# all.net
KiCad netlist of a schematic drawn in EAGLE
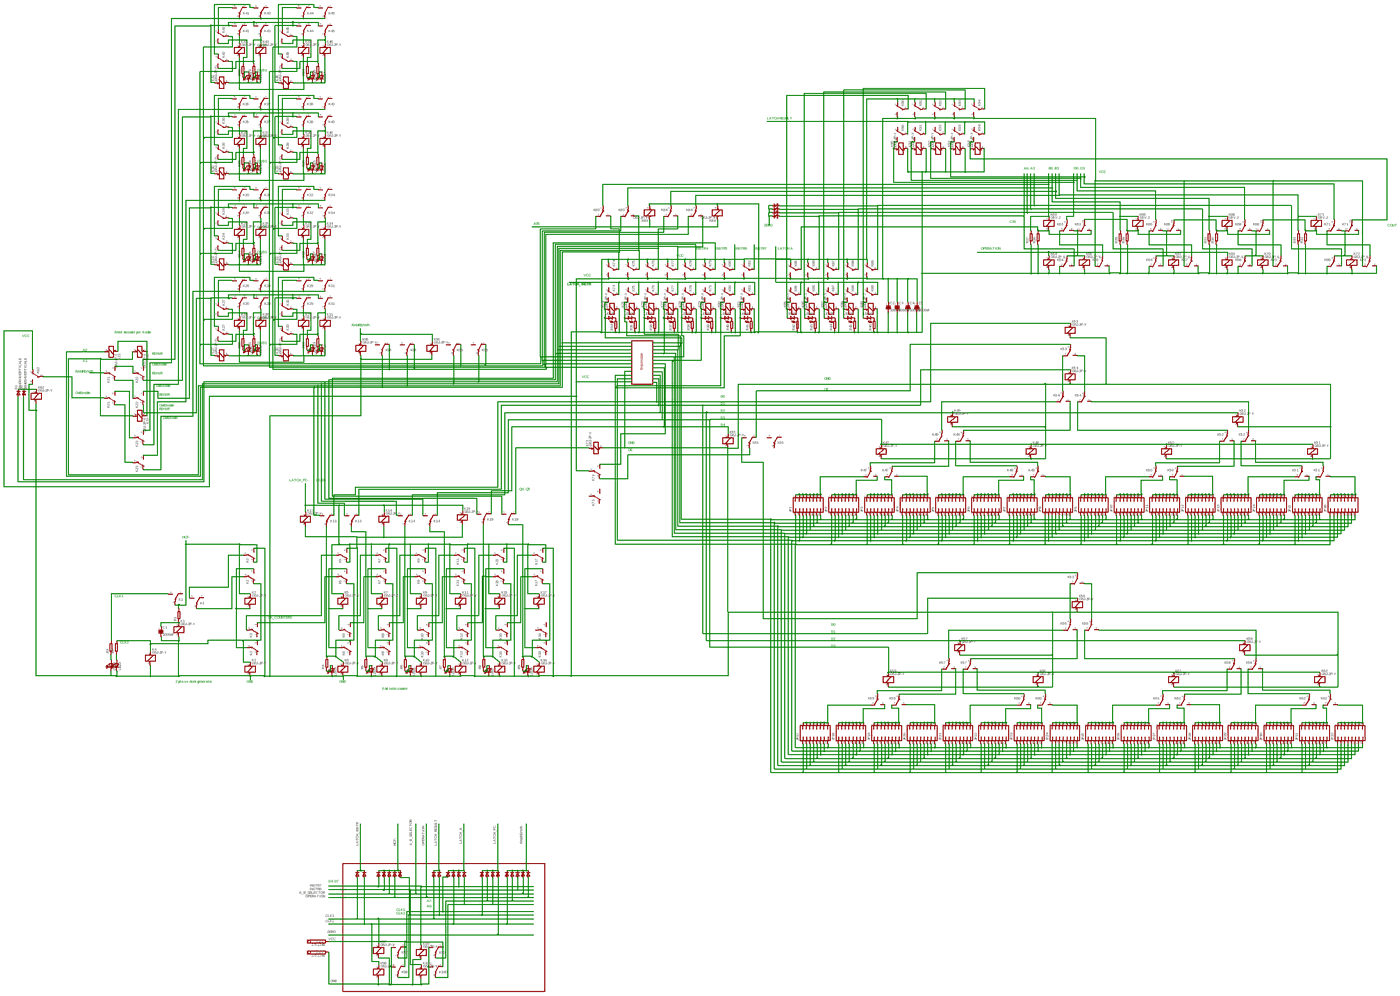
[diagram p0: schematic, sheet 1, overview]
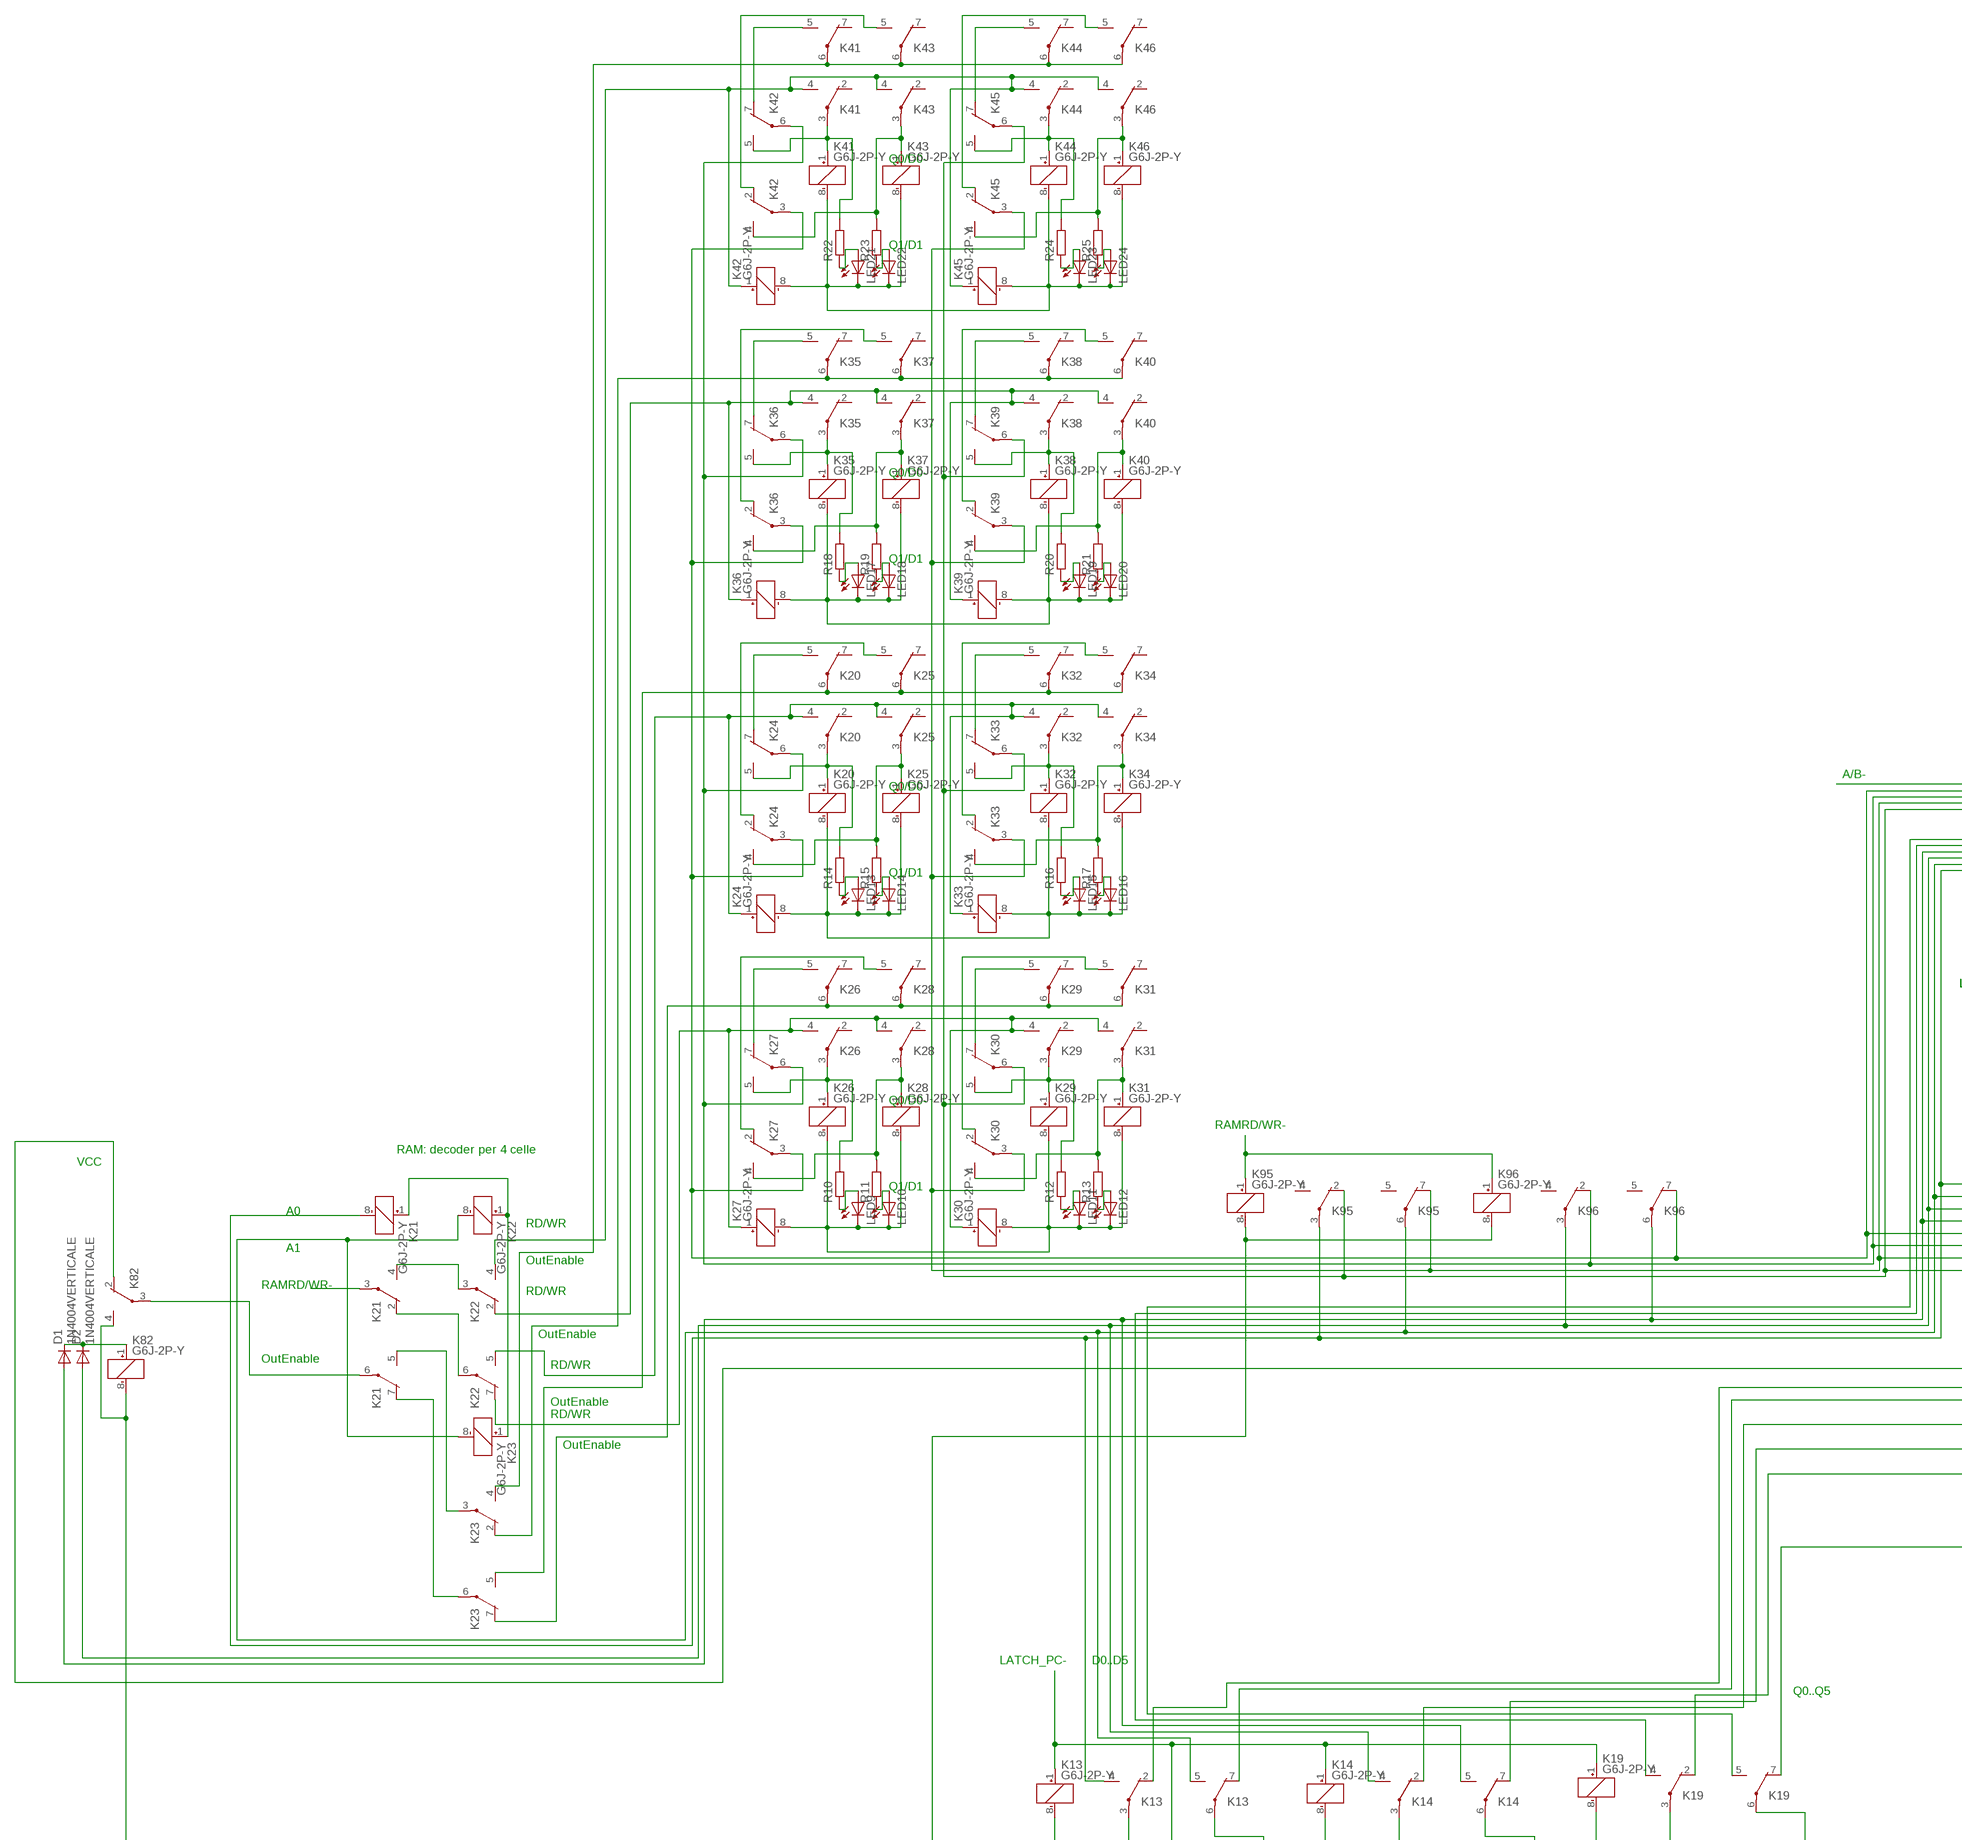
[diagram p1: schematic, sheet 1, part 1 of 5]
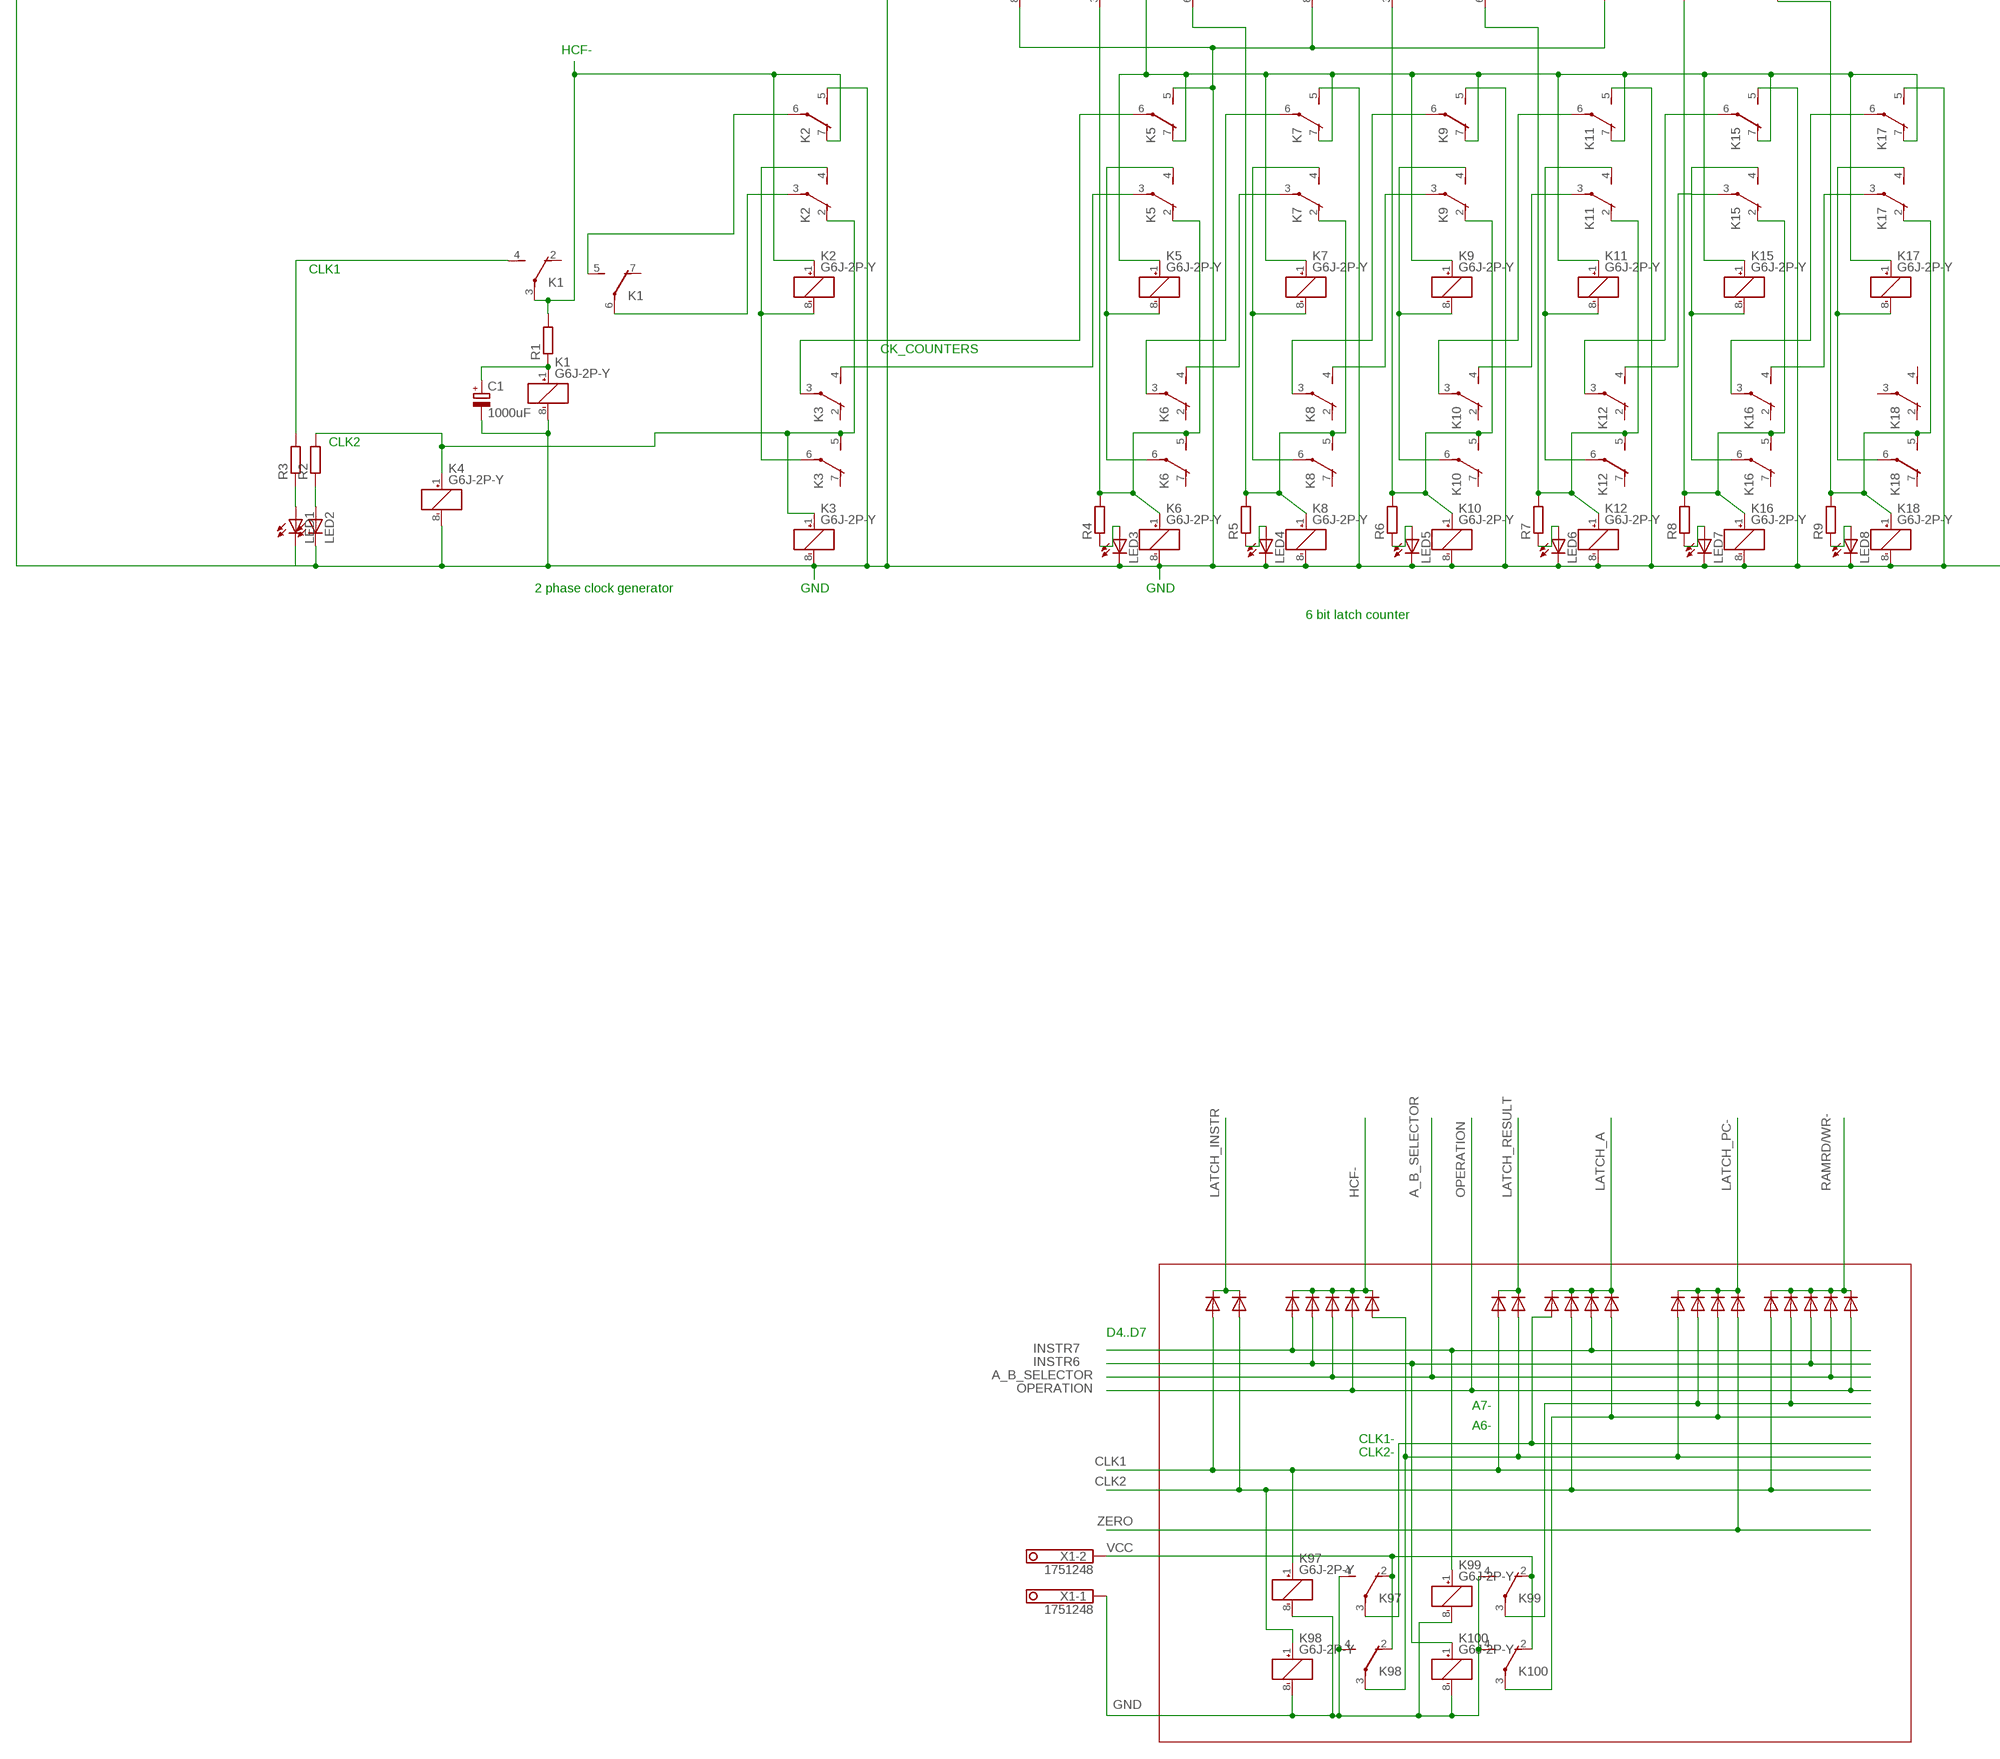
[diagram p2: schematic, sheet 1, part 2 of 5]
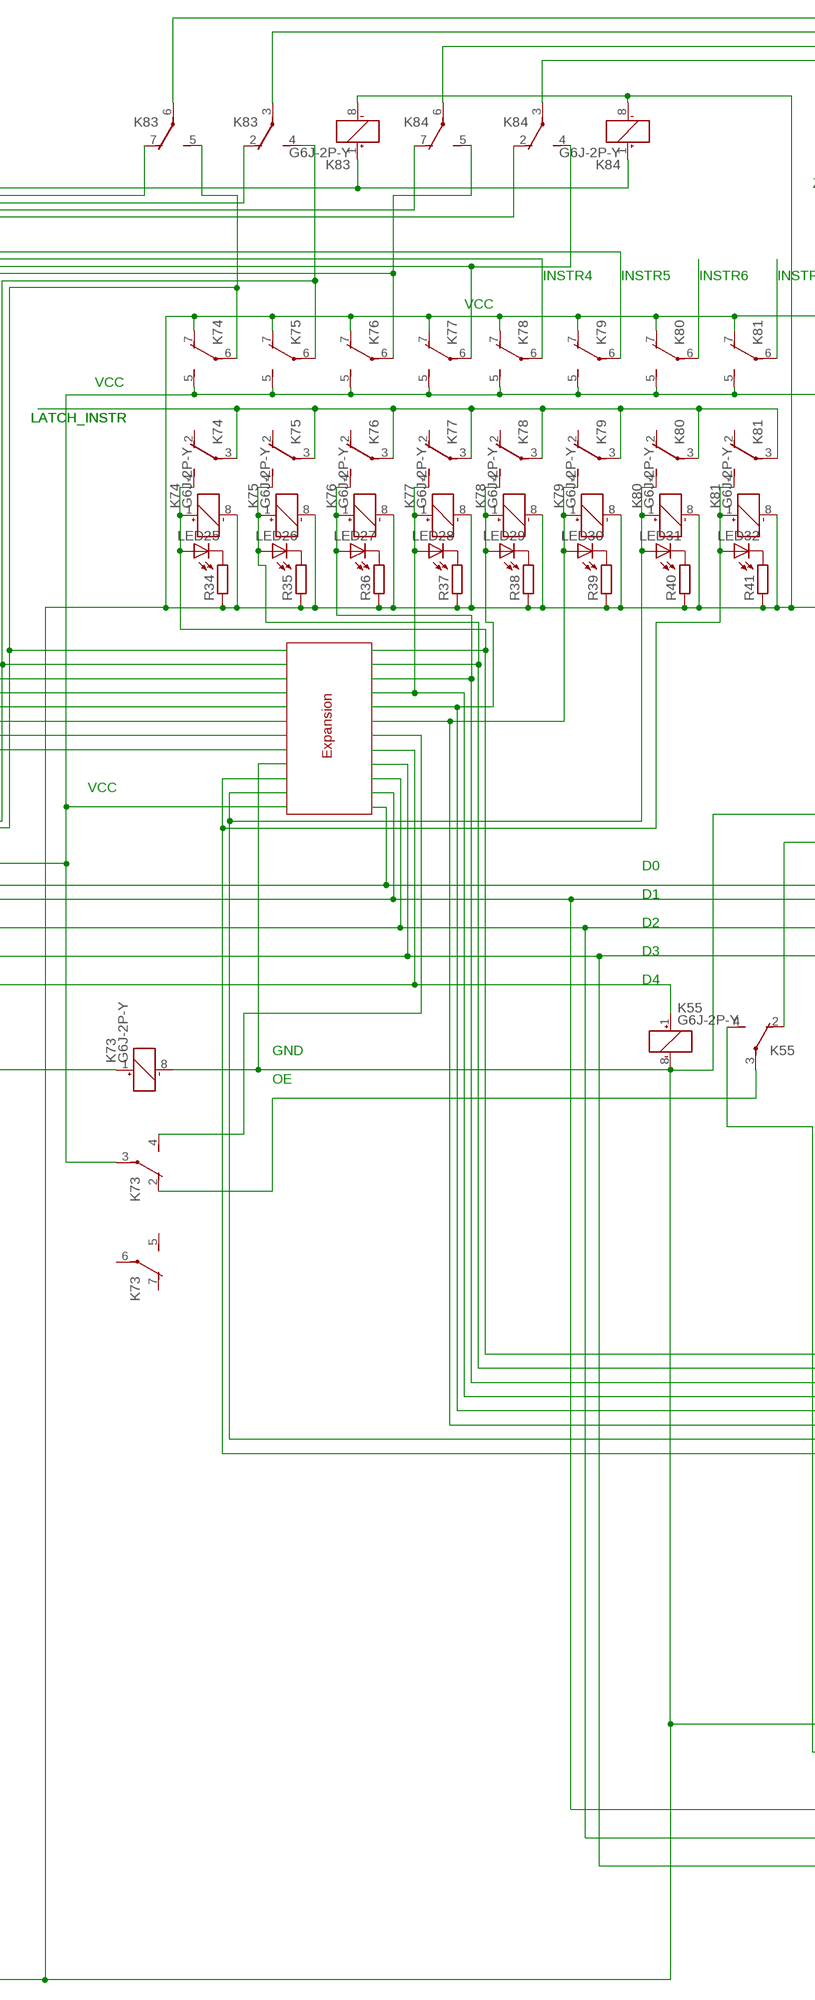
[diagram p3: schematic, sheet 1, part 3 of 5]
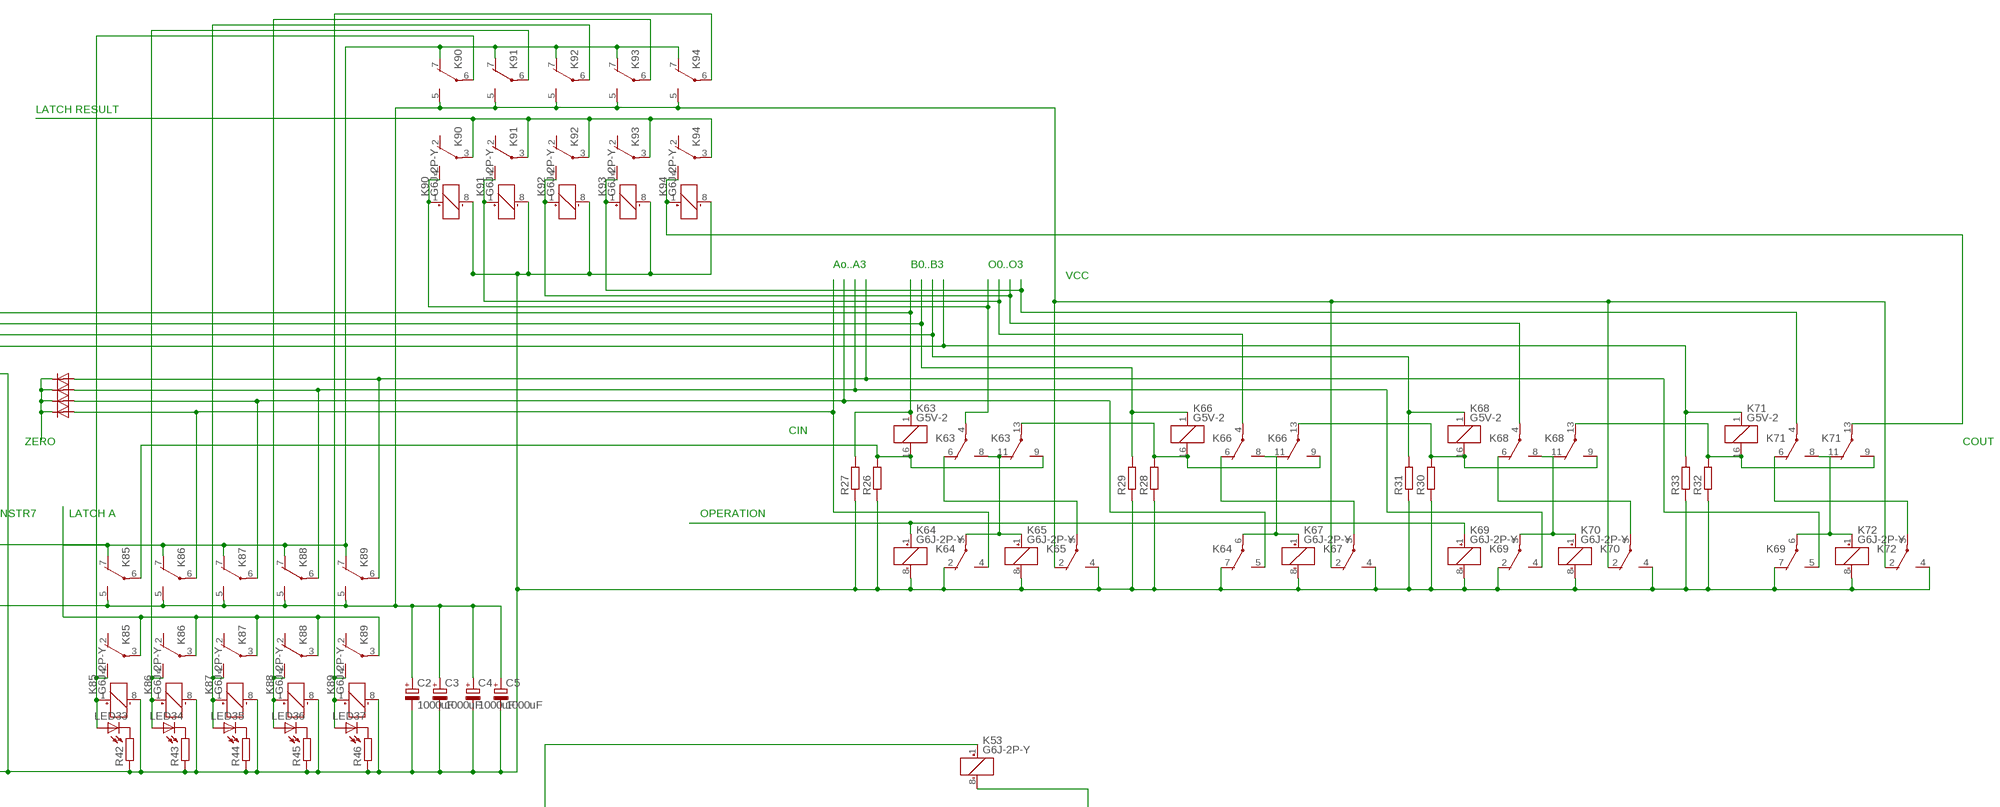
[diagram p4: schematic, sheet 1, part 4 of 5]
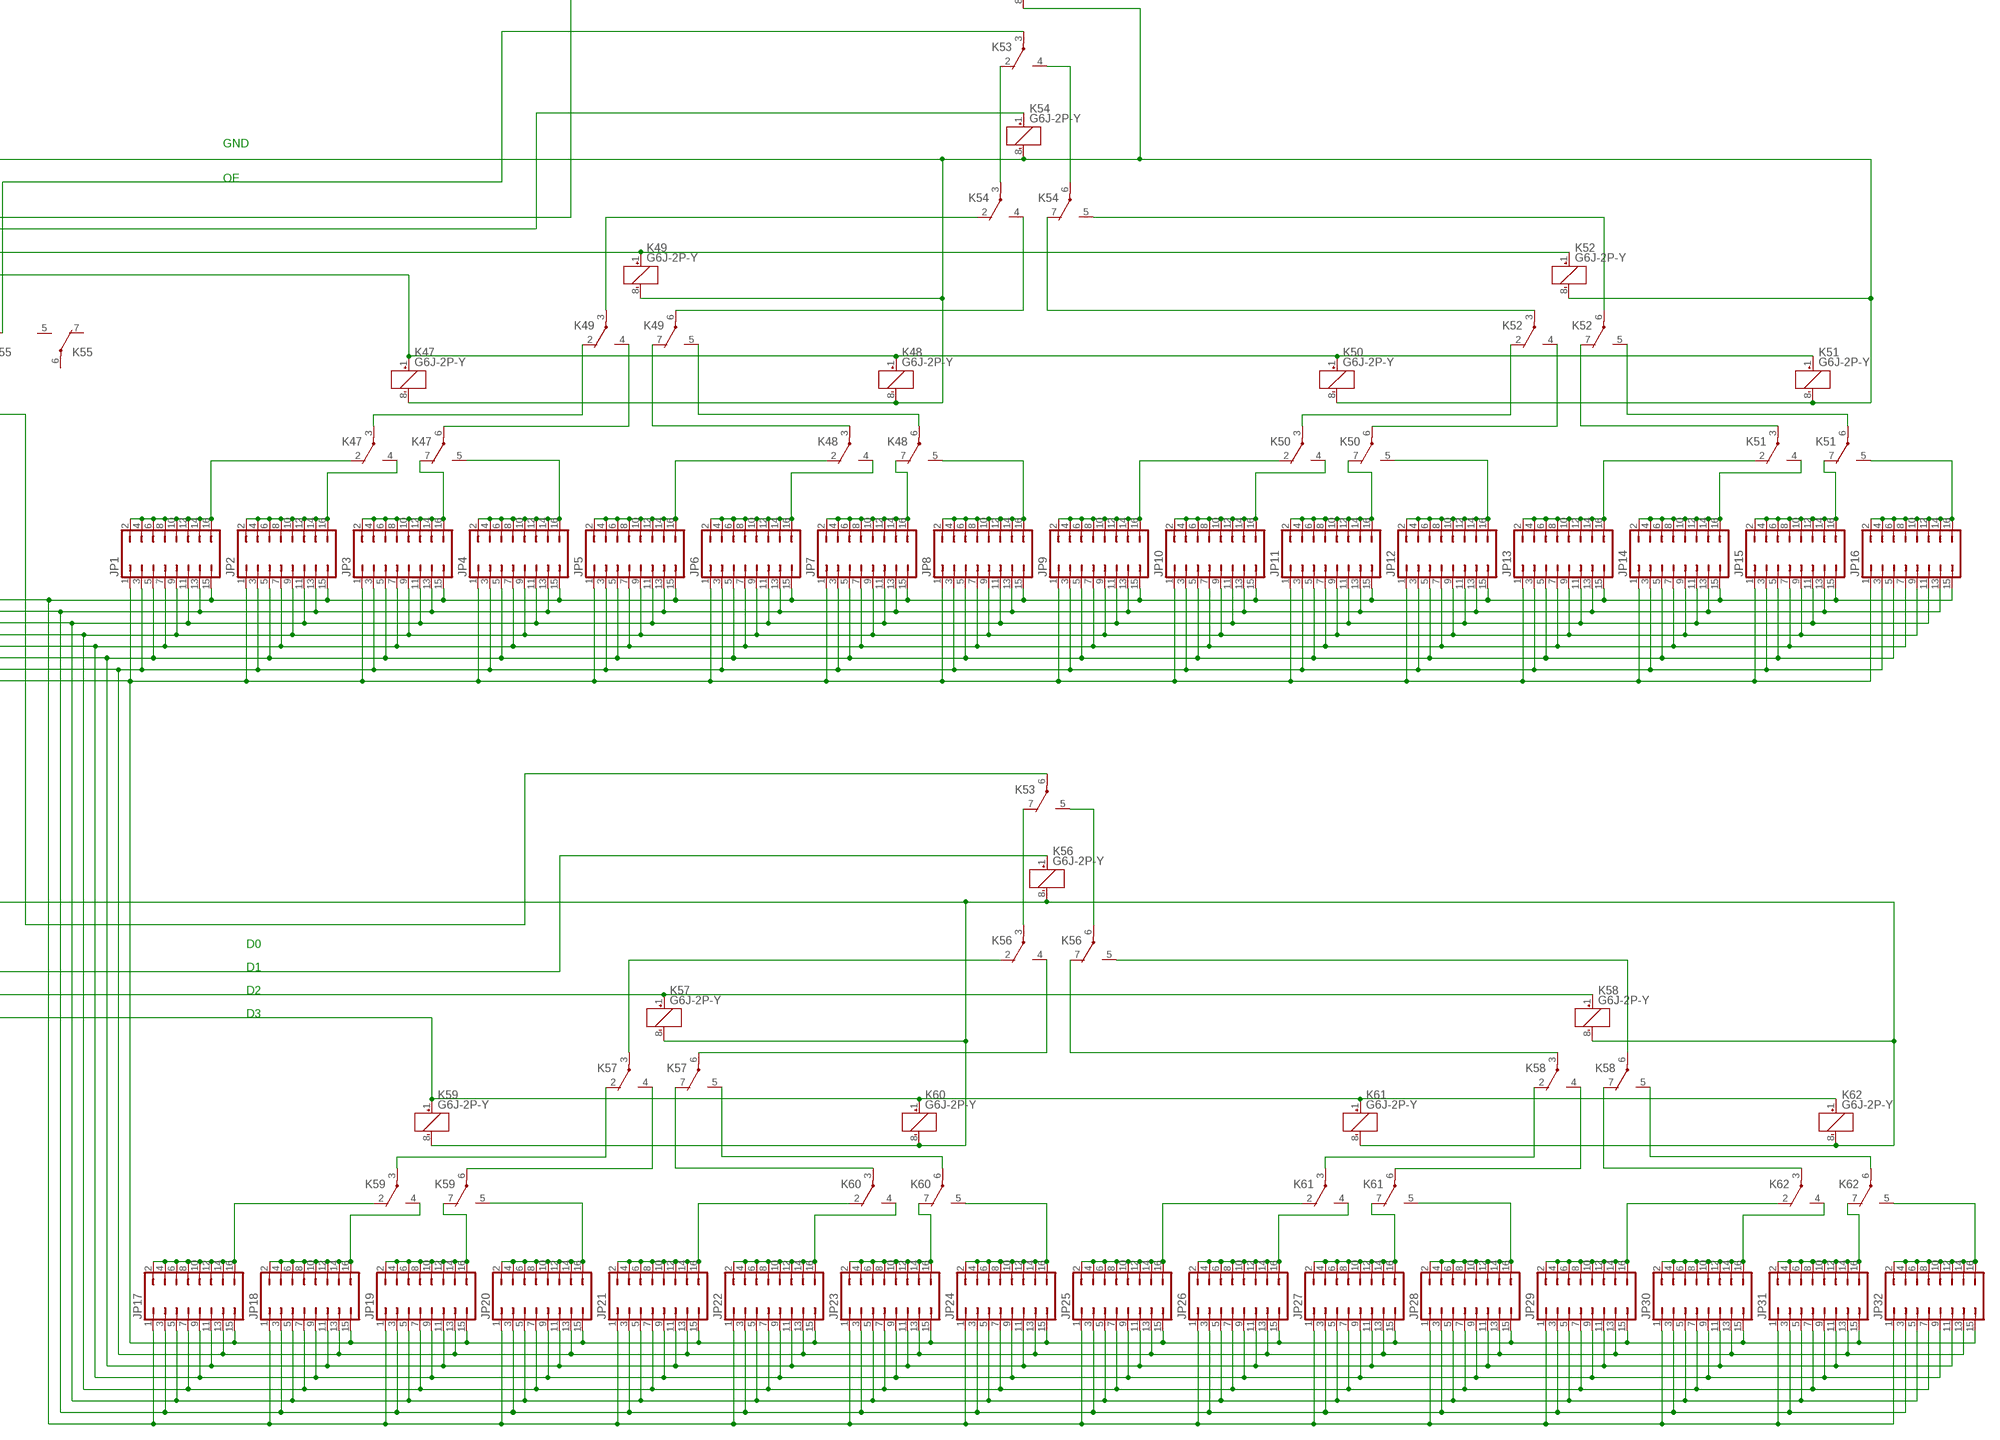
[diagram p5: schematic, sheet 1, part 5 of 5]

(export (version "E")
  (design (tool "Eeschema 10.0.6"))
  (components
    (comp (ref "C1")
      (value "1000uF")
      (footprint "eagle-import:E5-10,5")
      (libsource (lib "eagle-import") (part "CPOL-EUE5-10.5"))
    )
    (comp (ref "C2")
      (value "1000uF")
      (footprint "eagle-import:E3,5-10")
      (libsource (lib "eagle-import") (part "CPOL-EUE3.5-10"))
    )
    (comp (ref "C3")
      (value "1000uF")
      (footprint "eagle-import:E3,5-10")
      (libsource (lib "eagle-import") (part "CPOL-EUE3.5-10"))
    )
    (comp (ref "C4")
      (value "1000uF")
      (footprint "eagle-import:E3,5-10")
      (libsource (lib "eagle-import") (part "CPOL-EUE3.5-10"))
    )
    (comp (ref "C5")
      (value "1000uF")
      (footprint "eagle-import:E3,5-10")
      (libsource (lib "eagle-import") (part "CPOL-EUE3.5-10"))
    )
    (comp (ref "D1")
      (value "1N4004VERTICALE")
      (footprint "eagle-import:ZDIO-2.5")
      (libsource (lib "eagle-import") (part "1N4004VERTICALE"))
    )
    (comp (ref "D2")
      (value "1N4004VERTICALE")
      (footprint "eagle-import:ZDIO-2.5")
      (libsource (lib "eagle-import") (part "1N4004VERTICALE"))
    )
    (comp (ref "D3")
      (value "1N4004VERTICALE")
      (footprint "eagle-import:ZDIO-2.5")
      (libsource (lib "eagle-import") (part "1N4004VERTICALE"))
    )
    (comp (ref "D4")
      (value "1N4004VERTICALE")
      (footprint "eagle-import:ZDIO-2.5")
      (libsource (lib "eagle-import") (part "1N4004VERTICALE"))
    )
    (comp (ref "D5")
      (value "1N4004VERTICALE")
      (footprint "eagle-import:ZDIO-2.5")
      (libsource (lib "eagle-import") (part "1N4004VERTICALE"))
    )
    (comp (ref "D6")
      (value "1N4004VERTICALE")
      (footprint "eagle-import:ZDIO-2.5")
      (libsource (lib "eagle-import") (part "1N4004VERTICALE"))
    )
    (comp (ref "D29")
      (value "1N4004VERTICALE")
      (footprint "eagle-import:ZDIO-2.5")
      (libsource (lib "eagle-import") (part "1N4004VERTICALE"))
    )
    (comp (ref "D30")
      (value "1N4004VERTICALE")
      (footprint "eagle-import:ZDIO-2.5")
      (libsource (lib "eagle-import") (part "1N4004VERTICALE"))
    )
    (comp (ref "D31")
      (value "1N4004VERTICALE")
      (footprint "eagle-import:ZDIO-2.5")
      (libsource (lib "eagle-import") (part "1N4004VERTICALE"))
    )
    (comp (ref "D32")
      (value "1N4004VERTICALE")
      (footprint "eagle-import:ZDIO-2.5")
      (libsource (lib "eagle-import") (part "1N4004VERTICALE"))
    )
    (comp (ref "D33")
      (value "1N4004VERTICALE")
      (footprint "eagle-import:ZDIO-2.5")
      (libsource (lib "eagle-import") (part "1N4004VERTICALE"))
    )
    (comp (ref "D34")
      (value "1N4004VERTICALE")
      (footprint "eagle-import:ZDIO-2.5")
      (libsource (lib "eagle-import") (part "1N4004VERTICALE"))
    )
    (comp (ref "D35")
      (value "1N4004VERTICALE")
      (footprint "eagle-import:ZDIO-2.5")
      (libsource (lib "eagle-import") (part "1N4004VERTICALE"))
    )
    (comp (ref "D36")
      (value "1N4004VERTICALE")
      (footprint "eagle-import:ZDIO-2.5")
      (libsource (lib "eagle-import") (part "1N4004VERTICALE"))
    )
    (comp (ref "D37")
      (value "1N4004VERTICALE")
      (footprint "eagle-import:ZDIO-2.5")
      (libsource (lib "eagle-import") (part "1N4004VERTICALE"))
    )
    (comp (ref "D38")
      (value "1N4004VERTICALE")
      (footprint "eagle-import:ZDIO-2.5")
      (libsource (lib "eagle-import") (part "1N4004VERTICALE"))
    )
    (comp (ref "D39")
      (value "1N4004VERTICALE")
      (footprint "eagle-import:ZDIO-2.5")
      (libsource (lib "eagle-import") (part "1N4004VERTICALE"))
    )
    (comp (ref "D40")
      (value "1N4004VERTICALE")
      (footprint "eagle-import:ZDIO-2.5")
      (libsource (lib "eagle-import") (part "1N4004VERTICALE"))
    )
    (comp (ref "D41")
      (value "1N4004VERTICALE")
      (footprint "eagle-import:ZDIO-2.5")
      (libsource (lib "eagle-import") (part "1N4004VERTICALE"))
    )
    (comp (ref "D42")
      (value "1N4004VERTICALE")
      (footprint "eagle-import:ZDIO-2.5")
      (libsource (lib "eagle-import") (part "1N4004VERTICALE"))
    )
    (comp (ref "D43")
      (value "1N4004VERTICALE")
      (footprint "eagle-import:ZDIO-2.5")
      (libsource (lib "eagle-import") (part "1N4004VERTICALE"))
    )
    (comp (ref "D44")
      (value "1N4004VERTICALE")
      (footprint "eagle-import:ZDIO-2.5")
      (libsource (lib "eagle-import") (part "1N4004VERTICALE"))
    )
    (comp (ref "D45")
      (value "1N4004VERTICALE")
      (footprint "eagle-import:ZDIO-2.5")
      (libsource (lib "eagle-import") (part "1N4004VERTICALE"))
    )
    (comp (ref "D46")
      (value "1N4004VERTICALE")
      (footprint "eagle-import:ZDIO-2.5")
      (libsource (lib "eagle-import") (part "1N4004VERTICALE"))
    )
    (comp (ref "D47")
      (value "1N4004VERTICALE")
      (footprint "eagle-import:ZDIO-2.5")
      (libsource (lib "eagle-import") (part "1N4004VERTICALE"))
    )
    (comp (ref "D48")
      (value "1N4004VERTICALE")
      (footprint "eagle-import:ZDIO-2.5")
      (libsource (lib "eagle-import") (part "1N4004VERTICALE"))
    )
    (comp (ref "D49")
      (value "1N4004VERTICALE")
      (footprint "eagle-import:ZDIO-2.5")
      (libsource (lib "eagle-import") (part "1N4004VERTICALE"))
    )
    (comp (ref "D50")
      (value "1N4004VERTICALE")
      (footprint "eagle-import:ZDIO-2.5")
      (libsource (lib "eagle-import") (part "1N4004VERTICALE"))
    )
    (comp (ref "JP1")
      (value "JP8Q")
      (footprint "eagle-import:JP8Q")
      (libsource (lib "eagle-import") (part "JP8Q"))
    )
    (comp (ref "JP2")
      (value "JP8Q")
      (footprint "eagle-import:JP8Q")
      (libsource (lib "eagle-import") (part "JP8Q"))
    )
    (comp (ref "JP3")
      (value "JP8Q")
      (footprint "eagle-import:JP8Q")
      (libsource (lib "eagle-import") (part "JP8Q"))
    )
    (comp (ref "JP4")
      (value "JP8Q")
      (footprint "eagle-import:JP8Q")
      (libsource (lib "eagle-import") (part "JP8Q"))
    )
    (comp (ref "JP5")
      (value "JP8Q")
      (footprint "eagle-import:JP8Q")
      (libsource (lib "eagle-import") (part "JP8Q"))
    )
    (comp (ref "JP6")
      (value "JP8Q")
      (footprint "eagle-import:JP8Q")
      (libsource (lib "eagle-import") (part "JP8Q"))
    )
    (comp (ref "JP7")
      (value "JP8Q")
      (footprint "eagle-import:JP8Q")
      (libsource (lib "eagle-import") (part "JP8Q"))
    )
    (comp (ref "JP8")
      (value "JP8Q")
      (footprint "eagle-import:JP8Q")
      (libsource (lib "eagle-import") (part "JP8Q"))
    )
    (comp (ref "JP9")
      (value "JP8Q")
      (footprint "eagle-import:JP8Q")
      (libsource (lib "eagle-import") (part "JP8Q"))
    )
    (comp (ref "JP10")
      (value "JP8Q")
      (footprint "eagle-import:JP8Q")
      (libsource (lib "eagle-import") (part "JP8Q"))
    )
    (comp (ref "JP11")
      (value "JP8Q")
      (footprint "eagle-import:JP8Q")
      (libsource (lib "eagle-import") (part "JP8Q"))
    )
    (comp (ref "JP12")
      (value "JP8Q")
      (footprint "eagle-import:JP8Q")
      (libsource (lib "eagle-import") (part "JP8Q"))
    )
    (comp (ref "JP13")
      (value "JP8Q")
      (footprint "eagle-import:JP8Q")
      (libsource (lib "eagle-import") (part "JP8Q"))
    )
    (comp (ref "JP14")
      (value "JP8Q")
      (footprint "eagle-import:JP8Q")
      (libsource (lib "eagle-import") (part "JP8Q"))
    )
    (comp (ref "JP15")
      (value "JP8Q")
      (footprint "eagle-import:JP8Q")
      (libsource (lib "eagle-import") (part "JP8Q"))
    )
    (comp (ref "JP16")
      (value "JP8Q")
      (footprint "eagle-import:JP8Q")
      (libsource (lib "eagle-import") (part "JP8Q"))
    )
    (comp (ref "JP17")
      (value "JP8Q")
      (footprint "eagle-import:JP8Q")
      (libsource (lib "eagle-import") (part "JP8Q"))
    )
    (comp (ref "JP18")
      (value "JP8Q")
      (footprint "eagle-import:JP8Q")
      (libsource (lib "eagle-import") (part "JP8Q"))
    )
    (comp (ref "JP19")
      (value "JP8Q")
      (footprint "eagle-import:JP8Q")
      (libsource (lib "eagle-import") (part "JP8Q"))
    )
    (comp (ref "JP20")
      (value "JP8Q")
      (footprint "eagle-import:JP8Q")
      (libsource (lib "eagle-import") (part "JP8Q"))
    )
    (comp (ref "JP21")
      (value "JP8Q")
      (footprint "eagle-import:JP8Q")
      (libsource (lib "eagle-import") (part "JP8Q"))
    )
    (comp (ref "JP22")
      (value "JP8Q")
      (footprint "eagle-import:JP8Q")
      (libsource (lib "eagle-import") (part "JP8Q"))
    )
    (comp (ref "JP23")
      (value "JP8Q")
      (footprint "eagle-import:JP8Q")
      (libsource (lib "eagle-import") (part "JP8Q"))
    )
    (comp (ref "JP24")
      (value "JP8Q")
      (footprint "eagle-import:JP8Q")
      (libsource (lib "eagle-import") (part "JP8Q"))
    )
    (comp (ref "JP25")
      (value "JP8Q")
      (footprint "eagle-import:JP8Q")
      (libsource (lib "eagle-import") (part "JP8Q"))
    )
    (comp (ref "JP26")
      (value "JP8Q")
      (footprint "eagle-import:JP8Q")
      (libsource (lib "eagle-import") (part "JP8Q"))
    )
    (comp (ref "JP27")
      (value "JP8Q")
      (footprint "eagle-import:JP8Q")
      (libsource (lib "eagle-import") (part "JP8Q"))
    )
    (comp (ref "JP28")
      (value "JP8Q")
      (footprint "eagle-import:JP8Q")
      (libsource (lib "eagle-import") (part "JP8Q"))
    )
    (comp (ref "JP29")
      (value "JP8Q")
      (footprint "eagle-import:JP8Q")
      (libsource (lib "eagle-import") (part "JP8Q"))
    )
    (comp (ref "JP30")
      (value "JP8Q")
      (footprint "eagle-import:JP8Q")
      (libsource (lib "eagle-import") (part "JP8Q"))
    )
    (comp (ref "JP31")
      (value "JP8Q")
      (footprint "eagle-import:JP8Q")
      (libsource (lib "eagle-import") (part "JP8Q"))
    )
    (comp (ref "JP32")
      (value "JP8Q")
      (footprint "eagle-import:JP8Q")
      (libsource (lib "eagle-import") (part "JP8Q"))
    )
    (comp (ref "K1")
      (value "G6J-2P-Y")
      (footprint "eagle-import:G6J-2P-Y")
      (fields (field (name "MF") "OMRON COMPONENTS USA") (field (name "MPN") "G6J-2P-Y-DC12"))
      (libsource (lib "eagle-import") (part "G6J-2?-YP"))
    )
    (comp (ref "K2")
      (value "G6J-2P-Y")
      (footprint "eagle-import:G6J-2P-Y")
      (fields (field (name "MF") "OMRON COMPONENTS USA") (field (name "MPN") "G6J-2P-Y-DC12"))
      (libsource (lib "eagle-import") (part "G6J-2?-YP"))
    )
    (comp (ref "K3")
      (value "G6J-2P-Y")
      (footprint "eagle-import:G6J-2P-Y")
      (fields (field (name "MF") "OMRON COMPONENTS USA") (field (name "MPN") "G6J-2P-Y-DC12"))
      (libsource (lib "eagle-import") (part "G6J-2?-YP"))
    )
    (comp (ref "K4")
      (value "G6J-2P-Y")
      (footprint "eagle-import:G6J-2P-Y")
      (fields (field (name "MF") "OMRON COMPONENTS USA") (field (name "MPN") "G6J-2P-Y-DC12"))
      (libsource (lib "eagle-import") (part "G6J-2?-YP"))
    )
    (comp (ref "K5")
      (value "G6J-2P-Y")
      (footprint "eagle-import:G6J-2P-Y")
      (fields (field (name "MF") "OMRON COMPONENTS USA") (field (name "MPN") "G6J-2P-Y-DC12"))
      (libsource (lib "eagle-import") (part "G6J-2?-YP"))
    )
    (comp (ref "K6")
      (value "G6J-2P-Y")
      (footprint "eagle-import:G6J-2P-Y")
      (fields (field (name "MF") "OMRON COMPONENTS USA") (field (name "MPN") "G6J-2P-Y-DC12"))
      (libsource (lib "eagle-import") (part "G6J-2?-YP"))
    )
    (comp (ref "K7")
      (value "G6J-2P-Y")
      (footprint "eagle-import:G6J-2P-Y")
      (fields (field (name "MF") "OMRON COMPONENTS USA") (field (name "MPN") "G6J-2P-Y-DC12"))
      (libsource (lib "eagle-import") (part "G6J-2?-YP"))
    )
    (comp (ref "K8")
      (value "G6J-2P-Y")
      (footprint "eagle-import:G6J-2P-Y")
      (fields (field (name "MF") "OMRON COMPONENTS USA") (field (name "MPN") "G6J-2P-Y-DC12"))
      (libsource (lib "eagle-import") (part "G6J-2?-YP"))
    )
    (comp (ref "K9")
      (value "G6J-2P-Y")
      (footprint "eagle-import:G6J-2P-Y")
      (fields (field (name "MF") "OMRON COMPONENTS USA") (field (name "MPN") "G6J-2P-Y-DC12"))
      (libsource (lib "eagle-import") (part "G6J-2?-YP"))
    )
    (comp (ref "K10")
      (value "G6J-2P-Y")
      (footprint "eagle-import:G6J-2P-Y")
      (fields (field (name "MF") "OMRON COMPONENTS USA") (field (name "MPN") "G6J-2P-Y-DC12"))
      (libsource (lib "eagle-import") (part "G6J-2?-YP"))
    )
    (comp (ref "K11")
      (value "G6J-2P-Y")
      (footprint "eagle-import:G6J-2P-Y")
      (fields (field (name "MF") "OMRON COMPONENTS USA") (field (name "MPN") "G6J-2P-Y-DC12"))
      (libsource (lib "eagle-import") (part "G6J-2?-YP"))
    )
    (comp (ref "K12")
      (value "G6J-2P-Y")
      (footprint "eagle-import:G6J-2P-Y")
      (fields (field (name "MF") "OMRON COMPONENTS USA") (field (name "MPN") "G6J-2P-Y-DC12"))
      (libsource (lib "eagle-import") (part "G6J-2?-YP"))
    )
    (comp (ref "K13")
      (value "G6J-2P-Y")
      (footprint "eagle-import:G6J-2P-Y")
      (fields (field (name "MF") "OMRON COMPONENTS USA") (field (name "MPN") "G6J-2P-Y-DC12"))
      (libsource (lib "eagle-import") (part "G6J-2?-YP"))
    )
    (comp (ref "K14")
      (value "G6J-2P-Y")
      (footprint "eagle-import:G6J-2P-Y")
      (fields (field (name "MF") "OMRON COMPONENTS USA") (field (name "MPN") "G6J-2P-Y-DC12"))
      (libsource (lib "eagle-import") (part "G6J-2?-YP"))
    )
    (comp (ref "K15")
      (value "G6J-2P-Y")
      (footprint "eagle-import:G6J-2P-Y")
      (fields (field (name "MF") "OMRON COMPONENTS USA") (field (name "MPN") "G6J-2P-Y-DC12"))
      (libsource (lib "eagle-import") (part "G6J-2?-YP"))
    )
    (comp (ref "K16")
      (value "G6J-2P-Y")
      (footprint "eagle-import:G6J-2P-Y")
      (fields (field (name "MF") "OMRON COMPONENTS USA") (field (name "MPN") "G6J-2P-Y-DC12"))
      (libsource (lib "eagle-import") (part "G6J-2?-YP"))
    )
    (comp (ref "K17")
      (value "G6J-2P-Y")
      (footprint "eagle-import:G6J-2P-Y")
      (fields (field (name "MF") "OMRON COMPONENTS USA") (field (name "MPN") "G6J-2P-Y-DC12"))
      (libsource (lib "eagle-import") (part "G6J-2?-YP"))
    )
    (comp (ref "K18")
      (value "G6J-2P-Y")
      (footprint "eagle-import:G6J-2P-Y")
      (fields (field (name "MF") "OMRON COMPONENTS USA") (field (name "MPN") "G6J-2P-Y-DC12"))
      (libsource (lib "eagle-import") (part "G6J-2?-YP"))
    )
    (comp (ref "K19")
      (value "G6J-2P-Y")
      (footprint "eagle-import:G6J-2P-Y")
      (fields (field (name "MF") "OMRON COMPONENTS USA") (field (name "MPN") "G6J-2P-Y-DC12"))
      (libsource (lib "eagle-import") (part "G6J-2?-YP"))
    )
    (comp (ref "K20")
      (value "G6J-2P-Y")
      (footprint "eagle-import:G6J-2P-Y")
      (fields (field (name "MF") "OMRON COMPONENTS USA") (field (name "MPN") "G6J-2P-Y-DC12"))
      (libsource (lib "eagle-import") (part "G6J-2?-YP"))
    )
    (comp (ref "K21")
      (value "G6J-2P-Y")
      (footprint "eagle-import:G6J-2P-Y")
      (fields (field (name "MF") "OMRON COMPONENTS USA") (field (name "MPN") "G6J-2P-Y-DC12"))
      (libsource (lib "eagle-import") (part "G6J-2?-YP"))
    )
    (comp (ref "K22")
      (value "G6J-2P-Y")
      (footprint "eagle-import:G6J-2P-Y")
      (fields (field (name "MF") "OMRON COMPONENTS USA") (field (name "MPN") "G6J-2P-Y-DC12"))
      (libsource (lib "eagle-import") (part "G6J-2?-YP"))
    )
    (comp (ref "K23")
      (value "G6J-2P-Y")
      (footprint "eagle-import:G6J-2P-Y")
      (fields (field (name "MF") "OMRON COMPONENTS USA") (field (name "MPN") "G6J-2P-Y-DC12"))
      (libsource (lib "eagle-import") (part "G6J-2?-YP"))
    )
    (comp (ref "K24")
      (value "G6J-2P-Y")
      (footprint "eagle-import:G6J-2P-Y")
      (fields (field (name "MF") "OMRON COMPONENTS USA") (field (name "MPN") "G6J-2P-Y-DC12"))
      (libsource (lib "eagle-import") (part "G6J-2?-YP"))
    )
    (comp (ref "K25")
      (value "G6J-2P-Y")
      (footprint "eagle-import:G6J-2P-Y")
      (fields (field (name "MF") "OMRON COMPONENTS USA") (field (name "MPN") "G6J-2P-Y-DC12"))
      (libsource (lib "eagle-import") (part "G6J-2?-YP"))
    )
    (comp (ref "K26")
      (value "G6J-2P-Y")
      (footprint "eagle-import:G6J-2P-Y")
      (fields (field (name "MF") "OMRON COMPONENTS USA") (field (name "MPN") "G6J-2P-Y-DC12"))
      (libsource (lib "eagle-import") (part "G6J-2?-YP"))
    )
    (comp (ref "K27")
      (value "G6J-2P-Y")
      (footprint "eagle-import:G6J-2P-Y")
      (fields (field (name "MF") "OMRON COMPONENTS USA") (field (name "MPN") "G6J-2P-Y-DC12"))
      (libsource (lib "eagle-import") (part "G6J-2?-YP"))
    )
    (comp (ref "K28")
      (value "G6J-2P-Y")
      (footprint "eagle-import:G6J-2P-Y")
      (fields (field (name "MF") "OMRON COMPONENTS USA") (field (name "MPN") "G6J-2P-Y-DC12"))
      (libsource (lib "eagle-import") (part "G6J-2?-YP"))
    )
    (comp (ref "K29")
      (value "G6J-2P-Y")
      (footprint "eagle-import:G6J-2P-Y")
      (fields (field (name "MF") "OMRON COMPONENTS USA") (field (name "MPN") "G6J-2P-Y-DC12"))
      (libsource (lib "eagle-import") (part "G6J-2?-YP"))
    )
    (comp (ref "K30")
      (value "G6J-2P-Y")
      (footprint "eagle-import:G6J-2P-Y")
      (fields (field (name "MF") "OMRON COMPONENTS USA") (field (name "MPN") "G6J-2P-Y-DC12"))
      (libsource (lib "eagle-import") (part "G6J-2?-YP"))
    )
    (comp (ref "K31")
      (value "G6J-2P-Y")
      (footprint "eagle-import:G6J-2P-Y")
      (fields (field (name "MF") "OMRON COMPONENTS USA") (field (name "MPN") "G6J-2P-Y-DC12"))
      (libsource (lib "eagle-import") (part "G6J-2?-YP"))
    )
    (comp (ref "K32")
      (value "G6J-2P-Y")
      (footprint "eagle-import:G6J-2P-Y")
      (fields (field (name "MF") "OMRON COMPONENTS USA") (field (name "MPN") "G6J-2P-Y-DC12"))
      (libsource (lib "eagle-import") (part "G6J-2?-YP"))
    )
    (comp (ref "K33")
      (value "G6J-2P-Y")
      (footprint "eagle-import:G6J-2P-Y")
      (fields (field (name "MF") "OMRON COMPONENTS USA") (field (name "MPN") "G6J-2P-Y-DC12"))
      (libsource (lib "eagle-import") (part "G6J-2?-YP"))
    )
    (comp (ref "K34")
      (value "G6J-2P-Y")
      (footprint "eagle-import:G6J-2P-Y")
      (fields (field (name "MF") "OMRON COMPONENTS USA") (field (name "MPN") "G6J-2P-Y-DC12"))
      (libsource (lib "eagle-import") (part "G6J-2?-YP"))
    )
    (comp (ref "K35")
      (value "G6J-2P-Y")
      (footprint "eagle-import:G6J-2P-Y")
      (fields (field (name "MF") "OMRON COMPONENTS USA") (field (name "MPN") "G6J-2P-Y-DC12"))
      (libsource (lib "eagle-import") (part "G6J-2?-YP"))
    )
    (comp (ref "K36")
      (value "G6J-2P-Y")
      (footprint "eagle-import:G6J-2P-Y")
      (fields (field (name "MF") "OMRON COMPONENTS USA") (field (name "MPN") "G6J-2P-Y-DC12"))
      (libsource (lib "eagle-import") (part "G6J-2?-YP"))
    )
    (comp (ref "K37")
      (value "G6J-2P-Y")
      (footprint "eagle-import:G6J-2P-Y")
      (fields (field (name "MF") "OMRON COMPONENTS USA") (field (name "MPN") "G6J-2P-Y-DC12"))
      (libsource (lib "eagle-import") (part "G6J-2?-YP"))
    )
    (comp (ref "K38")
      (value "G6J-2P-Y")
      (footprint "eagle-import:G6J-2P-Y")
      (fields (field (name "MF") "OMRON COMPONENTS USA") (field (name "MPN") "G6J-2P-Y-DC12"))
      (libsource (lib "eagle-import") (part "G6J-2?-YP"))
    )
    (comp (ref "K39")
      (value "G6J-2P-Y")
      (footprint "eagle-import:G6J-2P-Y")
      (fields (field (name "MF") "OMRON COMPONENTS USA") (field (name "MPN") "G6J-2P-Y-DC12"))
      (libsource (lib "eagle-import") (part "G6J-2?-YP"))
    )
    (comp (ref "K40")
      (value "G6J-2P-Y")
      (footprint "eagle-import:G6J-2P-Y")
      (fields (field (name "MF") "OMRON COMPONENTS USA") (field (name "MPN") "G6J-2P-Y-DC12"))
      (libsource (lib "eagle-import") (part "G6J-2?-YP"))
    )
    (comp (ref "K41")
      (value "G6J-2P-Y")
      (footprint "eagle-import:G6J-2P-Y")
      (fields (field (name "MF") "OMRON COMPONENTS USA") (field (name "MPN") "G6J-2P-Y-DC12"))
      (libsource (lib "eagle-import") (part "G6J-2?-YP"))
    )
    (comp (ref "K42")
      (value "G6J-2P-Y")
      (footprint "eagle-import:G6J-2P-Y")
      (fields (field (name "MF") "OMRON COMPONENTS USA") (field (name "MPN") "G6J-2P-Y-DC12"))
      (libsource (lib "eagle-import") (part "G6J-2?-YP"))
    )
    (comp (ref "K43")
      (value "G6J-2P-Y")
      (footprint "eagle-import:G6J-2P-Y")
      (fields (field (name "MF") "OMRON COMPONENTS USA") (field (name "MPN") "G6J-2P-Y-DC12"))
      (libsource (lib "eagle-import") (part "G6J-2?-YP"))
    )
    (comp (ref "K44")
      (value "G6J-2P-Y")
      (footprint "eagle-import:G6J-2P-Y")
      (fields (field (name "MF") "OMRON COMPONENTS USA") (field (name "MPN") "G6J-2P-Y-DC12"))
      (libsource (lib "eagle-import") (part "G6J-2?-YP"))
    )
    (comp (ref "K45")
      (value "G6J-2P-Y")
      (footprint "eagle-import:G6J-2P-Y")
      (fields (field (name "MF") "OMRON COMPONENTS USA") (field (name "MPN") "G6J-2P-Y-DC12"))
      (libsource (lib "eagle-import") (part "G6J-2?-YP"))
    )
    (comp (ref "K46")
      (value "G6J-2P-Y")
      (footprint "eagle-import:G6J-2P-Y")
      (fields (field (name "MF") "OMRON COMPONENTS USA") (field (name "MPN") "G6J-2P-Y-DC12"))
      (libsource (lib "eagle-import") (part "G6J-2?-YP"))
    )
    (comp (ref "K47")
      (value "G6J-2P-Y")
      (footprint "eagle-import:G6J-2P-Y")
      (fields (field (name "MF") "OMRON COMPONENTS USA") (field (name "MPN") "G6J-2P-Y-DC12"))
      (libsource (lib "eagle-import") (part "G6J-2?-YP"))
    )
    (comp (ref "K48")
      (value "G6J-2P-Y")
      (footprint "eagle-import:G6J-2P-Y")
      (fields (field (name "MF") "OMRON COMPONENTS USA") (field (name "MPN") "G6J-2P-Y-DC12"))
      (libsource (lib "eagle-import") (part "G6J-2?-YP"))
    )
    (comp (ref "K49")
      (value "G6J-2P-Y")
      (footprint "eagle-import:G6J-2P-Y")
      (fields (field (name "MF") "OMRON COMPONENTS USA") (field (name "MPN") "G6J-2P-Y-DC12"))
      (libsource (lib "eagle-import") (part "G6J-2?-YP"))
    )
    (comp (ref "K50")
      (value "G6J-2P-Y")
      (footprint "eagle-import:G6J-2P-Y")
      (fields (field (name "MF") "OMRON COMPONENTS USA") (field (name "MPN") "G6J-2P-Y-DC12"))
      (libsource (lib "eagle-import") (part "G6J-2?-YP"))
    )
    (comp (ref "K51")
      (value "G6J-2P-Y")
      (footprint "eagle-import:G6J-2P-Y")
      (fields (field (name "MF") "OMRON COMPONENTS USA") (field (name "MPN") "G6J-2P-Y-DC12"))
      (libsource (lib "eagle-import") (part "G6J-2?-YP"))
    )
    (comp (ref "K52")
      (value "G6J-2P-Y")
      (footprint "eagle-import:G6J-2P-Y")
      (fields (field (name "MF") "OMRON COMPONENTS USA") (field (name "MPN") "G6J-2P-Y-DC12"))
      (libsource (lib "eagle-import") (part "G6J-2?-YP"))
    )
    (comp (ref "K53")
      (value "G6J-2P-Y")
      (footprint "eagle-import:G6J-2P-Y")
      (fields (field (name "MF") "OMRON COMPONENTS USA") (field (name "MPN") "G6J-2P-Y-DC12"))
      (libsource (lib "eagle-import") (part "G6J-2?-YP"))
    )
    (comp (ref "K54")
      (value "G6J-2P-Y")
      (footprint "eagle-import:G6J-2P-Y")
      (fields (field (name "MF") "OMRON COMPONENTS USA") (field (name "MPN") "G6J-2P-Y-DC12"))
      (libsource (lib "eagle-import") (part "G6J-2?-YP"))
    )
    (comp (ref "K55")
      (value "G6J-2P-Y")
      (footprint "eagle-import:G6J-2P-Y")
      (fields (field (name "MF") "OMRON COMPONENTS USA") (field (name "MPN") "G6J-2P-Y-DC12"))
      (libsource (lib "eagle-import") (part "G6J-2?-YP"))
    )
    (comp (ref "K56")
      (value "G6J-2P-Y")
      (footprint "eagle-import:G6J-2P-Y")
      (fields (field (name "MF") "OMRON COMPONENTS USA") (field (name "MPN") "G6J-2P-Y-DC12"))
      (libsource (lib "eagle-import") (part "G6J-2?-YP"))
    )
    (comp (ref "K57")
      (value "G6J-2P-Y")
      (footprint "eagle-import:G6J-2P-Y")
      (fields (field (name "MF") "OMRON COMPONENTS USA") (field (name "MPN") "G6J-2P-Y-DC12"))
      (libsource (lib "eagle-import") (part "G6J-2?-YP"))
    )
    (comp (ref "K58")
      (value "G6J-2P-Y")
      (footprint "eagle-import:G6J-2P-Y")
      (fields (field (name "MF") "OMRON COMPONENTS USA") (field (name "MPN") "G6J-2P-Y-DC12"))
      (libsource (lib "eagle-import") (part "G6J-2?-YP"))
    )
    (comp (ref "K59")
      (value "G6J-2P-Y")
      (footprint "eagle-import:G6J-2P-Y")
      (fields (field (name "MF") "OMRON COMPONENTS USA") (field (name "MPN") "G6J-2P-Y-DC12"))
      (libsource (lib "eagle-import") (part "G6J-2?-YP"))
    )
    (comp (ref "K60")
      (value "G6J-2P-Y")
      (footprint "eagle-import:G6J-2P-Y")
      (fields (field (name "MF") "OMRON COMPONENTS USA") (field (name "MPN") "G6J-2P-Y-DC12"))
      (libsource (lib "eagle-import") (part "G6J-2?-YP"))
    )
    (comp (ref "K61")
      (value "G6J-2P-Y")
      (footprint "eagle-import:G6J-2P-Y")
      (fields (field (name "MF") "OMRON COMPONENTS USA") (field (name "MPN") "G6J-2P-Y-DC12"))
      (libsource (lib "eagle-import") (part "G6J-2?-YP"))
    )
    (comp (ref "K62")
      (value "G6J-2P-Y")
      (footprint "eagle-import:G6J-2P-Y")
      (fields (field (name "MF") "OMRON COMPONENTS USA") (field (name "MPN") "G6J-2P-Y-DC12"))
      (libsource (lib "eagle-import") (part "G6J-2?-YP"))
    )
    (comp (ref "K63")
      (value "G5V-2")
      (footprint "eagle-import:G5V-2")
      (fields (field (name "MPN") "G5V-2 5DC"))
      (libsource (lib "eagle-import") (part "G5V-2"))
    )
    (comp (ref "K64")
      (value "G6J-2P-Y")
      (footprint "eagle-import:G6J-2P-Y")
      (fields (field (name "MF") "OMRON COMPONENTS USA") (field (name "MPN") "G6J-2P-Y-DC12"))
      (libsource (lib "eagle-import") (part "G6J-2?-YP"))
    )
    (comp (ref "K65")
      (value "G6J-2P-Y")
      (footprint "eagle-import:G6J-2P-Y")
      (fields (field (name "MF") "OMRON COMPONENTS USA") (field (name "MPN") "G6J-2P-Y-DC12"))
      (libsource (lib "eagle-import") (part "G6J-2?-YP"))
    )
    (comp (ref "K66")
      (value "G5V-2")
      (footprint "eagle-import:G5V-2")
      (fields (field (name "MPN") "G5V-2 5DC"))
      (libsource (lib "eagle-import") (part "G5V-2"))
    )
    (comp (ref "K67")
      (value "G6J-2P-Y")
      (footprint "eagle-import:G6J-2P-Y")
      (fields (field (name "MF") "OMRON COMPONENTS USA") (field (name "MPN") "G6J-2P-Y-DC12"))
      (libsource (lib "eagle-import") (part "G6J-2?-YP"))
    )
    (comp (ref "K68")
      (value "G5V-2")
      (footprint "eagle-import:G5V-2")
      (fields (field (name "MPN") "G5V-2 5DC"))
      (libsource (lib "eagle-import") (part "G5V-2"))
    )
    (comp (ref "K69")
      (value "G6J-2P-Y")
      (footprint "eagle-import:G6J-2P-Y")
      (fields (field (name "MF") "OMRON COMPONENTS USA") (field (name "MPN") "G6J-2P-Y-DC12"))
      (libsource (lib "eagle-import") (part "G6J-2?-YP"))
    )
    (comp (ref "K70")
      (value "G6J-2P-Y")
      (footprint "eagle-import:G6J-2P-Y")
      (fields (field (name "MF") "OMRON COMPONENTS USA") (field (name "MPN") "G6J-2P-Y-DC12"))
      (libsource (lib "eagle-import") (part "G6J-2?-YP"))
    )
    (comp (ref "K71")
      (value "G5V-2")
      (footprint "eagle-import:G5V-2")
      (fields (field (name "MPN") "G5V-2 5DC"))
      (libsource (lib "eagle-import") (part "G5V-2"))
    )
    (comp (ref "K72")
      (value "G6J-2P-Y")
      (footprint "eagle-import:G6J-2P-Y")
      (fields (field (name "MF") "OMRON COMPONENTS USA") (field (name "MPN") "G6J-2P-Y-DC12"))
      (libsource (lib "eagle-import") (part "G6J-2?-YP"))
    )
    (comp (ref "K73")
      (value "G6J-2P-Y")
      (footprint "eagle-import:G6J-2P-Y")
      (fields (field (name "MF") "OMRON COMPONENTS USA") (field (name "MPN") "G6J-2P-Y-DC12"))
      (libsource (lib "eagle-import") (part "G6J-2?-YP"))
    )
    (comp (ref "K74")
      (value "G6J-2P-Y")
      (footprint "eagle-import:G6J-2P-Y")
      (fields (field (name "MF") "OMRON COMPONENTS USA") (field (name "MPN") "G6J-2P-Y-DC12"))
      (libsource (lib "eagle-import") (part "G6J-2?-YP"))
    )
    (comp (ref "K75")
      (value "G6J-2P-Y")
      (footprint "eagle-import:G6J-2P-Y")
      (fields (field (name "MF") "OMRON COMPONENTS USA") (field (name "MPN") "G6J-2P-Y-DC12"))
      (libsource (lib "eagle-import") (part "G6J-2?-YP"))
    )
    (comp (ref "K76")
      (value "G6J-2P-Y")
      (footprint "eagle-import:G6J-2P-Y")
      (fields (field (name "MF") "OMRON COMPONENTS USA") (field (name "MPN") "G6J-2P-Y-DC12"))
      (libsource (lib "eagle-import") (part "G6J-2?-YP"))
    )
    (comp (ref "K77")
      (value "G6J-2P-Y")
      (footprint "eagle-import:G6J-2P-Y")
      (fields (field (name "MF") "OMRON COMPONENTS USA") (field (name "MPN") "G6J-2P-Y-DC12"))
      (libsource (lib "eagle-import") (part "G6J-2?-YP"))
    )
    (comp (ref "K78")
      (value "G6J-2P-Y")
      (footprint "eagle-import:G6J-2P-Y")
      (fields (field (name "MF") "OMRON COMPONENTS USA") (field (name "MPN") "G6J-2P-Y-DC12"))
      (libsource (lib "eagle-import") (part "G6J-2?-YP"))
    )
    (comp (ref "K79")
      (value "G6J-2P-Y")
      (footprint "eagle-import:G6J-2P-Y")
      (fields (field (name "MF") "OMRON COMPONENTS USA") (field (name "MPN") "G6J-2P-Y-DC12"))
      (libsource (lib "eagle-import") (part "G6J-2?-YP"))
    )
    (comp (ref "K80")
      (value "G6J-2P-Y")
      (footprint "eagle-import:G6J-2P-Y")
      (fields (field (name "MF") "OMRON COMPONENTS USA") (field (name "MPN") "G6J-2P-Y-DC12"))
      (libsource (lib "eagle-import") (part "G6J-2?-YP"))
    )
    (comp (ref "K81")
      (value "G6J-2P-Y")
      (footprint "eagle-import:G6J-2P-Y")
      (fields (field (name "MF") "OMRON COMPONENTS USA") (field (name "MPN") "G6J-2P-Y-DC12"))
      (libsource (lib "eagle-import") (part "G6J-2?-YP"))
    )
    (comp (ref "K82")
      (value "G6J-2P-Y")
      (footprint "eagle-import:G6J-2P-Y")
      (fields (field (name "MF") "OMRON COMPONENTS USA") (field (name "MPN") "G6J-2P-Y-DC12"))
      (libsource (lib "eagle-import") (part "G6J-2?-YP"))
    )
    (comp (ref "K83")
      (value "G6J-2P-Y")
      (footprint "eagle-import:G6J-2P-Y")
      (fields (field (name "MF") "OMRON COMPONENTS USA") (field (name "MPN") "G6J-2P-Y-DC12"))
      (libsource (lib "eagle-import") (part "G6J-2?-YP"))
    )
    (comp (ref "K84")
      (value "G6J-2P-Y")
      (footprint "eagle-import:G6J-2P-Y")
      (fields (field (name "MF") "OMRON COMPONENTS USA") (field (name "MPN") "G6J-2P-Y-DC12"))
      (libsource (lib "eagle-import") (part "G6J-2?-YP"))
    )
    (comp (ref "K85")
      (value "G6J-2P-Y")
      (footprint "eagle-import:G6J-2P-Y")
      (fields (field (name "MF") "OMRON COMPONENTS USA") (field (name "MPN") "G6J-2P-Y-DC12"))
      (libsource (lib "eagle-import") (part "G6J-2?-YP"))
    )
    (comp (ref "K86")
      (value "G6J-2P-Y")
      (footprint "eagle-import:G6J-2P-Y")
      (fields (field (name "MF") "OMRON COMPONENTS USA") (field (name "MPN") "G6J-2P-Y-DC12"))
      (libsource (lib "eagle-import") (part "G6J-2?-YP"))
    )
    (comp (ref "K87")
      (value "G6J-2P-Y")
      (footprint "eagle-import:G6J-2P-Y")
      (fields (field (name "MF") "OMRON COMPONENTS USA") (field (name "MPN") "G6J-2P-Y-DC12"))
      (libsource (lib "eagle-import") (part "G6J-2?-YP"))
    )
    (comp (ref "K88")
      (value "G6J-2P-Y")
      (footprint "eagle-import:G6J-2P-Y")
      (fields (field (name "MF") "OMRON COMPONENTS USA") (field (name "MPN") "G6J-2P-Y-DC12"))
      (libsource (lib "eagle-import") (part "G6J-2?-YP"))
    )
    (comp (ref "K89")
      (value "G6J-2P-Y")
      (footprint "eagle-import:G6J-2P-Y")
      (fields (field (name "MF") "OMRON COMPONENTS USA") (field (name "MPN") "G6J-2P-Y-DC12"))
      (libsource (lib "eagle-import") (part "G6J-2?-YP"))
    )
    (comp (ref "K90")
      (value "G6J-2P-Y")
      (footprint "eagle-import:G6J-2P-Y")
      (fields (field (name "MF") "OMRON COMPONENTS USA") (field (name "MPN") "G6J-2P-Y-DC12"))
      (libsource (lib "eagle-import") (part "G6J-2?-YP"))
    )
    (comp (ref "K91")
      (value "G6J-2P-Y")
      (footprint "eagle-import:G6J-2P-Y")
      (fields (field (name "MF") "OMRON COMPONENTS USA") (field (name "MPN") "G6J-2P-Y-DC12"))
      (libsource (lib "eagle-import") (part "G6J-2?-YP"))
    )
    (comp (ref "K92")
      (value "G6J-2P-Y")
      (footprint "eagle-import:G6J-2P-Y")
      (fields (field (name "MF") "OMRON COMPONENTS USA") (field (name "MPN") "G6J-2P-Y-DC12"))
      (libsource (lib "eagle-import") (part "G6J-2?-YP"))
    )
    (comp (ref "K93")
      (value "G6J-2P-Y")
      (footprint "eagle-import:G6J-2P-Y")
      (fields (field (name "MF") "OMRON COMPONENTS USA") (field (name "MPN") "G6J-2P-Y-DC12"))
      (libsource (lib "eagle-import") (part "G6J-2?-YP"))
    )
    (comp (ref "K94")
      (value "G6J-2P-Y")
      (footprint "eagle-import:G6J-2P-Y")
      (fields (field (name "MF") "OMRON COMPONENTS USA") (field (name "MPN") "G6J-2P-Y-DC12"))
      (libsource (lib "eagle-import") (part "G6J-2?-YP"))
    )
    (comp (ref "K95")
      (value "G6J-2P-Y")
      (footprint "eagle-import:G6J-2P-Y")
      (fields (field (name "MF") "OMRON COMPONENTS USA") (field (name "MPN") "G6J-2P-Y-DC12"))
      (libsource (lib "eagle-import") (part "G6J-2?-YP"))
    )
    (comp (ref "K96")
      (value "G6J-2P-Y")
      (footprint "eagle-import:G6J-2P-Y")
      (fields (field (name "MF") "OMRON COMPONENTS USA") (field (name "MPN") "G6J-2P-Y-DC12"))
      (libsource (lib "eagle-import") (part "G6J-2?-YP"))
    )
    (comp (ref "K97")
      (value "G6J-2P-Y")
      (footprint "eagle-import:G6J-2P-Y")
      (fields (field (name "MF") "OMRON COMPONENTS USA") (field (name "MPN") "G6J-2P-Y-DC12"))
      (libsource (lib "eagle-import") (part "G6J-2?-YP"))
    )
    (comp (ref "K98")
      (value "G6J-2P-Y")
      (footprint "eagle-import:G6J-2P-Y")
      (fields (field (name "MF") "OMRON COMPONENTS USA") (field (name "MPN") "G6J-2P-Y-DC12"))
      (libsource (lib "eagle-import") (part "G6J-2?-YP"))
    )
    (comp (ref "K99")
      (value "G6J-2P-Y")
      (footprint "eagle-import:G6J-2P-Y")
      (fields (field (name "MF") "OMRON COMPONENTS USA") (field (name "MPN") "G6J-2P-Y-DC12"))
      (libsource (lib "eagle-import") (part "G6J-2?-YP"))
    )
    (comp (ref "K100")
      (value "G6J-2P-Y")
      (footprint "eagle-import:G6J-2P-Y")
      (fields (field (name "MF") "OMRON COMPONENTS USA") (field (name "MPN") "G6J-2P-Y-DC12"))
      (libsource (lib "eagle-import") (part "G6J-2?-YP"))
    )
    (comp (ref "LED1")
      (value "LED5MM")
      (footprint "eagle-import:LED5MM")
      (libsource (lib "eagle-import") (part "LED5MM"))
    )
    (comp (ref "LED2")
      (value "LED5MM")
      (footprint "eagle-import:LED5MM")
      (libsource (lib "eagle-import") (part "LED5MM"))
    )
    (comp (ref "LED3")
      (value "LED5MM")
      (footprint "eagle-import:LED5MM")
      (libsource (lib "eagle-import") (part "LED5MM"))
    )
    (comp (ref "LED4")
      (value "LED5MM")
      (footprint "eagle-import:LED5MM")
      (libsource (lib "eagle-import") (part "LED5MM"))
    )
    (comp (ref "LED5")
      (value "LED5MM")
      (footprint "eagle-import:LED5MM")
      (libsource (lib "eagle-import") (part "LED5MM"))
    )
    (comp (ref "LED6")
      (value "LED5MM")
      (footprint "eagle-import:LED5MM")
      (libsource (lib "eagle-import") (part "LED5MM"))
    )
    (comp (ref "LED7")
      (value "LED5MM")
      (footprint "eagle-import:LED5MM")
      (libsource (lib "eagle-import") (part "LED5MM"))
    )
    (comp (ref "LED8")
      (value "LED5MM")
      (footprint "eagle-import:LED5MM")
      (libsource (lib "eagle-import") (part "LED5MM"))
    )
    (comp (ref "LED9")
      (value "LED5MM")
      (footprint "eagle-import:LED5MM")
      (libsource (lib "eagle-import") (part "LED5MM"))
    )
    (comp (ref "LED10")
      (value "LED5MM")
      (footprint "eagle-import:LED5MM")
      (libsource (lib "eagle-import") (part "LED5MM"))
    )
    (comp (ref "LED11")
      (value "LED5MM")
      (footprint "eagle-import:LED5MM")
      (libsource (lib "eagle-import") (part "LED5MM"))
    )
    (comp (ref "LED12")
      (value "LED5MM")
      (footprint "eagle-import:LED5MM")
      (libsource (lib "eagle-import") (part "LED5MM"))
    )
    (comp (ref "LED13")
      (value "LED5MM")
      (footprint "eagle-import:LED5MM")
      (libsource (lib "eagle-import") (part "LED5MM"))
    )
    (comp (ref "LED14")
      (value "LED5MM")
      (footprint "eagle-import:LED5MM")
      (libsource (lib "eagle-import") (part "LED5MM"))
    )
    (comp (ref "LED15")
      (value "LED5MM")
      (footprint "eagle-import:LED5MM")
      (libsource (lib "eagle-import") (part "LED5MM"))
    )
    (comp (ref "LED16")
      (value "LED5MM")
      (footprint "eagle-import:LED5MM")
      (libsource (lib "eagle-import") (part "LED5MM"))
    )
    (comp (ref "LED17")
      (value "LED5MM")
      (footprint "eagle-import:LED5MM")
      (libsource (lib "eagle-import") (part "LED5MM"))
    )
    (comp (ref "LED18")
      (value "LED5MM")
      (footprint "eagle-import:LED5MM")
      (libsource (lib "eagle-import") (part "LED5MM"))
    )
    (comp (ref "LED19")
      (value "LED5MM")
      (footprint "eagle-import:LED5MM")
      (libsource (lib "eagle-import") (part "LED5MM"))
    )
    (comp (ref "LED20")
      (value "LED5MM")
      (footprint "eagle-import:LED5MM")
      (libsource (lib "eagle-import") (part "LED5MM"))
    )
    (comp (ref "LED21")
      (value "LED5MM")
      (footprint "eagle-import:LED5MM")
      (libsource (lib "eagle-import") (part "LED5MM"))
    )
    (comp (ref "LED22")
      (value "LED5MM")
      (footprint "eagle-import:LED5MM")
      (libsource (lib "eagle-import") (part "LED5MM"))
    )
    (comp (ref "LED23")
      (value "LED5MM")
      (footprint "eagle-import:LED5MM")
      (libsource (lib "eagle-import") (part "LED5MM"))
    )
    (comp (ref "LED24")
      (value "LED5MM")
      (footprint "eagle-import:LED5MM")
      (libsource (lib "eagle-import") (part "LED5MM"))
    )
    (comp (ref "LED25")
      (value "LED3MM")
      (footprint "eagle-import:LED3MM")
      (libsource (lib "eagle-import") (part "LED3MM"))
    )
    (comp (ref "LED26")
      (value "LED3MM")
      (footprint "eagle-import:LED3MM")
      (libsource (lib "eagle-import") (part "LED3MM"))
    )
    (comp (ref "LED27")
      (value "LED3MM")
      (footprint "eagle-import:LED3MM")
      (libsource (lib "eagle-import") (part "LED3MM"))
    )
    (comp (ref "LED28")
      (value "LED3MM")
      (footprint "eagle-import:LED3MM")
      (libsource (lib "eagle-import") (part "LED3MM"))
    )
    (comp (ref "LED29")
      (value "LED3MM")
      (footprint "eagle-import:LED3MM")
      (libsource (lib "eagle-import") (part "LED3MM"))
    )
    (comp (ref "LED30")
      (value "LED3MM")
      (footprint "eagle-import:LED3MM")
      (libsource (lib "eagle-import") (part "LED3MM"))
    )
    (comp (ref "LED31")
      (value "LED3MM")
      (footprint "eagle-import:LED3MM")
      (libsource (lib "eagle-import") (part "LED3MM"))
    )
    (comp (ref "LED32")
      (value "LED3MM")
      (footprint "eagle-import:LED3MM")
      (libsource (lib "eagle-import") (part "LED3MM"))
    )
    (comp (ref "LED33")
      (value "LED3MM")
      (footprint "eagle-import:LED3MM")
      (libsource (lib "eagle-import") (part "LED3MM"))
    )
    (comp (ref "LED34")
      (value "LED3MM")
      (footprint "eagle-import:LED3MM")
      (libsource (lib "eagle-import") (part "LED3MM"))
    )
    (comp (ref "LED35")
      (value "LED3MM")
      (footprint "eagle-import:LED3MM")
      (libsource (lib "eagle-import") (part "LED3MM"))
    )
    (comp (ref "LED36")
      (value "LED3MM")
      (footprint "eagle-import:LED3MM")
      (libsource (lib "eagle-import") (part "LED3MM"))
    )
    (comp (ref "LED37")
      (value "LED3MM")
      (footprint "eagle-import:LED3MM")
      (libsource (lib "eagle-import") (part "LED3MM"))
    )
    (comp (ref "R1")
      (value "R-EU_0204/2V")
      (footprint "eagle-import:0204V")
      (libsource (lib "eagle-import") (part "R-EU_0204/2V"))
    )
    (comp (ref "R2")
      (value "R-EU_0204/2V")
      (footprint "eagle-import:0204V")
      (libsource (lib "eagle-import") (part "R-EU_0204/2V"))
    )
    (comp (ref "R3")
      (value "R-EU_0204/2V")
      (footprint "eagle-import:0204V")
      (libsource (lib "eagle-import") (part "R-EU_0204/2V"))
    )
    (comp (ref "R4")
      (value "R-EU_0204/2V")
      (footprint "eagle-import:0204V")
      (libsource (lib "eagle-import") (part "R-EU_0204/2V"))
    )
    (comp (ref "R5")
      (value "R-EU_0204/2V")
      (footprint "eagle-import:0204V")
      (libsource (lib "eagle-import") (part "R-EU_0204/2V"))
    )
    (comp (ref "R6")
      (value "R-EU_0204/2V")
      (footprint "eagle-import:0204V")
      (libsource (lib "eagle-import") (part "R-EU_0204/2V"))
    )
    (comp (ref "R7")
      (value "R-EU_0204/2V")
      (footprint "eagle-import:0204V")
      (libsource (lib "eagle-import") (part "R-EU_0204/2V"))
    )
    (comp (ref "R8")
      (value "R-EU_0204/2V")
      (footprint "eagle-import:0204V")
      (libsource (lib "eagle-import") (part "R-EU_0204/2V"))
    )
    (comp (ref "R9")
      (value "R-EU_0204/2V")
      (footprint "eagle-import:0204V")
      (libsource (lib "eagle-import") (part "R-EU_0204/2V"))
    )
    (comp (ref "R10")
      (value "R-EU_0204/2V")
      (footprint "eagle-import:0204V")
      (libsource (lib "eagle-import") (part "R-EU_0204/2V"))
    )
    (comp (ref "R11")
      (value "R-EU_0204/2V")
      (footprint "eagle-import:0204V")
      (libsource (lib "eagle-import") (part "R-EU_0204/2V"))
    )
    (comp (ref "R12")
      (value "R-EU_0204/2V")
      (footprint "eagle-import:0204V")
      (libsource (lib "eagle-import") (part "R-EU_0204/2V"))
    )
    (comp (ref "R13")
      (value "R-EU_0204/2V")
      (footprint "eagle-import:0204V")
      (libsource (lib "eagle-import") (part "R-EU_0204/2V"))
    )
    (comp (ref "R14")
      (value "R-EU_0204/2V")
      (footprint "eagle-import:0204V")
      (libsource (lib "eagle-import") (part "R-EU_0204/2V"))
    )
    (comp (ref "R15")
      (value "R-EU_0204/2V")
      (footprint "eagle-import:0204V")
      (libsource (lib "eagle-import") (part "R-EU_0204/2V"))
    )
    (comp (ref "R16")
      (value "R-EU_0204/2V")
      (footprint "eagle-import:0204V")
      (libsource (lib "eagle-import") (part "R-EU_0204/2V"))
    )
    (comp (ref "R17")
      (value "R-EU_0204/2V")
      (footprint "eagle-import:0204V")
      (libsource (lib "eagle-import") (part "R-EU_0204/2V"))
    )
    (comp (ref "R18")
      (value "R-EU_0204/2V")
      (footprint "eagle-import:0204V")
      (libsource (lib "eagle-import") (part "R-EU_0204/2V"))
    )
    (comp (ref "R19")
      (value "R-EU_0204/2V")
      (footprint "eagle-import:0204V")
      (libsource (lib "eagle-import") (part "R-EU_0204/2V"))
    )
    (comp (ref "R20")
      (value "R-EU_0204/2V")
      (footprint "eagle-import:0204V")
      (libsource (lib "eagle-import") (part "R-EU_0204/2V"))
    )
    (comp (ref "R21")
      (value "R-EU_0204/2V")
      (footprint "eagle-import:0204V")
      (libsource (lib "eagle-import") (part "R-EU_0204/2V"))
    )
    (comp (ref "R22")
      (value "R-EU_0204/2V")
      (footprint "eagle-import:0204V")
      (libsource (lib "eagle-import") (part "R-EU_0204/2V"))
    )
    (comp (ref "R23")
      (value "R-EU_0204/2V")
      (footprint "eagle-import:0204V")
      (libsource (lib "eagle-import") (part "R-EU_0204/2V"))
    )
    (comp (ref "R24")
      (value "R-EU_0204/2V")
      (footprint "eagle-import:0204V")
      (libsource (lib "eagle-import") (part "R-EU_0204/2V"))
    )
    (comp (ref "R25")
      (value "R-EU_0204/2V")
      (footprint "eagle-import:0204V")
      (libsource (lib "eagle-import") (part "R-EU_0204/2V"))
    )
    (comp (ref "R26")
      (value "R-EU_0204/2V")
      (footprint "eagle-import:0204V")
      (libsource (lib "eagle-import") (part "R-EU_0204/2V"))
    )
    (comp (ref "R27")
      (value "R-EU_0204/2V")
      (footprint "eagle-import:0204V")
      (libsource (lib "eagle-import") (part "R-EU_0204/2V"))
    )
    (comp (ref "R28")
      (value "R-EU_0204/2V")
      (footprint "eagle-import:0204V")
      (libsource (lib "eagle-import") (part "R-EU_0204/2V"))
    )
    (comp (ref "R29")
      (value "R-EU_0204/2V")
      (footprint "eagle-import:0204V")
      (libsource (lib "eagle-import") (part "R-EU_0204/2V"))
    )
    (comp (ref "R30")
      (value "R-EU_0204/2V")
      (footprint "eagle-import:0204V")
      (libsource (lib "eagle-import") (part "R-EU_0204/2V"))
    )
    (comp (ref "R31")
      (value "R-EU_0204/2V")
      (footprint "eagle-import:0204V")
      (libsource (lib "eagle-import") (part "R-EU_0204/2V"))
    )
    (comp (ref "R32")
      (value "R-EU_0204/2V")
      (footprint "eagle-import:0204V")
      (libsource (lib "eagle-import") (part "R-EU_0204/2V"))
    )
    (comp (ref "R33")
      (value "R-EU_0204/2V")
      (footprint "eagle-import:0204V")
      (libsource (lib "eagle-import") (part "R-EU_0204/2V"))
    )
    (comp (ref "R34")
      (value "R-EU_0204/2V")
      (footprint "eagle-import:0204V")
      (libsource (lib "eagle-import") (part "R-EU_0204/2V"))
    )
    (comp (ref "R35")
      (value "R-EU_0204/2V")
      (footprint "eagle-import:0204V")
      (libsource (lib "eagle-import") (part "R-EU_0204/2V"))
    )
    (comp (ref "R36")
      (value "R-EU_0204/2V")
      (footprint "eagle-import:0204V")
      (libsource (lib "eagle-import") (part "R-EU_0204/2V"))
    )
    (comp (ref "R37")
      (value "R-EU_0204/2V")
      (footprint "eagle-import:0204V")
      (libsource (lib "eagle-import") (part "R-EU_0204/2V"))
    )
    (comp (ref "R38")
      (value "R-EU_0204/2V")
      (footprint "eagle-import:0204V")
      (libsource (lib "eagle-import") (part "R-EU_0204/2V"))
    )
    (comp (ref "R39")
      (value "R-EU_0204/2V")
      (footprint "eagle-import:0204V")
      (libsource (lib "eagle-import") (part "R-EU_0204/2V"))
    )
    (comp (ref "R40")
      (value "R-EU_0204/2V")
      (footprint "eagle-import:0204V")
      (libsource (lib "eagle-import") (part "R-EU_0204/2V"))
    )
    (comp (ref "R41")
      (value "R-EU_0204/2V")
      (footprint "eagle-import:0204V")
      (libsource (lib "eagle-import") (part "R-EU_0204/2V"))
    )
    (comp (ref "R42")
      (value "R-EU_0204/2V")
      (footprint "eagle-import:0204V")
      (libsource (lib "eagle-import") (part "R-EU_0204/2V"))
    )
    (comp (ref "R43")
      (value "R-EU_0204/2V")
      (footprint "eagle-import:0204V")
      (libsource (lib "eagle-import") (part "R-EU_0204/2V"))
    )
    (comp (ref "R44")
      (value "R-EU_0204/2V")
      (footprint "eagle-import:0204V")
      (libsource (lib "eagle-import") (part "R-EU_0204/2V"))
    )
    (comp (ref "R45")
      (value "R-EU_0204/2V")
      (footprint "eagle-import:0204V")
      (libsource (lib "eagle-import") (part "R-EU_0204/2V"))
    )
    (comp (ref "R46")
      (value "R-EU_0204/2V")
      (footprint "eagle-import:0204V")
      (libsource (lib "eagle-import") (part "R-EU_0204/2V"))
    )
    (comp (ref "X1")
      (value "1751248")
      (footprint "eagle-import:1751248")
      (libsource (lib "eagle-import") (part "1751248"))
    )
  )
  (nets
    (net (code "1") (name "/A_B_SELECTOR") (class "Default")
      (node (ref "D33") (pin "A") (pinfunction "A_A") (pintype "passive"))
      (node (ref "D49") (pin "A") (pinfunction "A_A") (pintype "passive"))
      (node (ref "K83") (pin "1") (pinfunction "+_1") (pintype "passive"))
      (node (ref "K84") (pin "1") (pinfunction "+_1") (pintype "passive"))
    )
    (net (code "2") (name "/CLK1") (class "Default")
      (node (ref "D29") (pin "A") (pinfunction "A_A") (pintype "passive"))
      (node (ref "D36") (pin "A") (pinfunction "A_A") (pintype "passive"))
      (node (ref "K1") (pin "4") (pinfunction "S_4") (pintype "passive"))
      (node (ref "K97") (pin "1") (pinfunction "+_1") (pintype "passive"))
      (node (ref "R3") (pin "2") (pinfunction "2_2") (pintype "passive"))
    )
    (net (code "3") (name "/CLK2") (class "Default")
      (node (ref "D30") (pin "A") (pinfunction "A_A") (pintype "passive"))
      (node (ref "D39") (pin "A") (pinfunction "A_A") (pintype "passive"))
      (node (ref "D46") (pin "A") (pinfunction "A_A") (pintype "passive"))
      (node (ref "K2") (pin "2") (pinfunction "O_2") (pintype "passive"))
      (node (ref "K3") (pin "1") (pinfunction "+_1") (pintype "passive"))
      (node (ref "K3") (pin "5") (pinfunction "S_5") (pintype "passive"))
      (node (ref "K4") (pin "1") (pinfunction "+_1") (pintype "passive"))
      (node (ref "K98") (pin "1") (pinfunction "+_1") (pintype "passive"))
      (node (ref "R2") (pin "2") (pinfunction "2_2") (pintype "passive"))
    )
    (net (code "4") (name "/GND") (class "Default")
      (node (ref "C1") (pin "-") (pinfunction "-_-") (pintype "passive"))
      (node (ref "C2") (pin "-") (pinfunction "-_-") (pintype "passive"))
      (node (ref "C3") (pin "-") (pinfunction "-_-") (pintype "passive"))
      (node (ref "C4") (pin "-") (pinfunction "-_-") (pintype "passive"))
      (node (ref "C5") (pin "-") (pinfunction "-_-") (pintype "passive"))
      (node (ref "K1") (pin "8") (pinfunction "-_8") (pintype "passive"))
      (node (ref "K10") (pin "8") (pinfunction "-_8") (pintype "passive"))
      (node (ref "K100") (pin "4") (pinfunction "S_4") (pintype "passive"))
      (node (ref "K100") (pin "8") (pinfunction "-_8") (pintype "passive"))
      (node (ref "K11") (pin "5") (pinfunction "S_5") (pintype "passive"))
      (node (ref "K12") (pin "8") (pinfunction "-_8") (pintype "passive"))
      (node (ref "K13") (pin "8") (pinfunction "-_8") (pintype "passive"))
      (node (ref "K14") (pin "8") (pinfunction "-_8") (pintype "passive"))
      (node (ref "K15") (pin "5") (pinfunction "S_5") (pintype "passive"))
      (node (ref "K16") (pin "8") (pinfunction "-_8") (pintype "passive"))
      (node (ref "K17") (pin "5") (pinfunction "S_5") (pintype "passive"))
      (node (ref "K18") (pin "8") (pinfunction "-_8") (pintype "passive"))
      (node (ref "K19") (pin "8") (pinfunction "-_8") (pintype "passive"))
      (node (ref "K2") (pin "5") (pinfunction "S_5") (pintype "passive"))
      (node (ref "K3") (pin "8") (pinfunction "-_8") (pintype "passive"))
      (node (ref "K4") (pin "8") (pinfunction "-_8") (pintype "passive"))
      (node (ref "K47") (pin "8") (pinfunction "-_8") (pintype "passive"))
      (node (ref "K48") (pin "8") (pinfunction "-_8") (pintype "passive"))
      (node (ref "K49") (pin "8") (pinfunction "-_8") (pintype "passive"))
      (node (ref "K5") (pin "5") (pinfunction "S_5") (pintype "passive"))
      (node (ref "K50") (pin "8") (pinfunction "-_8") (pintype "passive"))
      (node (ref "K51") (pin "8") (pinfunction "-_8") (pintype "passive"))
      (node (ref "K52") (pin "8") (pinfunction "-_8") (pintype "passive"))
      (node (ref "K53") (pin "8") (pinfunction "-_8") (pintype "passive"))
      (node (ref "K54") (pin "8") (pinfunction "-_8") (pintype "passive"))
      (node (ref "K55") (pin "8") (pinfunction "-_8") (pintype "passive"))
      (node (ref "K56") (pin "8") (pinfunction "-_8") (pintype "passive"))
      (node (ref "K57") (pin "8") (pinfunction "-_8") (pintype "passive"))
      (node (ref "K58") (pin "8") (pinfunction "-_8") (pintype "passive"))
      (node (ref "K59") (pin "8") (pinfunction "-_8") (pintype "passive"))
      (node (ref "K6") (pin "8") (pinfunction "-_8") (pintype "passive"))
      (node (ref "K60") (pin "8") (pinfunction "-_8") (pintype "passive"))
      (node (ref "K61") (pin "8") (pinfunction "-_8") (pintype "passive"))
      (node (ref "K62") (pin "8") (pinfunction "-_8") (pintype "passive"))
      (node (ref "K64") (pin "2") (pinfunction "O_2") (pintype "passive"))
      (node (ref "K64") (pin "7") (pinfunction "O_7") (pintype "passive"))
      (node (ref "K64") (pin "8") (pinfunction "-_8") (pintype "passive"))
      (node (ref "K65") (pin "4") (pinfunction "S_4") (pintype "passive"))
      (node (ref "K65") (pin "8") (pinfunction "-_8") (pintype "passive"))
      (node (ref "K67") (pin "4") (pinfunction "S_4") (pintype "passive"))
      (node (ref "K67") (pin "8") (pinfunction "-_8") (pintype "passive"))
      (node (ref "K69") (pin "2") (pinfunction "O_2") (pintype "passive"))
      (node (ref "K69") (pin "7") (pinfunction "O_7") (pintype "passive"))
      (node (ref "K69") (pin "8") (pinfunction "-_8") (pintype "passive"))
      (node (ref "K7") (pin "5") (pinfunction "S_5") (pintype "passive"))
      (node (ref "K70") (pin "4") (pinfunction "S_4") (pintype "passive"))
      (node (ref "K70") (pin "8") (pinfunction "-_8") (pintype "passive"))
      (node (ref "K72") (pin "4") (pinfunction "S_4") (pintype "passive"))
      (node (ref "K72") (pin "8") (pinfunction "-_8") (pintype "passive"))
      (node (ref "K73") (pin "8") (pinfunction "-_8") (pintype "passive"))
      (node (ref "K74") (pin "7") (pinfunction "O_7") (pintype "passive"))
      (node (ref "K74") (pin "8") (pinfunction "-_8") (pintype "passive"))
      (node (ref "K75") (pin "7") (pinfunction "O_7") (pintype "passive"))
      (node (ref "K75") (pin "8") (pinfunction "-_8") (pintype "passive"))
      (node (ref "K76") (pin "7") (pinfunction "O_7") (pintype "passive"))
      (node (ref "K76") (pin "8") (pinfunction "-_8") (pintype "passive"))
      (node (ref "K77") (pin "7") (pinfunction "O_7") (pintype "passive"))
      (node (ref "K77") (pin "8") (pinfunction "-_8") (pintype "passive"))
      (node (ref "K78") (pin "7") (pinfunction "O_7") (pintype "passive"))
      (node (ref "K78") (pin "8") (pinfunction "-_8") (pintype "passive"))
      (node (ref "K79") (pin "7") (pinfunction "O_7") (pintype "passive"))
      (node (ref "K79") (pin "8") (pinfunction "-_8") (pintype "passive"))
      (node (ref "K8") (pin "8") (pinfunction "-_8") (pintype "passive"))
      (node (ref "K80") (pin "7") (pinfunction "O_7") (pintype "passive"))
      (node (ref "K80") (pin "8") (pinfunction "-_8") (pintype "passive"))
      (node (ref "K81") (pin "7") (pinfunction "O_7") (pintype "passive"))
      (node (ref "K81") (pin "8") (pinfunction "-_8") (pintype "passive"))
      (node (ref "K82") (pin "4") (pinfunction "S_4") (pintype "passive"))
      (node (ref "K82") (pin "8") (pinfunction "-_8") (pintype "passive"))
      (node (ref "K83") (pin "8") (pinfunction "-_8") (pintype "passive"))
      (node (ref "K84") (pin "8") (pinfunction "-_8") (pintype "passive"))
      (node (ref "K85") (pin "7") (pinfunction "O_7") (pintype "passive"))
      (node (ref "K85") (pin "8") (pinfunction "-_8") (pintype "passive"))
      (node (ref "K86") (pin "7") (pinfunction "O_7") (pintype "passive"))
      (node (ref "K86") (pin "8") (pinfunction "-_8") (pintype "passive"))
      (node (ref "K87") (pin "7") (pinfunction "O_7") (pintype "passive"))
      (node (ref "K87") (pin "8") (pinfunction "-_8") (pintype "passive"))
      (node (ref "K88") (pin "7") (pinfunction "O_7") (pintype "passive"))
      (node (ref "K88") (pin "8") (pinfunction "-_8") (pintype "passive"))
      (node (ref "K89") (pin "7") (pinfunction "O_7") (pintype "passive"))
      (node (ref "K89") (pin "8") (pinfunction "-_8") (pintype "passive"))
      (node (ref "K9") (pin "5") (pinfunction "S_5") (pintype "passive"))
      (node (ref "K90") (pin "7") (pinfunction "O_7") (pintype "passive"))
      (node (ref "K90") (pin "8") (pinfunction "-_8") (pintype "passive"))
      (node (ref "K91") (pin "7") (pinfunction "O_7") (pintype "passive"))
      (node (ref "K91") (pin "8") (pinfunction "-_8") (pintype "passive"))
      (node (ref "K92") (pin "7") (pinfunction "O_7") (pintype "passive"))
      (node (ref "K92") (pin "8") (pinfunction "-_8") (pintype "passive"))
      (node (ref "K93") (pin "7") (pinfunction "O_7") (pintype "passive"))
      (node (ref "K93") (pin "8") (pinfunction "-_8") (pintype "passive"))
      (node (ref "K94") (pin "7") (pinfunction "O_7") (pintype "passive"))
      (node (ref "K94") (pin "8") (pinfunction "-_8") (pintype "passive"))
      (node (ref "K95") (pin "8") (pinfunction "-_8") (pintype "passive"))
      (node (ref "K96") (pin "8") (pinfunction "-_8") (pintype "passive"))
      (node (ref "K97") (pin "4") (pinfunction "S_4") (pintype "passive"))
      (node (ref "K97") (pin "8") (pinfunction "-_8") (pintype "passive"))
      (node (ref "K98") (pin "4") (pinfunction "S_4") (pintype "passive"))
      (node (ref "K98") (pin "8") (pinfunction "-_8") (pintype "passive"))
      (node (ref "K99") (pin "4") (pinfunction "S_4") (pintype "passive"))
      (node (ref "K99") (pin "8") (pinfunction "-_8") (pintype "passive"))
      (node (ref "LED1") (pin "K") (pinfunction "C_K") (pintype "passive"))
      (node (ref "LED2") (pin "K") (pinfunction "C_K") (pintype "passive"))
      (node (ref "LED3") (pin "K") (pinfunction "C_K") (pintype "passive"))
      (node (ref "LED4") (pin "K") (pinfunction "C_K") (pintype "passive"))
      (node (ref "LED5") (pin "K") (pinfunction "C_K") (pintype "passive"))
      (node (ref "LED6") (pin "K") (pinfunction "C_K") (pintype "passive"))
      (node (ref "LED7") (pin "K") (pinfunction "C_K") (pintype "passive"))
      (node (ref "LED8") (pin "K") (pinfunction "C_K") (pintype "passive"))
      (node (ref "R26") (pin "1") (pinfunction "1_1") (pintype "passive"))
      (node (ref "R27") (pin "1") (pinfunction "1_1") (pintype "passive"))
      (node (ref "R28") (pin "1") (pinfunction "1_1") (pintype "passive"))
      (node (ref "R29") (pin "1") (pinfunction "1_1") (pintype "passive"))
      (node (ref "R30") (pin "1") (pinfunction "1_1") (pintype "passive"))
      (node (ref "R31") (pin "1") (pinfunction "1_1") (pintype "passive"))
      (node (ref "R32") (pin "1") (pinfunction "1_1") (pintype "passive"))
      (node (ref "R33") (pin "1") (pinfunction "1_1") (pintype "passive"))
      (node (ref "R34") (pin "1") (pinfunction "1_1") (pintype "passive"))
      (node (ref "R35") (pin "1") (pinfunction "1_1") (pintype "passive"))
      (node (ref "R36") (pin "1") (pinfunction "1_1") (pintype "passive"))
      (node (ref "R37") (pin "1") (pinfunction "1_1") (pintype "passive"))
      (node (ref "R38") (pin "1") (pinfunction "1_1") (pintype "passive"))
      (node (ref "R39") (pin "1") (pinfunction "1_1") (pintype "passive"))
      (node (ref "R40") (pin "1") (pinfunction "1_1") (pintype "passive"))
      (node (ref "R41") (pin "1") (pinfunction "1_1") (pintype "passive"))
      (node (ref "R42") (pin "1") (pinfunction "1_1") (pintype "passive"))
      (node (ref "R43") (pin "1") (pinfunction "1_1") (pintype "passive"))
      (node (ref "R44") (pin "1") (pinfunction "1_1") (pintype "passive"))
      (node (ref "R45") (pin "1") (pinfunction "1_1") (pintype "passive"))
      (node (ref "R46") (pin "1") (pinfunction "1_1") (pintype "passive"))
      (node (ref "X1") (pin "1") (pinfunction "K_1") (pintype "passive"))
    )
    (net (code "5") (name "/HCF-") (class "Default")
      (node (ref "D31") (pin "C") (pinfunction "C_C") (pintype "passive"))
      (node (ref "D32") (pin "C") (pinfunction "C_C") (pintype "passive"))
      (node (ref "D33") (pin "C") (pinfunction "C_C") (pintype "passive"))
      (node (ref "D34") (pin "C") (pinfunction "C_C") (pintype "passive"))
      (node (ref "D35") (pin "C") (pinfunction "C_C") (pintype "passive"))
      (node (ref "K1") (pin "3") (pinfunction "P_3") (pintype "passive"))
      (node (ref "K2") (pin "1") (pinfunction "+_1") (pintype "passive"))
      (node (ref "K2") (pin "7") (pinfunction "O_7") (pintype "passive"))
      (node (ref "R1") (pin "2") (pinfunction "2_2") (pintype "passive"))
    )
    (net (code "6") (name "/INSTR6") (class "Default")
      (node (ref "D32") (pin "A") (pinfunction "A_A") (pintype "passive"))
      (node (ref "D48") (pin "A") (pinfunction "A_A") (pintype "passive"))
      (node (ref "K100") (pin "1") (pinfunction "+_1") (pintype "passive"))
      (node (ref "K80") (pin "6") (pinfunction "P_6") (pintype "passive"))
    )
    (net (code "7") (name "/INSTR7") (class "Default")
      (node (ref "D31") (pin "A") (pinfunction "A_A") (pintype "passive"))
      (node (ref "D40") (pin "A") (pinfunction "A_A") (pintype "passive"))
      (node (ref "K81") (pin "6") (pinfunction "P_6") (pintype "passive"))
      (node (ref "K99") (pin "1") (pinfunction "+_1") (pintype "passive"))
    )
    (net (code "8") (name "/LATCH_A") (class "Default")
      (node (ref "D38") (pin "C") (pinfunction "C_C") (pintype "passive"))
      (node (ref "D39") (pin "C") (pinfunction "C_C") (pintype "passive"))
      (node (ref "D40") (pin "C") (pinfunction "C_C") (pintype "passive"))
      (node (ref "D41") (pin "C") (pinfunction "C_C") (pintype "passive"))
      (node (ref "K85") (pin "3") (pinfunction "P_3") (pintype "passive"))
      (node (ref "K86") (pin "3") (pinfunction "P_3") (pintype "passive"))
      (node (ref "K87") (pin "3") (pinfunction "P_3") (pintype "passive"))
      (node (ref "K88") (pin "3") (pinfunction "P_3") (pintype "passive"))
      (node (ref "K89") (pin "3") (pinfunction "P_3") (pintype "passive"))
    )
    (net (code "9") (name "/LATCH_INSTR") (class "Default")
      (node (ref "D29") (pin "C") (pinfunction "C_C") (pintype "passive"))
      (node (ref "D30") (pin "C") (pinfunction "C_C") (pintype "passive"))
      (node (ref "K74") (pin "3") (pinfunction "P_3") (pintype "passive"))
      (node (ref "K75") (pin "3") (pinfunction "P_3") (pintype "passive"))
      (node (ref "K76") (pin "3") (pinfunction "P_3") (pintype "passive"))
      (node (ref "K77") (pin "3") (pinfunction "P_3") (pintype "passive"))
      (node (ref "K78") (pin "3") (pinfunction "P_3") (pintype "passive"))
      (node (ref "K79") (pin "3") (pinfunction "P_3") (pintype "passive"))
      (node (ref "K80") (pin "3") (pinfunction "P_3") (pintype "passive"))
      (node (ref "K81") (pin "3") (pinfunction "P_3") (pintype "passive"))
    )
    (net (code "10") (name "/LATCH_PC-") (class "Default")
      (node (ref "D42") (pin "C") (pinfunction "C_C") (pintype "passive"))
      (node (ref "D43") (pin "C") (pinfunction "C_C") (pintype "passive"))
      (node (ref "D44") (pin "C") (pinfunction "C_C") (pintype "passive"))
      (node (ref "D45") (pin "C") (pinfunction "C_C") (pintype "passive"))
      (node (ref "K11") (pin "1") (pinfunction "+_1") (pintype "passive"))
      (node (ref "K11") (pin "7") (pinfunction "O_7") (pintype "passive"))
      (node (ref "K13") (pin "1") (pinfunction "+_1") (pintype "passive"))
      (node (ref "K14") (pin "1") (pinfunction "+_1") (pintype "passive"))
      (node (ref "K15") (pin "1") (pinfunction "+_1") (pintype "passive"))
      (node (ref "K15") (pin "7") (pinfunction "O_7") (pintype "passive"))
      (node (ref "K17") (pin "1") (pinfunction "+_1") (pintype "passive"))
      (node (ref "K17") (pin "7") (pinfunction "O_7") (pintype "passive"))
      (node (ref "K19") (pin "1") (pinfunction "+_1") (pintype "passive"))
      (node (ref "K5") (pin "1") (pinfunction "+_1") (pintype "passive"))
      (node (ref "K5") (pin "7") (pinfunction "O_7") (pintype "passive"))
      (node (ref "K7") (pin "1") (pinfunction "+_1") (pintype "passive"))
      (node (ref "K7") (pin "7") (pinfunction "O_7") (pintype "passive"))
      (node (ref "K9") (pin "1") (pinfunction "+_1") (pintype "passive"))
      (node (ref "K9") (pin "7") (pinfunction "O_7") (pintype "passive"))
    )
    (net (code "11") (name "/LATCH_RESULT") (class "Default")
      (node (ref "D36") (pin "C") (pinfunction "C_C") (pintype "passive"))
      (node (ref "D37") (pin "C") (pinfunction "C_C") (pintype "passive"))
      (node (ref "K90") (pin "3") (pinfunction "P_3") (pintype "passive"))
      (node (ref "K91") (pin "3") (pinfunction "P_3") (pintype "passive"))
      (node (ref "K92") (pin "3") (pinfunction "P_3") (pintype "passive"))
      (node (ref "K93") (pin "3") (pinfunction "P_3") (pintype "passive"))
      (node (ref "K94") (pin "3") (pinfunction "P_3") (pintype "passive"))
    )
    (net (code "12") (name "/OPERATION") (class "Default")
      (node (ref "D34") (pin "A") (pinfunction "A_A") (pintype "passive"))
      (node (ref "D50") (pin "A") (pinfunction "A_A") (pintype "passive"))
      (node (ref "K64") (pin "1") (pinfunction "+_1") (pintype "passive"))
      (node (ref "K69") (pin "1") (pinfunction "+_1") (pintype "passive"))
    )
    (net (code "13") (name "/RAMRD{slash}WR-") (class "Default")
      (node (ref "D46") (pin "C") (pinfunction "C_C") (pintype "passive"))
      (node (ref "D47") (pin "C") (pinfunction "C_C") (pintype "passive"))
      (node (ref "D48") (pin "C") (pinfunction "C_C") (pintype "passive"))
      (node (ref "D49") (pin "C") (pinfunction "C_C") (pintype "passive"))
      (node (ref "D50") (pin "C") (pinfunction "C_C") (pintype "passive"))
      (node (ref "K21") (pin "3") (pinfunction "P_3") (pintype "passive"))
      (node (ref "K95") (pin "1") (pinfunction "+_1") (pintype "passive"))
      (node (ref "K96") (pin "1") (pinfunction "+_1") (pintype "passive"))
    )
    (net (code "14") (name "/VCC") (class "Default")
      (node (ref "C2") (pin "+") (pinfunction "+_+") (pintype "passive"))
      (node (ref "C3") (pin "+") (pinfunction "+_+") (pintype "passive"))
      (node (ref "C4") (pin "+") (pinfunction "+_+") (pintype "passive"))
      (node (ref "C5") (pin "+") (pinfunction "+_+") (pintype "passive"))
      (node (ref "K100") (pin "2") (pinfunction "O_2") (pintype "passive"))
      (node (ref "K65") (pin "2") (pinfunction "O_2") (pintype "passive"))
      (node (ref "K67") (pin "2") (pinfunction "O_2") (pintype "passive"))
      (node (ref "K70") (pin "2") (pinfunction "O_2") (pintype "passive"))
      (node (ref "K72") (pin "2") (pinfunction "O_2") (pintype "passive"))
      (node (ref "K73") (pin "3") (pinfunction "P_3") (pintype "passive"))
      (node (ref "K74") (pin "5") (pinfunction "S_5") (pintype "passive"))
      (node (ref "K75") (pin "5") (pinfunction "S_5") (pintype "passive"))
      (node (ref "K76") (pin "5") (pinfunction "S_5") (pintype "passive"))
      (node (ref "K77") (pin "5") (pinfunction "S_5") (pintype "passive"))
      (node (ref "K78") (pin "5") (pinfunction "S_5") (pintype "passive"))
      (node (ref "K79") (pin "5") (pinfunction "S_5") (pintype "passive"))
      (node (ref "K80") (pin "5") (pinfunction "S_5") (pintype "passive"))
      (node (ref "K81") (pin "5") (pinfunction "S_5") (pintype "passive"))
      (node (ref "K82") (pin "2") (pinfunction "O_2") (pintype "passive"))
      (node (ref "K85") (pin "5") (pinfunction "S_5") (pintype "passive"))
      (node (ref "K86") (pin "5") (pinfunction "S_5") (pintype "passive"))
      (node (ref "K87") (pin "5") (pinfunction "S_5") (pintype "passive"))
      (node (ref "K88") (pin "5") (pinfunction "S_5") (pintype "passive"))
      (node (ref "K89") (pin "5") (pinfunction "S_5") (pintype "passive"))
      (node (ref "K90") (pin "5") (pinfunction "S_5") (pintype "passive"))
      (node (ref "K91") (pin "5") (pinfunction "S_5") (pintype "passive"))
      (node (ref "K92") (pin "5") (pinfunction "S_5") (pintype "passive"))
      (node (ref "K93") (pin "5") (pinfunction "S_5") (pintype "passive"))
      (node (ref "K94") (pin "5") (pinfunction "S_5") (pintype "passive"))
      (node (ref "K97") (pin "2") (pinfunction "O_2") (pintype "passive"))
      (node (ref "K98") (pin "2") (pinfunction "O_2") (pintype "passive"))
      (node (ref "K99") (pin "2") (pinfunction "O_2") (pintype "passive"))
      (node (ref "X1") (pin "2") (pinfunction "K_2") (pintype "passive"))
    )
    (net (code "15") (name "/ZERO") (class "Default")
      (node (ref "D3") (pin "C") (pinfunction "C_C") (pintype "passive"))
      (node (ref "D4") (pin "C") (pinfunction "C_C") (pintype "passive"))
      (node (ref "D45") (pin "A") (pinfunction "A_A") (pintype "passive"))
      (node (ref "D5") (pin "C") (pinfunction "C_C") (pintype "passive"))
      (node (ref "D6") (pin "C") (pinfunction "C_C") (pintype "passive"))
    )
    (net (code "16") (name "Net-(K1A-+)") (class "Default")
      (node (ref "C1") (pin "+") (pinfunction "+_+") (pintype "passive"))
      (node (ref "K1") (pin "1") (pinfunction "+_1") (pintype "passive"))
      (node (ref "R1") (pin "1") (pinfunction "1_1") (pintype "passive"))
    )
    (net (code "17") (name "Net-(K1C-P)") (class "Default")
      (node (ref "K1") (pin "6") (pinfunction "P_6") (pintype "passive"))
      (node (ref "K2") (pin "3") (pinfunction "P_3") (pintype "passive"))
    )
    (net (code "18") (name "Net-(K1C-S)") (class "Default")
      (node (ref "K1") (pin "5") (pinfunction "S_5") (pintype "passive"))
      (node (ref "K2") (pin "6") (pinfunction "P_6") (pintype "passive"))
    )
    (net (code "19") (name "Net-(K2A--)") (class "Default")
      (node (ref "K2") (pin "4") (pinfunction "S_4") (pintype "passive"))
      (node (ref "K2") (pin "8") (pinfunction "-_8") (pintype "passive"))
      (node (ref "K3") (pin "6") (pinfunction "P_6") (pintype "passive"))
    )
    (net (code "20") (name "Net-(K3B-P)") (class "Default")
      (node (ref "K3") (pin "3") (pinfunction "P_3") (pintype "passive"))
      (node (ref "K5") (pin "6") (pinfunction "P_6") (pintype "passive"))
    )
    (net (code "21") (name "Net-(K3B-S)") (class "Default")
      (node (ref "K3") (pin "4") (pinfunction "S_4") (pintype "passive"))
      (node (ref "K5") (pin "3") (pinfunction "P_3") (pintype "passive"))
    )
    (net (code "22") (name "Net-(K5A--)") (class "Default")
      (node (ref "K5") (pin "4") (pinfunction "S_4") (pintype "passive"))
      (node (ref "K5") (pin "8") (pinfunction "-_8") (pintype "passive"))
      (node (ref "K6") (pin "6") (pinfunction "P_6") (pintype "passive"))
    )
    (net (code "23") (name "Net-(K6B-P)") (class "Default")
      (node (ref "K6") (pin "3") (pinfunction "P_3") (pintype "passive"))
      (node (ref "K7") (pin "6") (pinfunction "P_6") (pintype "passive"))
    )
    (net (code "24") (name "Net-(K6B-S)") (class "Default")
      (node (ref "K6") (pin "4") (pinfunction "S_4") (pintype "passive"))
      (node (ref "K7") (pin "3") (pinfunction "P_3") (pintype "passive"))
    )
    (net (code "25") (name "Net-(K7A--)") (class "Default")
      (node (ref "K7") (pin "4") (pinfunction "S_4") (pintype "passive"))
      (node (ref "K7") (pin "8") (pinfunction "-_8") (pintype "passive"))
      (node (ref "K8") (pin "6") (pinfunction "P_6") (pintype "passive"))
    )
    (net (code "26") (name "Net-(K8B-P)") (class "Default")
      (node (ref "K8") (pin "3") (pinfunction "P_3") (pintype "passive"))
      (node (ref "K9") (pin "6") (pinfunction "P_6") (pintype "passive"))
    )
    (net (code "27") (name "Net-(K8B-S)") (class "Default")
      (node (ref "K8") (pin "4") (pinfunction "S_4") (pintype "passive"))
      (node (ref "K9") (pin "3") (pinfunction "P_3") (pintype "passive"))
    )
    (net (code "28") (name "Net-(K10A-+)") (class "Default")
      (node (ref "K10") (pin "1") (pinfunction "+_1") (pintype "passive"))
      (node (ref "K10") (pin "5") (pinfunction "S_5") (pintype "passive"))
      (node (ref "K14") (pin "3") (pinfunction "P_3") (pintype "passive"))
      (node (ref "K9") (pin "2") (pinfunction "O_2") (pintype "passive"))
      (node (ref "R6") (pin "2") (pinfunction "2_2") (pintype "passive"))
    )
    (net (code "29") (name "Net-(K10B-P)") (class "Default")
      (node (ref "K10") (pin "3") (pinfunction "P_3") (pintype "passive"))
      (node (ref "K11") (pin "6") (pinfunction "P_6") (pintype "passive"))
    )
    (net (code "30") (name "Net-(K10B-S)") (class "Default")
      (node (ref "K10") (pin "4") (pinfunction "S_4") (pintype "passive"))
      (node (ref "K11") (pin "3") (pinfunction "P_3") (pintype "passive"))
    )
    (net (code "31") (name "Net-(K10C-P)") (class "Default")
      (node (ref "K10") (pin "6") (pinfunction "P_6") (pintype "passive"))
      (node (ref "K9") (pin "4") (pinfunction "S_4") (pintype "passive"))
      (node (ref "K9") (pin "8") (pinfunction "-_8") (pintype "passive"))
    )
    (net (code "32") (name "Net-(K11A--)") (class "Default")
      (node (ref "K11") (pin "4") (pinfunction "S_4") (pintype "passive"))
      (node (ref "K11") (pin "8") (pinfunction "-_8") (pintype "passive"))
      (node (ref "K12") (pin "6") (pinfunction "P_6") (pintype "passive"))
    )
    (net (code "33") (name "Net-(K11B-O)") (class "Default")
      (node (ref "K11") (pin "2") (pinfunction "O_2") (pintype "passive"))
      (node (ref "K12") (pin "1") (pinfunction "+_1") (pintype "passive"))
      (node (ref "K12") (pin "5") (pinfunction "S_5") (pintype "passive"))
      (node (ref "K14") (pin "6") (pinfunction "P_6") (pintype "passive"))
      (node (ref "R7") (pin "2") (pinfunction "2_2") (pintype "passive"))
    )
    (net (code "34") (name "Net-(K12B-P)") (class "Default")
      (node (ref "K12") (pin "3") (pinfunction "P_3") (pintype "passive"))
      (node (ref "K15") (pin "6") (pinfunction "P_6") (pintype "passive"))
    )
    (net (code "35") (name "Net-(K12B-S)") (class "Default")
      (node (ref "K12") (pin "4") (pinfunction "S_4") (pintype "passive"))
      (node (ref "K15") (pin "3") (pinfunction "P_3") (pintype "passive"))
    )
    (net (code "36") (name "Net-(K13B-O)") (class "Default")
      (node (ref "K13") (pin "2") (pinfunction "O_2") (pintype "passive"))
      (node (ref "K53") (pin "1") (pinfunction "+_1") (pintype "passive"))
    )
    (net (code "37") (name "Net-(K13B-P)") (class "Default")
      (node (ref "K13") (pin "3") (pinfunction "P_3") (pintype "passive"))
      (node (ref "K5") (pin "2") (pinfunction "O_2") (pintype "passive"))
      (node (ref "K6") (pin "1") (pinfunction "+_1") (pintype "passive"))
      (node (ref "K6") (pin "5") (pinfunction "S_5") (pintype "passive"))
      (node (ref "R4") (pin "2") (pinfunction "2_2") (pintype "passive"))
    )
    (net (code "38") (name "Net-(K13B-S)") (class "Default")
      (node (ref "K13") (pin "4") (pinfunction "S_4") (pintype "passive"))
      (node (ref "K21") (pin "8") (pinfunction "-_8") (pintype "passive"))
      (node (ref "K74") (pin "6") (pinfunction "P_6") (pintype "passive"))
      (node (ref "K83") (pin "5") (pinfunction "S_5") (pintype "passive"))
      (node (ref "K95") (pin "3") (pinfunction "P_3") (pintype "passive"))
    )
    (net (code "39") (name "Net-(K13C-O)") (class "Default")
      (node (ref "K13") (pin "7") (pinfunction "O_7") (pintype "passive"))
      (node (ref "K54") (pin "1") (pinfunction "+_1") (pintype "passive"))
      (node (ref "K56") (pin "1") (pinfunction "+_1") (pintype "passive"))
    )
    (net (code "40") (name "Net-(K13C-P)") (class "Default")
      (node (ref "K13") (pin "6") (pinfunction "P_6") (pintype "passive"))
      (node (ref "K7") (pin "2") (pinfunction "O_2") (pintype "passive"))
      (node (ref "K8") (pin "1") (pinfunction "+_1") (pintype "passive"))
      (node (ref "K8") (pin "5") (pinfunction "S_5") (pintype "passive"))
      (node (ref "R5") (pin "2") (pinfunction "2_2") (pintype "passive"))
    )
    (net (code "41") (name "Net-(K13C-S)") (class "Default")
      (node (ref "K13") (pin "5") (pinfunction "S_5") (pintype "passive"))
      (node (ref "K22") (pin "8") (pinfunction "-_8") (pintype "passive"))
      (node (ref "K23") (pin "8") (pinfunction "-_8") (pintype "passive"))
      (node (ref "K75") (pin "6") (pinfunction "P_6") (pintype "passive"))
      (node (ref "K83") (pin "4") (pinfunction "S_4") (pintype "passive"))
      (node (ref "K95") (pin "6") (pinfunction "P_6") (pintype "passive"))
    )
    (net (code "42") (name "Net-(K14B-O)") (class "Default")
      (node (ref "K14") (pin "2") (pinfunction "O_2") (pintype "passive"))
      (node (ref "K49") (pin "1") (pinfunction "+_1") (pintype "passive"))
      (node (ref "K52") (pin "1") (pinfunction "+_1") (pintype "passive"))
      (node (ref "K57") (pin "1") (pinfunction "+_1") (pintype "passive"))
      (node (ref "K58") (pin "1") (pinfunction "+_1") (pintype "passive"))
    )
    (net (code "43") (name "Net-(K14B-S)") (class "Default")
      (node (ref "D2") (pin "A") (pinfunction "A_A") (pintype "passive"))
      (node (ref "K14") (pin "4") (pinfunction "S_4") (pintype "passive"))
      (node (ref "K76") (pin "6") (pinfunction "P_6") (pintype "passive"))
      (node (ref "K84") (pin "5") (pinfunction "S_5") (pintype "passive"))
      (node (ref "K96") (pin "3") (pinfunction "P_3") (pintype "passive"))
    )
    (net (code "44") (name "Net-(K14C-O)") (class "Default")
      (node (ref "K14") (pin "7") (pinfunction "O_7") (pintype "passive"))
      (node (ref "K47") (pin "1") (pinfunction "+_1") (pintype "passive"))
      (node (ref "K48") (pin "1") (pinfunction "+_1") (pintype "passive"))
      (node (ref "K50") (pin "1") (pinfunction "+_1") (pintype "passive"))
      (node (ref "K51") (pin "1") (pinfunction "+_1") (pintype "passive"))
      (node (ref "K59") (pin "1") (pinfunction "+_1") (pintype "passive"))
      (node (ref "K60") (pin "1") (pinfunction "+_1") (pintype "passive"))
      (node (ref "K61") (pin "1") (pinfunction "+_1") (pintype "passive"))
      (node (ref "K62") (pin "1") (pinfunction "+_1") (pintype "passive"))
    )
    (net (code "45") (name "Net-(K14C-S)") (class "Default")
      (node (ref "D1") (pin "A") (pinfunction "A_A") (pintype "passive"))
      (node (ref "K14") (pin "5") (pinfunction "S_5") (pintype "passive"))
      (node (ref "K77") (pin "6") (pinfunction "P_6") (pintype "passive"))
      (node (ref "K84") (pin "4") (pinfunction "S_4") (pintype "passive"))
      (node (ref "K96") (pin "6") (pinfunction "P_6") (pintype "passive"))
    )
    (net (code "46") (name "Net-(K15A--)") (class "Default")
      (node (ref "K15") (pin "4") (pinfunction "S_4") (pintype "passive"))
      (node (ref "K15") (pin "8") (pinfunction "-_8") (pintype "passive"))
      (node (ref "K16") (pin "6") (pinfunction "P_6") (pintype "passive"))
    )
    (net (code "47") (name "Net-(K15B-O)") (class "Default")
      (node (ref "K15") (pin "2") (pinfunction "O_2") (pintype "passive"))
      (node (ref "K16") (pin "1") (pinfunction "+_1") (pintype "passive"))
      (node (ref "K16") (pin "5") (pinfunction "S_5") (pintype "passive"))
      (node (ref "K19") (pin "3") (pinfunction "P_3") (pintype "passive"))
      (node (ref "R8") (pin "2") (pinfunction "2_2") (pintype "passive"))
    )
    (net (code "48") (name "Net-(K16B-P)") (class "Default")
      (node (ref "K16") (pin "3") (pinfunction "P_3") (pintype "passive"))
      (node (ref "K17") (pin "6") (pinfunction "P_6") (pintype "passive"))
    )
    (net (code "49") (name "Net-(K16B-S)") (class "Default")
      (node (ref "K16") (pin "4") (pinfunction "S_4") (pintype "passive"))
      (node (ref "K17") (pin "3") (pinfunction "P_3") (pintype "passive"))
    )
    (net (code "50") (name "Net-(K17A--)") (class "Default")
      (node (ref "K17") (pin "4") (pinfunction "S_4") (pintype "passive"))
      (node (ref "K17") (pin "8") (pinfunction "-_8") (pintype "passive"))
      (node (ref "K18") (pin "6") (pinfunction "P_6") (pintype "passive"))
    )
    (net (code "51") (name "Net-(K17B-O)") (class "Default")
      (node (ref "K17") (pin "2") (pinfunction "O_2") (pintype "passive"))
      (node (ref "K18") (pin "1") (pinfunction "+_1") (pintype "passive"))
      (node (ref "K18") (pin "5") (pinfunction "S_5") (pintype "passive"))
      (node (ref "K19") (pin "6") (pinfunction "P_6") (pintype "passive"))
      (node (ref "R9") (pin "2") (pinfunction "2_2") (pintype "passive"))
    )
    (net (code "52") (name "Net-(K19B-O)") (class "Default")
      (node (ref "K19") (pin "2") (pinfunction "O_2") (pintype "passive"))
      (node (ref "K55") (pin "1") (pinfunction "+_1") (pintype "passive"))
    )
    (net (code "53") (name "Net-(K19B-S)") (class "Default")
      (node (ref "K19") (pin "4") (pinfunction "S_4") (pintype "passive"))
      (node (ref "K78") (pin "6") (pinfunction "P_6") (pintype "passive"))
    )
    (net (code "54") (name "Net-(K19C-O)") (class "Default")
      (node (ref "K19") (pin "7") (pinfunction "O_7") (pintype "passive"))
      (node (ref "K73") (pin "1") (pinfunction "+_1") (pintype "passive"))
    )
    (net (code "55") (name "Net-(K19C-S)") (class "Default")
      (node (ref "K19") (pin "5") (pinfunction "S_5") (pintype "passive"))
      (node (ref "K79") (pin "6") (pinfunction "P_6") (pintype "passive"))
    )
    (net (code "56") (name "Net-(K20A-+)") (class "Default")
      (node (ref "K20") (pin "1") (pinfunction "+_1") (pintype "passive"))
      (node (ref "K20") (pin "3") (pinfunction "P_3") (pintype "passive"))
      (node (ref "K24") (pin "5") (pinfunction "S_5") (pintype "passive"))
      (node (ref "R14") (pin "2") (pinfunction "2_2") (pintype "passive"))
    )
    (net (code "57") (name "Net-(K20A--)") (class "Default")
      (node (ref "K20") (pin "8") (pinfunction "-_8") (pintype "passive"))
      (node (ref "K24") (pin "8") (pinfunction "-_8") (pintype "passive"))
      (node (ref "K25") (pin "8") (pinfunction "-_8") (pintype "passive"))
      (node (ref "K32") (pin "8") (pinfunction "-_8") (pintype "passive"))
      (node (ref "K33") (pin "8") (pinfunction "-_8") (pintype "passive"))
      (node (ref "K34") (pin "8") (pinfunction "-_8") (pintype "passive"))
      (node (ref "LED13") (pin "K") (pinfunction "C_K") (pintype "passive"))
      (node (ref "LED14") (pin "K") (pinfunction "C_K") (pintype "passive"))
      (node (ref "LED15") (pin "K") (pinfunction "C_K") (pintype "passive"))
      (node (ref "LED16") (pin "K") (pinfunction "C_K") (pintype "passive"))
    )
    (net (code "58") (name "Net-(K20B-S)") (class "Default")
      (node (ref "K20") (pin "4") (pinfunction "S_4") (pintype "passive"))
      (node (ref "K22") (pin "5") (pinfunction "S_5") (pintype "passive"))
      (node (ref "K24") (pin "1") (pinfunction "+_1") (pintype "passive"))
      (node (ref "K25") (pin "4") (pinfunction "S_4") (pintype "passive"))
      (node (ref "K32") (pin "4") (pinfunction "S_4") (pintype "passive"))
      (node (ref "K33") (pin "1") (pinfunction "+_1") (pintype "passive"))
      (node (ref "K34") (pin "4") (pinfunction "S_4") (pintype "passive"))
    )
    (net (code "59") (name "Net-(K20C-P)") (class "Default")
      (node (ref "K20") (pin "6") (pinfunction "P_6") (pintype "passive"))
      (node (ref "K23") (pin "5") (pinfunction "S_5") (pintype "passive"))
      (node (ref "K25") (pin "6") (pinfunction "P_6") (pintype "passive"))
      (node (ref "K32") (pin "6") (pinfunction "P_6") (pintype "passive"))
      (node (ref "K34") (pin "6") (pinfunction "P_6") (pintype "passive"))
    )
    (net (code "60") (name "Net-(K20C-S)") (class "Default")
      (node (ref "K20") (pin "5") (pinfunction "S_5") (pintype "passive"))
      (node (ref "K24") (pin "7") (pinfunction "O_7") (pintype "passive"))
    )
    (net (code "61") (name "Net-(K21A-+)") (class "Default")
      (node (ref "K21") (pin "1") (pinfunction "+_1") (pintype "passive"))
      (node (ref "K22") (pin "1") (pinfunction "+_1") (pintype "passive"))
      (node (ref "K23") (pin "1") (pinfunction "+_1") (pintype "passive"))
    )
    (net (code "62") (name "Net-(K21B-O)") (class "Default")
      (node (ref "K21") (pin "2") (pinfunction "O_2") (pintype "passive"))
      (node (ref "K22") (pin "6") (pinfunction "P_6") (pintype "passive"))
    )
    (net (code "63") (name "Net-(K21B-S)") (class "Default")
      (node (ref "K21") (pin "4") (pinfunction "S_4") (pintype "passive"))
      (node (ref "K22") (pin "3") (pinfunction "P_3") (pintype "passive"))
    )
    (net (code "64") (name "Net-(K21C-O)") (class "Default")
      (node (ref "K21") (pin "7") (pinfunction "O_7") (pintype "passive"))
      (node (ref "K23") (pin "6") (pinfunction "P_6") (pintype "passive"))
    )
    (net (code "65") (name "Net-(K21C-P)") (class "Default")
      (node (ref "K21") (pin "6") (pinfunction "P_6") (pintype "passive"))
      (node (ref "K82") (pin "3") (pinfunction "P_3") (pintype "passive"))
    )
    (net (code "66") (name "Net-(K21C-S)") (class "Default")
      (node (ref "K21") (pin "5") (pinfunction "S_5") (pintype "passive"))
      (node (ref "K23") (pin "3") (pinfunction "P_3") (pintype "passive"))
    )
    (net (code "67") (name "Net-(K22B-O)") (class "Default")
      (node (ref "K22") (pin "2") (pinfunction "O_2") (pintype "passive"))
      (node (ref "K35") (pin "4") (pinfunction "S_4") (pintype "passive"))
      (node (ref "K36") (pin "1") (pinfunction "+_1") (pintype "passive"))
      (node (ref "K37") (pin "4") (pinfunction "S_4") (pintype "passive"))
      (node (ref "K38") (pin "4") (pinfunction "S_4") (pintype "passive"))
      (node (ref "K39") (pin "1") (pinfunction "+_1") (pintype "passive"))
      (node (ref "K40") (pin "4") (pinfunction "S_4") (pintype "passive"))
    )
    (net (code "68") (name "Net-(K22B-S)") (class "Default")
      (node (ref "K22") (pin "4") (pinfunction "S_4") (pintype "passive"))
      (node (ref "K41") (pin "4") (pinfunction "S_4") (pintype "passive"))
      (node (ref "K42") (pin "1") (pinfunction "+_1") (pintype "passive"))
      (node (ref "K43") (pin "4") (pinfunction "S_4") (pintype "passive"))
      (node (ref "K44") (pin "4") (pinfunction "S_4") (pintype "passive"))
      (node (ref "K45") (pin "1") (pinfunction "+_1") (pintype "passive"))
      (node (ref "K46") (pin "4") (pinfunction "S_4") (pintype "passive"))
    )
    (net (code "69") (name "Net-(K22C-O)") (class "Default")
      (node (ref "K22") (pin "7") (pinfunction "O_7") (pintype "passive"))
      (node (ref "K26") (pin "4") (pinfunction "S_4") (pintype "passive"))
      (node (ref "K27") (pin "1") (pinfunction "+_1") (pintype "passive"))
      (node (ref "K28") (pin "4") (pinfunction "S_4") (pintype "passive"))
      (node (ref "K29") (pin "4") (pinfunction "S_4") (pintype "passive"))
      (node (ref "K30") (pin "1") (pinfunction "+_1") (pintype "passive"))
      (node (ref "K31") (pin "4") (pinfunction "S_4") (pintype "passive"))
    )
    (net (code "70") (name "Net-(K23B-O)") (class "Default")
      (node (ref "K23") (pin "2") (pinfunction "O_2") (pintype "passive"))
      (node (ref "K35") (pin "6") (pinfunction "P_6") (pintype "passive"))
      (node (ref "K37") (pin "6") (pinfunction "P_6") (pintype "passive"))
      (node (ref "K38") (pin "6") (pinfunction "P_6") (pintype "passive"))
      (node (ref "K40") (pin "6") (pinfunction "P_6") (pintype "passive"))
    )
    (net (code "71") (name "Net-(K23B-S)") (class "Default")
      (node (ref "K23") (pin "4") (pinfunction "S_4") (pintype "passive"))
      (node (ref "K41") (pin "6") (pinfunction "P_6") (pintype "passive"))
      (node (ref "K43") (pin "6") (pinfunction "P_6") (pintype "passive"))
      (node (ref "K44") (pin "6") (pinfunction "P_6") (pintype "passive"))
      (node (ref "K46") (pin "6") (pinfunction "P_6") (pintype "passive"))
    )
    (net (code "72") (name "Net-(K23C-O)") (class "Default")
      (node (ref "K23") (pin "7") (pinfunction "O_7") (pintype "passive"))
      (node (ref "K26") (pin "6") (pinfunction "P_6") (pintype "passive"))
      (node (ref "K28") (pin "6") (pinfunction "P_6") (pintype "passive"))
      (node (ref "K29") (pin "6") (pinfunction "P_6") (pintype "passive"))
      (node (ref "K31") (pin "6") (pinfunction "P_6") (pintype "passive"))
    )
    (net (code "73") (name "Net-(K24B-O)") (class "Default")
      (node (ref "K24") (pin "2") (pinfunction "O_2") (pintype "passive"))
      (node (ref "K25") (pin "5") (pinfunction "S_5") (pintype "passive"))
    )
    (net (code "74") (name "Net-(K24B-P)") (class "Default")
      (node (ref "K24") (pin "3") (pinfunction "P_3") (pintype "passive"))
      (node (ref "K27") (pin "3") (pinfunction "P_3") (pintype "passive"))
      (node (ref "K36") (pin "3") (pinfunction "P_3") (pintype "passive"))
      (node (ref "K42") (pin "3") (pinfunction "P_3") (pintype "passive"))
      (node (ref "K83") (pin "7") (pinfunction "O_7") (pintype "passive"))
      (node (ref "K96") (pin "7") (pinfunction "O_7") (pintype "passive"))
    )
    (net (code "75") (name "Net-(K24B-S)") (class "Default")
      (node (ref "K24") (pin "4") (pinfunction "S_4") (pintype "passive"))
      (node (ref "K25") (pin "1") (pinfunction "+_1") (pintype "passive"))
      (node (ref "K25") (pin "3") (pinfunction "P_3") (pintype "passive"))
      (node (ref "R15") (pin "2") (pinfunction "2_2") (pintype "passive"))
    )
    (net (code "76") (name "Net-(K24C-P)") (class "Default")
      (node (ref "K24") (pin "6") (pinfunction "P_6") (pintype "passive"))
      (node (ref "K27") (pin "6") (pinfunction "P_6") (pintype "passive"))
      (node (ref "K36") (pin "6") (pinfunction "P_6") (pintype "passive"))
      (node (ref "K42") (pin "6") (pinfunction "P_6") (pintype "passive"))
      (node (ref "K83") (pin "2") (pinfunction "O_2") (pintype "passive"))
      (node (ref "K96") (pin "2") (pinfunction "O_2") (pintype "passive"))
    )
    (net (code "77") (name "Net-(K26A-+)") (class "Default")
      (node (ref "K26") (pin "1") (pinfunction "+_1") (pintype "passive"))
      (node (ref "K26") (pin "3") (pinfunction "P_3") (pintype "passive"))
      (node (ref "K27") (pin "5") (pinfunction "S_5") (pintype "passive"))
      (node (ref "R10") (pin "2") (pinfunction "2_2") (pintype "passive"))
    )
    (net (code "78") (name "Net-(K26A--)") (class "Default")
      (node (ref "K26") (pin "8") (pinfunction "-_8") (pintype "passive"))
      (node (ref "K27") (pin "8") (pinfunction "-_8") (pintype "passive"))
      (node (ref "K28") (pin "8") (pinfunction "-_8") (pintype "passive"))
      (node (ref "K29") (pin "8") (pinfunction "-_8") (pintype "passive"))
      (node (ref "K30") (pin "8") (pinfunction "-_8") (pintype "passive"))
      (node (ref "K31") (pin "8") (pinfunction "-_8") (pintype "passive"))
      (node (ref "LED10") (pin "K") (pinfunction "C_K") (pintype "passive"))
      (node (ref "LED11") (pin "K") (pinfunction "C_K") (pintype "passive"))
      (node (ref "LED12") (pin "K") (pinfunction "C_K") (pintype "passive"))
      (node (ref "LED9") (pin "K") (pinfunction "C_K") (pintype "passive"))
    )
    (net (code "79") (name "Net-(K26C-S)") (class "Default")
      (node (ref "K26") (pin "5") (pinfunction "S_5") (pintype "passive"))
      (node (ref "K27") (pin "7") (pinfunction "O_7") (pintype "passive"))
    )
    (net (code "80") (name "Net-(K27B-O)") (class "Default")
      (node (ref "K27") (pin "2") (pinfunction "O_2") (pintype "passive"))
      (node (ref "K28") (pin "5") (pinfunction "S_5") (pintype "passive"))
    )
    (net (code "81") (name "Net-(K27B-S)") (class "Default")
      (node (ref "K27") (pin "4") (pinfunction "S_4") (pintype "passive"))
      (node (ref "K28") (pin "1") (pinfunction "+_1") (pintype "passive"))
      (node (ref "K28") (pin "3") (pinfunction "P_3") (pintype "passive"))
      (node (ref "R11") (pin "2") (pinfunction "2_2") (pintype "passive"))
    )
    (net (code "82") (name "Net-(K29A-+)") (class "Default")
      (node (ref "K29") (pin "1") (pinfunction "+_1") (pintype "passive"))
      (node (ref "K29") (pin "3") (pinfunction "P_3") (pintype "passive"))
      (node (ref "K30") (pin "5") (pinfunction "S_5") (pintype "passive"))
      (node (ref "R12") (pin "2") (pinfunction "2_2") (pintype "passive"))
    )
    (net (code "83") (name "Net-(K29C-S)") (class "Default")
      (node (ref "K29") (pin "5") (pinfunction "S_5") (pintype "passive"))
      (node (ref "K30") (pin "7") (pinfunction "O_7") (pintype "passive"))
    )
    (net (code "84") (name "Net-(K30B-O)") (class "Default")
      (node (ref "K30") (pin "2") (pinfunction "O_2") (pintype "passive"))
      (node (ref "K31") (pin "5") (pinfunction "S_5") (pintype "passive"))
    )
    (net (code "85") (name "Net-(K30B-P)") (class "Default")
      (node (ref "K30") (pin "3") (pinfunction "P_3") (pintype "passive"))
      (node (ref "K33") (pin "3") (pinfunction "P_3") (pintype "passive"))
      (node (ref "K39") (pin "3") (pinfunction "P_3") (pintype "passive"))
      (node (ref "K45") (pin "3") (pinfunction "P_3") (pintype "passive"))
      (node (ref "K84") (pin "7") (pinfunction "O_7") (pintype "passive"))
      (node (ref "K95") (pin "7") (pinfunction "O_7") (pintype "passive"))
    )
    (net (code "86") (name "Net-(K30B-S)") (class "Default")
      (node (ref "K30") (pin "4") (pinfunction "S_4") (pintype "passive"))
      (node (ref "K31") (pin "1") (pinfunction "+_1") (pintype "passive"))
      (node (ref "K31") (pin "3") (pinfunction "P_3") (pintype "passive"))
      (node (ref "R13") (pin "2") (pinfunction "2_2") (pintype "passive"))
    )
    (net (code "87") (name "Net-(K30C-P)") (class "Default")
      (node (ref "K30") (pin "6") (pinfunction "P_6") (pintype "passive"))
      (node (ref "K33") (pin "6") (pinfunction "P_6") (pintype "passive"))
      (node (ref "K39") (pin "6") (pinfunction "P_6") (pintype "passive"))
      (node (ref "K45") (pin "6") (pinfunction "P_6") (pintype "passive"))
      (node (ref "K84") (pin "2") (pinfunction "O_2") (pintype "passive"))
      (node (ref "K95") (pin "2") (pinfunction "O_2") (pintype "passive"))
    )
    (net (code "88") (name "Net-(K32A-+)") (class "Default")
      (node (ref "K32") (pin "1") (pinfunction "+_1") (pintype "passive"))
      (node (ref "K32") (pin "3") (pinfunction "P_3") (pintype "passive"))
      (node (ref "K33") (pin "5") (pinfunction "S_5") (pintype "passive"))
      (node (ref "R16") (pin "2") (pinfunction "2_2") (pintype "passive"))
    )
    (net (code "89") (name "Net-(K32C-S)") (class "Default")
      (node (ref "K32") (pin "5") (pinfunction "S_5") (pintype "passive"))
      (node (ref "K33") (pin "7") (pinfunction "O_7") (pintype "passive"))
    )
    (net (code "90") (name "Net-(K33B-O)") (class "Default")
      (node (ref "K33") (pin "2") (pinfunction "O_2") (pintype "passive"))
      (node (ref "K34") (pin "5") (pinfunction "S_5") (pintype "passive"))
    )
    (net (code "91") (name "Net-(K33B-S)") (class "Default")
      (node (ref "K33") (pin "4") (pinfunction "S_4") (pintype "passive"))
      (node (ref "K34") (pin "1") (pinfunction "+_1") (pintype "passive"))
      (node (ref "K34") (pin "3") (pinfunction "P_3") (pintype "passive"))
      (node (ref "R17") (pin "2") (pinfunction "2_2") (pintype "passive"))
    )
    (net (code "92") (name "Net-(K35A-+)") (class "Default")
      (node (ref "K35") (pin "1") (pinfunction "+_1") (pintype "passive"))
      (node (ref "K35") (pin "3") (pinfunction "P_3") (pintype "passive"))
      (node (ref "K36") (pin "5") (pinfunction "S_5") (pintype "passive"))
      (node (ref "R18") (pin "2") (pinfunction "2_2") (pintype "passive"))
    )
    (net (code "93") (name "Net-(K35A--)") (class "Default")
      (node (ref "K35") (pin "8") (pinfunction "-_8") (pintype "passive"))
      (node (ref "K36") (pin "8") (pinfunction "-_8") (pintype "passive"))
      (node (ref "K37") (pin "8") (pinfunction "-_8") (pintype "passive"))
      (node (ref "K38") (pin "8") (pinfunction "-_8") (pintype "passive"))
      (node (ref "K39") (pin "8") (pinfunction "-_8") (pintype "passive"))
      (node (ref "K40") (pin "8") (pinfunction "-_8") (pintype "passive"))
      (node (ref "LED17") (pin "K") (pinfunction "C_K") (pintype "passive"))
      (node (ref "LED18") (pin "K") (pinfunction "C_K") (pintype "passive"))
      (node (ref "LED19") (pin "K") (pinfunction "C_K") (pintype "passive"))
      (node (ref "LED20") (pin "K") (pinfunction "C_K") (pintype "passive"))
    )
    (net (code "94") (name "Net-(K35C-S)") (class "Default")
      (node (ref "K35") (pin "5") (pinfunction "S_5") (pintype "passive"))
      (node (ref "K36") (pin "7") (pinfunction "O_7") (pintype "passive"))
    )
    (net (code "95") (name "Net-(K36B-O)") (class "Default")
      (node (ref "K36") (pin "2") (pinfunction "O_2") (pintype "passive"))
      (node (ref "K37") (pin "5") (pinfunction "S_5") (pintype "passive"))
    )
    (net (code "96") (name "Net-(K36B-S)") (class "Default")
      (node (ref "K36") (pin "4") (pinfunction "S_4") (pintype "passive"))
      (node (ref "K37") (pin "1") (pinfunction "+_1") (pintype "passive"))
      (node (ref "K37") (pin "3") (pinfunction "P_3") (pintype "passive"))
      (node (ref "R19") (pin "2") (pinfunction "2_2") (pintype "passive"))
    )
    (net (code "97") (name "Net-(K38A-+)") (class "Default")
      (node (ref "K38") (pin "1") (pinfunction "+_1") (pintype "passive"))
      (node (ref "K38") (pin "3") (pinfunction "P_3") (pintype "passive"))
      (node (ref "K39") (pin "5") (pinfunction "S_5") (pintype "passive"))
      (node (ref "R20") (pin "2") (pinfunction "2_2") (pintype "passive"))
    )
    (net (code "98") (name "Net-(K38C-S)") (class "Default")
      (node (ref "K38") (pin "5") (pinfunction "S_5") (pintype "passive"))
      (node (ref "K39") (pin "7") (pinfunction "O_7") (pintype "passive"))
    )
    (net (code "99") (name "Net-(K39B-O)") (class "Default")
      (node (ref "K39") (pin "2") (pinfunction "O_2") (pintype "passive"))
      (node (ref "K40") (pin "5") (pinfunction "S_5") (pintype "passive"))
    )
    (net (code "100") (name "Net-(K39B-S)") (class "Default")
      (node (ref "K39") (pin "4") (pinfunction "S_4") (pintype "passive"))
      (node (ref "K40") (pin "1") (pinfunction "+_1") (pintype "passive"))
      (node (ref "K40") (pin "3") (pinfunction "P_3") (pintype "passive"))
      (node (ref "R21") (pin "2") (pinfunction "2_2") (pintype "passive"))
    )
    (net (code "101") (name "Net-(K41A-+)") (class "Default")
      (node (ref "K41") (pin "1") (pinfunction "+_1") (pintype "passive"))
      (node (ref "K41") (pin "3") (pinfunction "P_3") (pintype "passive"))
      (node (ref "K42") (pin "5") (pinfunction "S_5") (pintype "passive"))
      (node (ref "R22") (pin "2") (pinfunction "2_2") (pintype "passive"))
    )
    (net (code "102") (name "Net-(K41A--)") (class "Default")
      (node (ref "K41") (pin "8") (pinfunction "-_8") (pintype "passive"))
      (node (ref "K42") (pin "8") (pinfunction "-_8") (pintype "passive"))
      (node (ref "K43") (pin "8") (pinfunction "-_8") (pintype "passive"))
      (node (ref "K44") (pin "8") (pinfunction "-_8") (pintype "passive"))
      (node (ref "K45") (pin "8") (pinfunction "-_8") (pintype "passive"))
      (node (ref "K46") (pin "8") (pinfunction "-_8") (pintype "passive"))
      (node (ref "LED21") (pin "K") (pinfunction "C_K") (pintype "passive"))
      (node (ref "LED22") (pin "K") (pinfunction "C_K") (pintype "passive"))
      (node (ref "LED23") (pin "K") (pinfunction "C_K") (pintype "passive"))
      (node (ref "LED24") (pin "K") (pinfunction "C_K") (pintype "passive"))
    )
    (net (code "103") (name "Net-(K41C-S)") (class "Default")
      (node (ref "K41") (pin "5") (pinfunction "S_5") (pintype "passive"))
      (node (ref "K42") (pin "7") (pinfunction "O_7") (pintype "passive"))
    )
    (net (code "104") (name "Net-(K42B-O)") (class "Default")
      (node (ref "K42") (pin "2") (pinfunction "O_2") (pintype "passive"))
      (node (ref "K43") (pin "5") (pinfunction "S_5") (pintype "passive"))
    )
    (net (code "105") (name "Net-(K42B-S)") (class "Default")
      (node (ref "K42") (pin "4") (pinfunction "S_4") (pintype "passive"))
      (node (ref "K43") (pin "1") (pinfunction "+_1") (pintype "passive"))
      (node (ref "K43") (pin "3") (pinfunction "P_3") (pintype "passive"))
      (node (ref "R23") (pin "2") (pinfunction "2_2") (pintype "passive"))
    )
    (net (code "106") (name "Net-(K44A-+)") (class "Default")
      (node (ref "K44") (pin "1") (pinfunction "+_1") (pintype "passive"))
      (node (ref "K44") (pin "3") (pinfunction "P_3") (pintype "passive"))
      (node (ref "K45") (pin "5") (pinfunction "S_5") (pintype "passive"))
      (node (ref "R24") (pin "2") (pinfunction "2_2") (pintype "passive"))
    )
    (net (code "107") (name "Net-(K44C-S)") (class "Default")
      (node (ref "K44") (pin "5") (pinfunction "S_5") (pintype "passive"))
      (node (ref "K45") (pin "7") (pinfunction "O_7") (pintype "passive"))
    )
    (net (code "108") (name "Net-(K45B-O)") (class "Default")
      (node (ref "K45") (pin "2") (pinfunction "O_2") (pintype "passive"))
      (node (ref "K46") (pin "5") (pinfunction "S_5") (pintype "passive"))
    )
    (net (code "109") (name "Net-(K45B-S)") (class "Default")
      (node (ref "K45") (pin "4") (pinfunction "S_4") (pintype "passive"))
      (node (ref "K46") (pin "1") (pinfunction "+_1") (pintype "passive"))
      (node (ref "K46") (pin "3") (pinfunction "P_3") (pintype "passive"))
      (node (ref "R25") (pin "2") (pinfunction "2_2") (pintype "passive"))
    )
    (net (code "110") (name "Net-(K47B-O)") (class "Default")
      (node (ref "JP1") (pin "10") (pinfunction "10_10") (pintype "passive"))
      (node (ref "JP1") (pin "12") (pinfunction "12_12") (pintype "passive"))
      (node (ref "JP1") (pin "14") (pinfunction "14_14") (pintype "passive"))
      (node (ref "JP1") (pin "16") (pinfunction "16_16") (pintype "passive"))
      (node (ref "JP1") (pin "2") (pinfunction "2_2") (pintype "passive"))
      (node (ref "JP1") (pin "4") (pinfunction "4_4") (pintype "passive"))
      (node (ref "JP1") (pin "6") (pinfunction "6_6") (pintype "passive"))
      (node (ref "JP1") (pin "8") (pinfunction "8_8") (pintype "passive"))
      (node (ref "K47") (pin "2") (pinfunction "O_2") (pintype "passive"))
    )
    (net (code "111") (name "Net-(K47B-P)") (class "Default")
      (node (ref "K47") (pin "3") (pinfunction "P_3") (pintype "passive"))
      (node (ref "K49") (pin "2") (pinfunction "O_2") (pintype "passive"))
    )
    (net (code "112") (name "Net-(K47B-S)") (class "Default")
      (node (ref "JP2") (pin "10") (pinfunction "10_10") (pintype "passive"))
      (node (ref "JP2") (pin "12") (pinfunction "12_12") (pintype "passive"))
      (node (ref "JP2") (pin "14") (pinfunction "14_14") (pintype "passive"))
      (node (ref "JP2") (pin "16") (pinfunction "16_16") (pintype "passive"))
      (node (ref "JP2") (pin "2") (pinfunction "2_2") (pintype "passive"))
      (node (ref "JP2") (pin "4") (pinfunction "4_4") (pintype "passive"))
      (node (ref "JP2") (pin "6") (pinfunction "6_6") (pintype "passive"))
      (node (ref "JP2") (pin "8") (pinfunction "8_8") (pintype "passive"))
      (node (ref "K47") (pin "4") (pinfunction "S_4") (pintype "passive"))
    )
    (net (code "113") (name "Net-(K47C-O)") (class "Default")
      (node (ref "JP3") (pin "10") (pinfunction "10_10") (pintype "passive"))
      (node (ref "JP3") (pin "12") (pinfunction "12_12") (pintype "passive"))
      (node (ref "JP3") (pin "14") (pinfunction "14_14") (pintype "passive"))
      (node (ref "JP3") (pin "16") (pinfunction "16_16") (pintype "passive"))
      (node (ref "JP3") (pin "2") (pinfunction "2_2") (pintype "passive"))
      (node (ref "JP3") (pin "4") (pinfunction "4_4") (pintype "passive"))
      (node (ref "JP3") (pin "6") (pinfunction "6_6") (pintype "passive"))
      (node (ref "JP3") (pin "8") (pinfunction "8_8") (pintype "passive"))
      (node (ref "K47") (pin "7") (pinfunction "O_7") (pintype "passive"))
    )
    (net (code "114") (name "Net-(K47C-P)") (class "Default")
      (node (ref "K47") (pin "6") (pinfunction "P_6") (pintype "passive"))
      (node (ref "K49") (pin "4") (pinfunction "S_4") (pintype "passive"))
    )
    (net (code "115") (name "Net-(K47C-S)") (class "Default")
      (node (ref "JP4") (pin "10") (pinfunction "10_10") (pintype "passive"))
      (node (ref "JP4") (pin "12") (pinfunction "12_12") (pintype "passive"))
      (node (ref "JP4") (pin "14") (pinfunction "14_14") (pintype "passive"))
      (node (ref "JP4") (pin "16") (pinfunction "16_16") (pintype "passive"))
      (node (ref "JP4") (pin "2") (pinfunction "2_2") (pintype "passive"))
      (node (ref "JP4") (pin "4") (pinfunction "4_4") (pintype "passive"))
      (node (ref "JP4") (pin "6") (pinfunction "6_6") (pintype "passive"))
      (node (ref "JP4") (pin "8") (pinfunction "8_8") (pintype "passive"))
      (node (ref "K47") (pin "5") (pinfunction "S_5") (pintype "passive"))
    )
    (net (code "116") (name "Net-(K48B-O)") (class "Default")
      (node (ref "JP5") (pin "10") (pinfunction "10_10") (pintype "passive"))
      (node (ref "JP5") (pin "12") (pinfunction "12_12") (pintype "passive"))
      (node (ref "JP5") (pin "14") (pinfunction "14_14") (pintype "passive"))
      (node (ref "JP5") (pin "16") (pinfunction "16_16") (pintype "passive"))
      (node (ref "JP5") (pin "2") (pinfunction "2_2") (pintype "passive"))
      (node (ref "JP5") (pin "4") (pinfunction "4_4") (pintype "passive"))
      (node (ref "JP5") (pin "6") (pinfunction "6_6") (pintype "passive"))
      (node (ref "JP5") (pin "8") (pinfunction "8_8") (pintype "passive"))
      (node (ref "K48") (pin "2") (pinfunction "O_2") (pintype "passive"))
    )
    (net (code "117") (name "Net-(K48B-P)") (class "Default")
      (node (ref "K48") (pin "3") (pinfunction "P_3") (pintype "passive"))
      (node (ref "K49") (pin "7") (pinfunction "O_7") (pintype "passive"))
    )
    (net (code "118") (name "Net-(K48B-S)") (class "Default")
      (node (ref "JP6") (pin "10") (pinfunction "10_10") (pintype "passive"))
      (node (ref "JP6") (pin "12") (pinfunction "12_12") (pintype "passive"))
      (node (ref "JP6") (pin "14") (pinfunction "14_14") (pintype "passive"))
      (node (ref "JP6") (pin "16") (pinfunction "16_16") (pintype "passive"))
      (node (ref "JP6") (pin "2") (pinfunction "2_2") (pintype "passive"))
      (node (ref "JP6") (pin "4") (pinfunction "4_4") (pintype "passive"))
      (node (ref "JP6") (pin "6") (pinfunction "6_6") (pintype "passive"))
      (node (ref "JP6") (pin "8") (pinfunction "8_8") (pintype "passive"))
      (node (ref "K48") (pin "4") (pinfunction "S_4") (pintype "passive"))
    )
    (net (code "119") (name "Net-(K48C-O)") (class "Default")
      (node (ref "JP7") (pin "10") (pinfunction "10_10") (pintype "passive"))
      (node (ref "JP7") (pin "12") (pinfunction "12_12") (pintype "passive"))
      (node (ref "JP7") (pin "14") (pinfunction "14_14") (pintype "passive"))
      (node (ref "JP7") (pin "16") (pinfunction "16_16") (pintype "passive"))
      (node (ref "JP7") (pin "2") (pinfunction "2_2") (pintype "passive"))
      (node (ref "JP7") (pin "4") (pinfunction "4_4") (pintype "passive"))
      (node (ref "JP7") (pin "6") (pinfunction "6_6") (pintype "passive"))
      (node (ref "JP7") (pin "8") (pinfunction "8_8") (pintype "passive"))
      (node (ref "K48") (pin "7") (pinfunction "O_7") (pintype "passive"))
    )
    (net (code "120") (name "Net-(K48C-P)") (class "Default")
      (node (ref "K48") (pin "6") (pinfunction "P_6") (pintype "passive"))
      (node (ref "K49") (pin "5") (pinfunction "S_5") (pintype "passive"))
    )
    (net (code "121") (name "Net-(K48C-S)") (class "Default")
      (node (ref "JP8") (pin "10") (pinfunction "10_10") (pintype "passive"))
      (node (ref "JP8") (pin "12") (pinfunction "12_12") (pintype "passive"))
      (node (ref "JP8") (pin "14") (pinfunction "14_14") (pintype "passive"))
      (node (ref "JP8") (pin "16") (pinfunction "16_16") (pintype "passive"))
      (node (ref "JP8") (pin "2") (pinfunction "2_2") (pintype "passive"))
      (node (ref "JP8") (pin "4") (pinfunction "4_4") (pintype "passive"))
      (node (ref "JP8") (pin "6") (pinfunction "6_6") (pintype "passive"))
      (node (ref "JP8") (pin "8") (pinfunction "8_8") (pintype "passive"))
      (node (ref "K48") (pin "5") (pinfunction "S_5") (pintype "passive"))
    )
    (net (code "122") (name "Net-(K49B-P)") (class "Default")
      (node (ref "K49") (pin "3") (pinfunction "P_3") (pintype "passive"))
      (node (ref "K54") (pin "2") (pinfunction "O_2") (pintype "passive"))
    )
    (net (code "123") (name "Net-(K49C-P)") (class "Default")
      (node (ref "K49") (pin "6") (pinfunction "P_6") (pintype "passive"))
      (node (ref "K54") (pin "4") (pinfunction "S_4") (pintype "passive"))
    )
    (net (code "124") (name "Net-(K50B-O)") (class "Default")
      (node (ref "JP9") (pin "10") (pinfunction "10_10") (pintype "passive"))
      (node (ref "JP9") (pin "12") (pinfunction "12_12") (pintype "passive"))
      (node (ref "JP9") (pin "14") (pinfunction "14_14") (pintype "passive"))
      (node (ref "JP9") (pin "16") (pinfunction "16_16") (pintype "passive"))
      (node (ref "JP9") (pin "2") (pinfunction "2_2") (pintype "passive"))
      (node (ref "JP9") (pin "4") (pinfunction "4_4") (pintype "passive"))
      (node (ref "JP9") (pin "6") (pinfunction "6_6") (pintype "passive"))
      (node (ref "JP9") (pin "8") (pinfunction "8_8") (pintype "passive"))
      (node (ref "K50") (pin "2") (pinfunction "O_2") (pintype "passive"))
    )
    (net (code "125") (name "Net-(K50B-P)") (class "Default")
      (node (ref "K50") (pin "3") (pinfunction "P_3") (pintype "passive"))
      (node (ref "K52") (pin "2") (pinfunction "O_2") (pintype "passive"))
    )
    (net (code "126") (name "Net-(K50B-S)") (class "Default")
      (node (ref "JP10") (pin "10") (pinfunction "10_10") (pintype "passive"))
      (node (ref "JP10") (pin "12") (pinfunction "12_12") (pintype "passive"))
      (node (ref "JP10") (pin "14") (pinfunction "14_14") (pintype "passive"))
      (node (ref "JP10") (pin "16") (pinfunction "16_16") (pintype "passive"))
      (node (ref "JP10") (pin "2") (pinfunction "2_2") (pintype "passive"))
      (node (ref "JP10") (pin "4") (pinfunction "4_4") (pintype "passive"))
      (node (ref "JP10") (pin "6") (pinfunction "6_6") (pintype "passive"))
      (node (ref "JP10") (pin "8") (pinfunction "8_8") (pintype "passive"))
      (node (ref "K50") (pin "4") (pinfunction "S_4") (pintype "passive"))
    )
    (net (code "127") (name "Net-(K50C-O)") (class "Default")
      (node (ref "JP11") (pin "10") (pinfunction "10_10") (pintype "passive"))
      (node (ref "JP11") (pin "12") (pinfunction "12_12") (pintype "passive"))
      (node (ref "JP11") (pin "14") (pinfunction "14_14") (pintype "passive"))
      (node (ref "JP11") (pin "16") (pinfunction "16_16") (pintype "passive"))
      (node (ref "JP11") (pin "2") (pinfunction "2_2") (pintype "passive"))
      (node (ref "JP11") (pin "4") (pinfunction "4_4") (pintype "passive"))
      (node (ref "JP11") (pin "6") (pinfunction "6_6") (pintype "passive"))
      (node (ref "JP11") (pin "8") (pinfunction "8_8") (pintype "passive"))
      (node (ref "K50") (pin "7") (pinfunction "O_7") (pintype "passive"))
    )
    (net (code "128") (name "Net-(K50C-P)") (class "Default")
      (node (ref "K50") (pin "6") (pinfunction "P_6") (pintype "passive"))
      (node (ref "K52") (pin "4") (pinfunction "S_4") (pintype "passive"))
    )
    (net (code "129") (name "Net-(K50C-S)") (class "Default")
      (node (ref "JP12") (pin "10") (pinfunction "10_10") (pintype "passive"))
      (node (ref "JP12") (pin "12") (pinfunction "12_12") (pintype "passive"))
      (node (ref "JP12") (pin "14") (pinfunction "14_14") (pintype "passive"))
      (node (ref "JP12") (pin "16") (pinfunction "16_16") (pintype "passive"))
      (node (ref "JP12") (pin "2") (pinfunction "2_2") (pintype "passive"))
      (node (ref "JP12") (pin "4") (pinfunction "4_4") (pintype "passive"))
      (node (ref "JP12") (pin "6") (pinfunction "6_6") (pintype "passive"))
      (node (ref "JP12") (pin "8") (pinfunction "8_8") (pintype "passive"))
      (node (ref "K50") (pin "5") (pinfunction "S_5") (pintype "passive"))
    )
    (net (code "130") (name "Net-(K51B-O)") (class "Default")
      (node (ref "JP13") (pin "10") (pinfunction "10_10") (pintype "passive"))
      (node (ref "JP13") (pin "12") (pinfunction "12_12") (pintype "passive"))
      (node (ref "JP13") (pin "14") (pinfunction "14_14") (pintype "passive"))
      (node (ref "JP13") (pin "16") (pinfunction "16_16") (pintype "passive"))
      (node (ref "JP13") (pin "2") (pinfunction "2_2") (pintype "passive"))
      (node (ref "JP13") (pin "4") (pinfunction "4_4") (pintype "passive"))
      (node (ref "JP13") (pin "6") (pinfunction "6_6") (pintype "passive"))
      (node (ref "JP13") (pin "8") (pinfunction "8_8") (pintype "passive"))
      (node (ref "K51") (pin "2") (pinfunction "O_2") (pintype "passive"))
    )
    (net (code "131") (name "Net-(K51B-P)") (class "Default")
      (node (ref "K51") (pin "3") (pinfunction "P_3") (pintype "passive"))
      (node (ref "K52") (pin "7") (pinfunction "O_7") (pintype "passive"))
    )
    (net (code "132") (name "Net-(K51B-S)") (class "Default")
      (node (ref "JP14") (pin "10") (pinfunction "10_10") (pintype "passive"))
      (node (ref "JP14") (pin "12") (pinfunction "12_12") (pintype "passive"))
      (node (ref "JP14") (pin "14") (pinfunction "14_14") (pintype "passive"))
      (node (ref "JP14") (pin "16") (pinfunction "16_16") (pintype "passive"))
      (node (ref "JP14") (pin "2") (pinfunction "2_2") (pintype "passive"))
      (node (ref "JP14") (pin "4") (pinfunction "4_4") (pintype "passive"))
      (node (ref "JP14") (pin "6") (pinfunction "6_6") (pintype "passive"))
      (node (ref "JP14") (pin "8") (pinfunction "8_8") (pintype "passive"))
      (node (ref "K51") (pin "4") (pinfunction "S_4") (pintype "passive"))
    )
    (net (code "133") (name "Net-(K51C-O)") (class "Default")
      (node (ref "JP15") (pin "10") (pinfunction "10_10") (pintype "passive"))
      (node (ref "JP15") (pin "12") (pinfunction "12_12") (pintype "passive"))
      (node (ref "JP15") (pin "14") (pinfunction "14_14") (pintype "passive"))
      (node (ref "JP15") (pin "16") (pinfunction "16_16") (pintype "passive"))
      (node (ref "JP15") (pin "2") (pinfunction "2_2") (pintype "passive"))
      (node (ref "JP15") (pin "4") (pinfunction "4_4") (pintype "passive"))
      (node (ref "JP15") (pin "6") (pinfunction "6_6") (pintype "passive"))
      (node (ref "JP15") (pin "8") (pinfunction "8_8") (pintype "passive"))
      (node (ref "K51") (pin "7") (pinfunction "O_7") (pintype "passive"))
    )
    (net (code "134") (name "Net-(K51C-P)") (class "Default")
      (node (ref "K51") (pin "6") (pinfunction "P_6") (pintype "passive"))
      (node (ref "K52") (pin "5") (pinfunction "S_5") (pintype "passive"))
    )
    (net (code "135") (name "Net-(K51C-S)") (class "Default")
      (node (ref "JP16") (pin "10") (pinfunction "10_10") (pintype "passive"))
      (node (ref "JP16") (pin "12") (pinfunction "12_12") (pintype "passive"))
      (node (ref "JP16") (pin "14") (pinfunction "14_14") (pintype "passive"))
      (node (ref "JP16") (pin "16") (pinfunction "16_16") (pintype "passive"))
      (node (ref "JP16") (pin "2") (pinfunction "2_2") (pintype "passive"))
      (node (ref "JP16") (pin "4") (pinfunction "4_4") (pintype "passive"))
      (node (ref "JP16") (pin "6") (pinfunction "6_6") (pintype "passive"))
      (node (ref "JP16") (pin "8") (pinfunction "8_8") (pintype "passive"))
      (node (ref "K51") (pin "5") (pinfunction "S_5") (pintype "passive"))
    )
    (net (code "136") (name "Net-(K52B-P)") (class "Default")
      (node (ref "K52") (pin "3") (pinfunction "P_3") (pintype "passive"))
      (node (ref "K54") (pin "7") (pinfunction "O_7") (pintype "passive"))
    )
    (net (code "137") (name "Net-(K52C-P)") (class "Default")
      (node (ref "K52") (pin "6") (pinfunction "P_6") (pintype "passive"))
      (node (ref "K54") (pin "5") (pinfunction "S_5") (pintype "passive"))
    )
    (net (code "138") (name "Net-(K53B-O)") (class "Default")
      (node (ref "K53") (pin "2") (pinfunction "O_2") (pintype "passive"))
      (node (ref "K54") (pin "3") (pinfunction "P_3") (pintype "passive"))
    )
    (net (code "139") (name "Net-(K53B-P)") (class "Default")
      (node (ref "K53") (pin "3") (pinfunction "P_3") (pintype "passive"))
      (node (ref "K55") (pin "2") (pinfunction "O_2") (pintype "passive"))
    )
    (net (code "140") (name "Net-(K53B-S)") (class "Default")
      (node (ref "K53") (pin "4") (pinfunction "S_4") (pintype "passive"))
      (node (ref "K54") (pin "6") (pinfunction "P_6") (pintype "passive"))
    )
    (net (code "141") (name "Net-(K53C-O)") (class "Default")
      (node (ref "K53") (pin "7") (pinfunction "O_7") (pintype "passive"))
      (node (ref "K56") (pin "3") (pinfunction "P_3") (pintype "passive"))
    )
    (net (code "142") (name "Net-(K53C-P)") (class "Default")
      (node (ref "K53") (pin "6") (pinfunction "P_6") (pintype "passive"))
      (node (ref "K55") (pin "4") (pinfunction "S_4") (pintype "passive"))
    )
    (net (code "143") (name "Net-(K53C-S)") (class "Default")
      (node (ref "K53") (pin "5") (pinfunction "S_5") (pintype "passive"))
      (node (ref "K56") (pin "6") (pinfunction "P_6") (pintype "passive"))
    )
    (net (code "144") (name "Net-(K55B-P)") (class "Default")
      (node (ref "K55") (pin "3") (pinfunction "P_3") (pintype "passive"))
      (node (ref "K73") (pin "2") (pinfunction "O_2") (pintype "passive"))
    )
    (net (code "145") (name "Net-(K56B-O)") (class "Default")
      (node (ref "K56") (pin "2") (pinfunction "O_2") (pintype "passive"))
      (node (ref "K57") (pin "3") (pinfunction "P_3") (pintype "passive"))
    )
    (net (code "146") (name "Net-(K56B-S)") (class "Default")
      (node (ref "K56") (pin "4") (pinfunction "S_4") (pintype "passive"))
      (node (ref "K57") (pin "6") (pinfunction "P_6") (pintype "passive"))
    )
    (net (code "147") (name "Net-(K56C-O)") (class "Default")
      (node (ref "K56") (pin "7") (pinfunction "O_7") (pintype "passive"))
      (node (ref "K58") (pin "3") (pinfunction "P_3") (pintype "passive"))
    )
    (net (code "148") (name "Net-(K56C-S)") (class "Default")
      (node (ref "K56") (pin "5") (pinfunction "S_5") (pintype "passive"))
      (node (ref "K58") (pin "6") (pinfunction "P_6") (pintype "passive"))
    )
    (net (code "149") (name "Net-(K57B-O)") (class "Default")
      (node (ref "K57") (pin "2") (pinfunction "O_2") (pintype "passive"))
      (node (ref "K59") (pin "3") (pinfunction "P_3") (pintype "passive"))
    )
    (net (code "150") (name "Net-(K57B-S)") (class "Default")
      (node (ref "K57") (pin "4") (pinfunction "S_4") (pintype "passive"))
      (node (ref "K59") (pin "6") (pinfunction "P_6") (pintype "passive"))
    )
    (net (code "151") (name "Net-(K57C-O)") (class "Default")
      (node (ref "K57") (pin "7") (pinfunction "O_7") (pintype "passive"))
      (node (ref "K60") (pin "3") (pinfunction "P_3") (pintype "passive"))
    )
    (net (code "152") (name "Net-(K57C-S)") (class "Default")
      (node (ref "K57") (pin "5") (pinfunction "S_5") (pintype "passive"))
      (node (ref "K60") (pin "6") (pinfunction "P_6") (pintype "passive"))
    )
    (net (code "153") (name "Net-(K58B-O)") (class "Default")
      (node (ref "K58") (pin "2") (pinfunction "O_2") (pintype "passive"))
      (node (ref "K61") (pin "3") (pinfunction "P_3") (pintype "passive"))
    )
    (net (code "154") (name "Net-(K58B-S)") (class "Default")
      (node (ref "K58") (pin "4") (pinfunction "S_4") (pintype "passive"))
      (node (ref "K61") (pin "6") (pinfunction "P_6") (pintype "passive"))
    )
    (net (code "155") (name "Net-(K58C-O)") (class "Default")
      (node (ref "K58") (pin "7") (pinfunction "O_7") (pintype "passive"))
      (node (ref "K62") (pin "3") (pinfunction "P_3") (pintype "passive"))
    )
    (net (code "156") (name "Net-(K58C-S)") (class "Default")
      (node (ref "K58") (pin "5") (pinfunction "S_5") (pintype "passive"))
      (node (ref "K62") (pin "6") (pinfunction "P_6") (pintype "passive"))
    )
    (net (code "157") (name "Net-(K59B-O)") (class "Default")
      (node (ref "JP17") (pin "10") (pinfunction "10_10") (pintype "passive"))
      (node (ref "JP17") (pin "12") (pinfunction "12_12") (pintype "passive"))
      (node (ref "JP17") (pin "14") (pinfunction "14_14") (pintype "passive"))
      (node (ref "JP17") (pin "16") (pinfunction "16_16") (pintype "passive"))
      (node (ref "JP17") (pin "2") (pinfunction "2_2") (pintype "passive"))
      (node (ref "JP17") (pin "4") (pinfunction "4_4") (pintype "passive"))
      (node (ref "JP17") (pin "6") (pinfunction "6_6") (pintype "passive"))
      (node (ref "JP17") (pin "8") (pinfunction "8_8") (pintype "passive"))
      (node (ref "K59") (pin "2") (pinfunction "O_2") (pintype "passive"))
    )
    (net (code "158") (name "Net-(K59B-S)") (class "Default")
      (node (ref "JP18") (pin "10") (pinfunction "10_10") (pintype "passive"))
      (node (ref "JP18") (pin "12") (pinfunction "12_12") (pintype "passive"))
      (node (ref "JP18") (pin "14") (pinfunction "14_14") (pintype "passive"))
      (node (ref "JP18") (pin "16") (pinfunction "16_16") (pintype "passive"))
      (node (ref "JP18") (pin "2") (pinfunction "2_2") (pintype "passive"))
      (node (ref "JP18") (pin "4") (pinfunction "4_4") (pintype "passive"))
      (node (ref "JP18") (pin "6") (pinfunction "6_6") (pintype "passive"))
      (node (ref "JP18") (pin "8") (pinfunction "8_8") (pintype "passive"))
      (node (ref "K59") (pin "4") (pinfunction "S_4") (pintype "passive"))
    )
    (net (code "159") (name "Net-(K59C-O)") (class "Default")
      (node (ref "JP19") (pin "10") (pinfunction "10_10") (pintype "passive"))
      (node (ref "JP19") (pin "12") (pinfunction "12_12") (pintype "passive"))
      (node (ref "JP19") (pin "14") (pinfunction "14_14") (pintype "passive"))
      (node (ref "JP19") (pin "16") (pinfunction "16_16") (pintype "passive"))
      (node (ref "JP19") (pin "2") (pinfunction "2_2") (pintype "passive"))
      (node (ref "JP19") (pin "4") (pinfunction "4_4") (pintype "passive"))
      (node (ref "JP19") (pin "6") (pinfunction "6_6") (pintype "passive"))
      (node (ref "JP19") (pin "8") (pinfunction "8_8") (pintype "passive"))
      (node (ref "K59") (pin "7") (pinfunction "O_7") (pintype "passive"))
    )
    (net (code "160") (name "Net-(K59C-S)") (class "Default")
      (node (ref "JP20") (pin "10") (pinfunction "10_10") (pintype "passive"))
      (node (ref "JP20") (pin "12") (pinfunction "12_12") (pintype "passive"))
      (node (ref "JP20") (pin "14") (pinfunction "14_14") (pintype "passive"))
      (node (ref "JP20") (pin "16") (pinfunction "16_16") (pintype "passive"))
      (node (ref "JP20") (pin "2") (pinfunction "2_2") (pintype "passive"))
      (node (ref "JP20") (pin "4") (pinfunction "4_4") (pintype "passive"))
      (node (ref "JP20") (pin "6") (pinfunction "6_6") (pintype "passive"))
      (node (ref "JP20") (pin "8") (pinfunction "8_8") (pintype "passive"))
      (node (ref "K59") (pin "5") (pinfunction "S_5") (pintype "passive"))
    )
    (net (code "161") (name "Net-(K60B-O)") (class "Default")
      (node (ref "JP21") (pin "10") (pinfunction "10_10") (pintype "passive"))
      (node (ref "JP21") (pin "12") (pinfunction "12_12") (pintype "passive"))
      (node (ref "JP21") (pin "14") (pinfunction "14_14") (pintype "passive"))
      (node (ref "JP21") (pin "16") (pinfunction "16_16") (pintype "passive"))
      (node (ref "JP21") (pin "2") (pinfunction "2_2") (pintype "passive"))
      (node (ref "JP21") (pin "4") (pinfunction "4_4") (pintype "passive"))
      (node (ref "JP21") (pin "6") (pinfunction "6_6") (pintype "passive"))
      (node (ref "JP21") (pin "8") (pinfunction "8_8") (pintype "passive"))
      (node (ref "K60") (pin "2") (pinfunction "O_2") (pintype "passive"))
    )
    (net (code "162") (name "Net-(K60B-S)") (class "Default")
      (node (ref "JP22") (pin "10") (pinfunction "10_10") (pintype "passive"))
      (node (ref "JP22") (pin "12") (pinfunction "12_12") (pintype "passive"))
      (node (ref "JP22") (pin "14") (pinfunction "14_14") (pintype "passive"))
      (node (ref "JP22") (pin "16") (pinfunction "16_16") (pintype "passive"))
      (node (ref "JP22") (pin "2") (pinfunction "2_2") (pintype "passive"))
      (node (ref "JP22") (pin "4") (pinfunction "4_4") (pintype "passive"))
      (node (ref "JP22") (pin "6") (pinfunction "6_6") (pintype "passive"))
      (node (ref "JP22") (pin "8") (pinfunction "8_8") (pintype "passive"))
      (node (ref "K60") (pin "4") (pinfunction "S_4") (pintype "passive"))
    )
    (net (code "163") (name "Net-(K60C-O)") (class "Default")
      (node (ref "JP23") (pin "10") (pinfunction "10_10") (pintype "passive"))
      (node (ref "JP23") (pin "12") (pinfunction "12_12") (pintype "passive"))
      (node (ref "JP23") (pin "14") (pinfunction "14_14") (pintype "passive"))
      (node (ref "JP23") (pin "16") (pinfunction "16_16") (pintype "passive"))
      (node (ref "JP23") (pin "2") (pinfunction "2_2") (pintype "passive"))
      (node (ref "JP23") (pin "4") (pinfunction "4_4") (pintype "passive"))
      (node (ref "JP23") (pin "6") (pinfunction "6_6") (pintype "passive"))
      (node (ref "JP23") (pin "8") (pinfunction "8_8") (pintype "passive"))
      (node (ref "K60") (pin "7") (pinfunction "O_7") (pintype "passive"))
    )
    (net (code "164") (name "Net-(K60C-S)") (class "Default")
      (node (ref "JP24") (pin "10") (pinfunction "10_10") (pintype "passive"))
      (node (ref "JP24") (pin "12") (pinfunction "12_12") (pintype "passive"))
      (node (ref "JP24") (pin "14") (pinfunction "14_14") (pintype "passive"))
      (node (ref "JP24") (pin "16") (pinfunction "16_16") (pintype "passive"))
      (node (ref "JP24") (pin "2") (pinfunction "2_2") (pintype "passive"))
      (node (ref "JP24") (pin "4") (pinfunction "4_4") (pintype "passive"))
      (node (ref "JP24") (pin "6") (pinfunction "6_6") (pintype "passive"))
      (node (ref "JP24") (pin "8") (pinfunction "8_8") (pintype "passive"))
      (node (ref "K60") (pin "5") (pinfunction "S_5") (pintype "passive"))
    )
    (net (code "165") (name "Net-(K61B-O)") (class "Default")
      (node (ref "JP25") (pin "10") (pinfunction "10_10") (pintype "passive"))
      (node (ref "JP25") (pin "12") (pinfunction "12_12") (pintype "passive"))
      (node (ref "JP25") (pin "14") (pinfunction "14_14") (pintype "passive"))
      (node (ref "JP25") (pin "16") (pinfunction "16_16") (pintype "passive"))
      (node (ref "JP25") (pin "2") (pinfunction "2_2") (pintype "passive"))
      (node (ref "JP25") (pin "4") (pinfunction "4_4") (pintype "passive"))
      (node (ref "JP25") (pin "6") (pinfunction "6_6") (pintype "passive"))
      (node (ref "JP25") (pin "8") (pinfunction "8_8") (pintype "passive"))
      (node (ref "K61") (pin "2") (pinfunction "O_2") (pintype "passive"))
    )
    (net (code "166") (name "Net-(K61B-S)") (class "Default")
      (node (ref "JP26") (pin "10") (pinfunction "10_10") (pintype "passive"))
      (node (ref "JP26") (pin "12") (pinfunction "12_12") (pintype "passive"))
      (node (ref "JP26") (pin "14") (pinfunction "14_14") (pintype "passive"))
      (node (ref "JP26") (pin "16") (pinfunction "16_16") (pintype "passive"))
      (node (ref "JP26") (pin "2") (pinfunction "2_2") (pintype "passive"))
      (node (ref "JP26") (pin "4") (pinfunction "4_4") (pintype "passive"))
      (node (ref "JP26") (pin "6") (pinfunction "6_6") (pintype "passive"))
      (node (ref "JP26") (pin "8") (pinfunction "8_8") (pintype "passive"))
      (node (ref "K61") (pin "4") (pinfunction "S_4") (pintype "passive"))
    )
    (net (code "167") (name "Net-(K61C-O)") (class "Default")
      (node (ref "JP27") (pin "10") (pinfunction "10_10") (pintype "passive"))
      (node (ref "JP27") (pin "12") (pinfunction "12_12") (pintype "passive"))
      (node (ref "JP27") (pin "14") (pinfunction "14_14") (pintype "passive"))
      (node (ref "JP27") (pin "16") (pinfunction "16_16") (pintype "passive"))
      (node (ref "JP27") (pin "2") (pinfunction "2_2") (pintype "passive"))
      (node (ref "JP27") (pin "4") (pinfunction "4_4") (pintype "passive"))
      (node (ref "JP27") (pin "6") (pinfunction "6_6") (pintype "passive"))
      (node (ref "JP27") (pin "8") (pinfunction "8_8") (pintype "passive"))
      (node (ref "K61") (pin "7") (pinfunction "O_7") (pintype "passive"))
    )
    (net (code "168") (name "Net-(K61C-S)") (class "Default")
      (node (ref "JP28") (pin "10") (pinfunction "10_10") (pintype "passive"))
      (node (ref "JP28") (pin "12") (pinfunction "12_12") (pintype "passive"))
      (node (ref "JP28") (pin "14") (pinfunction "14_14") (pintype "passive"))
      (node (ref "JP28") (pin "16") (pinfunction "16_16") (pintype "passive"))
      (node (ref "JP28") (pin "2") (pinfunction "2_2") (pintype "passive"))
      (node (ref "JP28") (pin "4") (pinfunction "4_4") (pintype "passive"))
      (node (ref "JP28") (pin "6") (pinfunction "6_6") (pintype "passive"))
      (node (ref "JP28") (pin "8") (pinfunction "8_8") (pintype "passive"))
      (node (ref "K61") (pin "5") (pinfunction "S_5") (pintype "passive"))
    )
    (net (code "169") (name "Net-(K62B-O)") (class "Default")
      (node (ref "JP29") (pin "10") (pinfunction "10_10") (pintype "passive"))
      (node (ref "JP29") (pin "12") (pinfunction "12_12") (pintype "passive"))
      (node (ref "JP29") (pin "14") (pinfunction "14_14") (pintype "passive"))
      (node (ref "JP29") (pin "16") (pinfunction "16_16") (pintype "passive"))
      (node (ref "JP29") (pin "2") (pinfunction "2_2") (pintype "passive"))
      (node (ref "JP29") (pin "4") (pinfunction "4_4") (pintype "passive"))
      (node (ref "JP29") (pin "6") (pinfunction "6_6") (pintype "passive"))
      (node (ref "JP29") (pin "8") (pinfunction "8_8") (pintype "passive"))
      (node (ref "K62") (pin "2") (pinfunction "O_2") (pintype "passive"))
    )
    (net (code "170") (name "Net-(K62B-S)") (class "Default")
      (node (ref "JP30") (pin "10") (pinfunction "10_10") (pintype "passive"))
      (node (ref "JP30") (pin "12") (pinfunction "12_12") (pintype "passive"))
      (node (ref "JP30") (pin "14") (pinfunction "14_14") (pintype "passive"))
      (node (ref "JP30") (pin "16") (pinfunction "16_16") (pintype "passive"))
      (node (ref "JP30") (pin "2") (pinfunction "2_2") (pintype "passive"))
      (node (ref "JP30") (pin "4") (pinfunction "4_4") (pintype "passive"))
      (node (ref "JP30") (pin "6") (pinfunction "6_6") (pintype "passive"))
      (node (ref "JP30") (pin "8") (pinfunction "8_8") (pintype "passive"))
      (node (ref "K62") (pin "4") (pinfunction "S_4") (pintype "passive"))
    )
    (net (code "171") (name "Net-(K62C-O)") (class "Default")
      (node (ref "JP31") (pin "10") (pinfunction "10_10") (pintype "passive"))
      (node (ref "JP31") (pin "12") (pinfunction "12_12") (pintype "passive"))
      (node (ref "JP31") (pin "14") (pinfunction "14_14") (pintype "passive"))
      (node (ref "JP31") (pin "16") (pinfunction "16_16") (pintype "passive"))
      (node (ref "JP31") (pin "2") (pinfunction "2_2") (pintype "passive"))
      (node (ref "JP31") (pin "4") (pinfunction "4_4") (pintype "passive"))
      (node (ref "JP31") (pin "6") (pinfunction "6_6") (pintype "passive"))
      (node (ref "JP31") (pin "8") (pinfunction "8_8") (pintype "passive"))
      (node (ref "K62") (pin "7") (pinfunction "O_7") (pintype "passive"))
    )
    (net (code "172") (name "Net-(K62C-S)") (class "Default")
      (node (ref "JP32") (pin "10") (pinfunction "10_10") (pintype "passive"))
      (node (ref "JP32") (pin "12") (pinfunction "12_12") (pintype "passive"))
      (node (ref "JP32") (pin "14") (pinfunction "14_14") (pintype "passive"))
      (node (ref "JP32") (pin "16") (pinfunction "16_16") (pintype "passive"))
      (node (ref "JP32") (pin "2") (pinfunction "2_2") (pintype "passive"))
      (node (ref "JP32") (pin "4") (pinfunction "4_4") (pintype "passive"))
      (node (ref "JP32") (pin "6") (pinfunction "6_6") (pintype "passive"))
      (node (ref "JP32") (pin "8") (pinfunction "8_8") (pintype "passive"))
      (node (ref "K62") (pin "5") (pinfunction "S_5") (pintype "passive"))
    )
    (net (code "173") (name "Net-(K63A-O)") (class "Default")
      (node (ref "K63") (pin "6") (pinfunction "O_6") (pintype "passive"))
      (node (ref "K65") (pin "3") (pinfunction "P_3") (pintype "passive"))
    )
    (net (code "174") (name "Net-(K63A-P)") (class "Default")
      (node (ref "K63") (pin "4") (pinfunction "P_4") (pintype "passive"))
      (node (ref "K90") (pin "1") (pinfunction "+_1") (pintype "passive"))
      (node (ref "K90") (pin "4") (pinfunction "S_4") (pintype "passive"))
    )
    (net (code "175") (name "Net-(K63A-S)") (class "Default")
      (node (ref "K63") (pin "11") (pinfunction "O_11") (pintype "passive"))
      (node (ref "K63") (pin "8") (pinfunction "S_8") (pintype "passive"))
      (node (ref "K64") (pin "3") (pinfunction "P_3") (pintype "passive"))
      (node (ref "K65") (pin "1") (pinfunction "+_1") (pintype "passive"))
    )
    (net (code "176") (name "Net-(K63B-P)") (class "Default")
      (node (ref "K63") (pin "13") (pinfunction "P_13") (pintype "passive"))
      (node (ref "K66") (pin "16") (pinfunction "2_16") (pintype "passive"))
      (node (ref "K66") (pin "9") (pinfunction "S_9") (pintype "passive"))
      (node (ref "R28") (pin "2") (pinfunction "2_2") (pintype "passive"))
    )
    (net (code "177") (name "Net-(K63B-S)") (class "Default")
      (node (ref "K63") (pin "16") (pinfunction "2_16") (pintype "passive"))
      (node (ref "K63") (pin "9") (pinfunction "S_9") (pintype "passive"))
      (node (ref "K85") (pin "6") (pinfunction "P_6") (pintype "passive"))
      (node (ref "R26") (pin "2") (pinfunction "2_2") (pintype "passive"))
    )
    (net (code "178") (name "Net-(K64B-S)") (class "Default")
      (node (ref "D6") (pin "A") (pinfunction "A_A") (pintype "passive"))
      (node (ref "K64") (pin "4") (pinfunction "S_4") (pintype "passive"))
      (node (ref "K86") (pin "6") (pinfunction "P_6") (pintype "passive"))
    )
    (net (code "179") (name "Net-(K64C-P)") (class "Default")
      (node (ref "K64") (pin "6") (pinfunction "P_6") (pintype "passive"))
      (node (ref "K66") (pin "11") (pinfunction "O_11") (pintype "passive"))
      (node (ref "K66") (pin "8") (pinfunction "S_8") (pintype "passive"))
      (node (ref "K67") (pin "1") (pinfunction "+_1") (pintype "passive"))
    )
    (net (code "180") (name "Net-(K64C-S)") (class "Default")
      (node (ref "D5") (pin "A") (pinfunction "A_A") (pintype "passive"))
      (node (ref "K64") (pin "5") (pinfunction "S_5") (pintype "passive"))
      (node (ref "K87") (pin "6") (pinfunction "P_6") (pintype "passive"))
    )
    (net (code "181") (name "Net-(K66A-O)") (class "Default")
      (node (ref "K66") (pin "6") (pinfunction "O_6") (pintype "passive"))
      (node (ref "K67") (pin "3") (pinfunction "P_3") (pintype "passive"))
    )
    (net (code "182") (name "Net-(K66A-P)") (class "Default")
      (node (ref "K66") (pin "4") (pinfunction "P_4") (pintype "passive"))
      (node (ref "K91") (pin "1") (pinfunction "+_1") (pintype "passive"))
      (node (ref "K91") (pin "4") (pinfunction "S_4") (pintype "passive"))
    )
    (net (code "183") (name "Net-(K66B-P)") (class "Default")
      (node (ref "K66") (pin "13") (pinfunction "P_13") (pintype "passive"))
      (node (ref "K68") (pin "16") (pinfunction "2_16") (pintype "passive"))
      (node (ref "K68") (pin "9") (pinfunction "S_9") (pintype "passive"))
      (node (ref "R30") (pin "2") (pinfunction "2_2") (pintype "passive"))
    )
    (net (code "184") (name "Net-(K68A-O)") (class "Default")
      (node (ref "K68") (pin "6") (pinfunction "O_6") (pintype "passive"))
      (node (ref "K70") (pin "3") (pinfunction "P_3") (pintype "passive"))
    )
    (net (code "185") (name "Net-(K68A-P)") (class "Default")
      (node (ref "K68") (pin "4") (pinfunction "P_4") (pintype "passive"))
      (node (ref "K92") (pin "1") (pinfunction "+_1") (pintype "passive"))
      (node (ref "K92") (pin "4") (pinfunction "S_4") (pintype "passive"))
    )
    (net (code "186") (name "Net-(K68A-S)") (class "Default")
      (node (ref "K68") (pin "11") (pinfunction "O_11") (pintype "passive"))
      (node (ref "K68") (pin "8") (pinfunction "S_8") (pintype "passive"))
      (node (ref "K69") (pin "3") (pinfunction "P_3") (pintype "passive"))
      (node (ref "K70") (pin "1") (pinfunction "+_1") (pintype "passive"))
    )
    (net (code "187") (name "Net-(K68B-P)") (class "Default")
      (node (ref "K68") (pin "13") (pinfunction "P_13") (pintype "passive"))
      (node (ref "K71") (pin "16") (pinfunction "2_16") (pintype "passive"))
      (node (ref "K71") (pin "9") (pinfunction "S_9") (pintype "passive"))
      (node (ref "R32") (pin "2") (pinfunction "2_2") (pintype "passive"))
    )
    (net (code "188") (name "Net-(K69B-S)") (class "Default")
      (node (ref "D4") (pin "A") (pinfunction "A_A") (pintype "passive"))
      (node (ref "K69") (pin "4") (pinfunction "S_4") (pintype "passive"))
      (node (ref "K88") (pin "6") (pinfunction "P_6") (pintype "passive"))
    )
    (net (code "189") (name "Net-(K69C-P)") (class "Default")
      (node (ref "K69") (pin "6") (pinfunction "P_6") (pintype "passive"))
      (node (ref "K71") (pin "11") (pinfunction "O_11") (pintype "passive"))
      (node (ref "K71") (pin "8") (pinfunction "S_8") (pintype "passive"))
      (node (ref "K72") (pin "1") (pinfunction "+_1") (pintype "passive"))
    )
    (net (code "190") (name "Net-(K69C-S)") (class "Default")
      (node (ref "D3") (pin "A") (pinfunction "A_A") (pintype "passive"))
      (node (ref "K69") (pin "5") (pinfunction "S_5") (pintype "passive"))
      (node (ref "K89") (pin "6") (pinfunction "P_6") (pintype "passive"))
    )
    (net (code "191") (name "Net-(K71A-O)") (class "Default")
      (node (ref "K71") (pin "6") (pinfunction "O_6") (pintype "passive"))
      (node (ref "K72") (pin "3") (pinfunction "P_3") (pintype "passive"))
    )
    (net (code "192") (name "Net-(K71A-P)") (class "Default")
      (node (ref "K71") (pin "4") (pinfunction "P_4") (pintype "passive"))
      (node (ref "K93") (pin "1") (pinfunction "+_1") (pintype "passive"))
      (node (ref "K93") (pin "4") (pinfunction "S_4") (pintype "passive"))
    )
    (net (code "193") (name "Net-(K71B-P)") (class "Default")
      (node (ref "K71") (pin "13") (pinfunction "P_13") (pintype "passive"))
      (node (ref "K94") (pin "1") (pinfunction "+_1") (pintype "passive"))
      (node (ref "K94") (pin "4") (pinfunction "S_4") (pintype "passive"))
    )
    (net (code "194") (name "Net-(K74A-+)") (class "Default")
      (node (ref "JP1") (pin "15") (pinfunction "15_15") (pintype "passive"))
      (node (ref "JP10") (pin "15") (pinfunction "15_15") (pintype "passive"))
      (node (ref "JP11") (pin "15") (pinfunction "15_15") (pintype "passive"))
      (node (ref "JP12") (pin "15") (pinfunction "15_15") (pintype "passive"))
      (node (ref "JP13") (pin "15") (pinfunction "15_15") (pintype "passive"))
      (node (ref "JP14") (pin "15") (pinfunction "15_15") (pintype "passive"))
      (node (ref "JP15") (pin "15") (pinfunction "15_15") (pintype "passive"))
      (node (ref "JP16") (pin "15") (pinfunction "15_15") (pintype "passive"))
      (node (ref "JP17") (pin "1") (pinfunction "1_1") (pintype "passive"))
      (node (ref "JP18") (pin "1") (pinfunction "1_1") (pintype "passive"))
      (node (ref "JP19") (pin "1") (pinfunction "1_1") (pintype "passive"))
      (node (ref "JP2") (pin "15") (pinfunction "15_15") (pintype "passive"))
      (node (ref "JP20") (pin "1") (pinfunction "1_1") (pintype "passive"))
      (node (ref "JP21") (pin "1") (pinfunction "1_1") (pintype "passive"))
      (node (ref "JP22") (pin "1") (pinfunction "1_1") (pintype "passive"))
      (node (ref "JP23") (pin "1") (pinfunction "1_1") (pintype "passive"))
      (node (ref "JP24") (pin "1") (pinfunction "1_1") (pintype "passive"))
      (node (ref "JP25") (pin "1") (pinfunction "1_1") (pintype "passive"))
      (node (ref "JP26") (pin "1") (pinfunction "1_1") (pintype "passive"))
      (node (ref "JP27") (pin "1") (pinfunction "1_1") (pintype "passive"))
      (node (ref "JP28") (pin "1") (pinfunction "1_1") (pintype "passive"))
      (node (ref "JP29") (pin "1") (pinfunction "1_1") (pintype "passive"))
      (node (ref "JP3") (pin "15") (pinfunction "15_15") (pintype "passive"))
      (node (ref "JP30") (pin "1") (pinfunction "1_1") (pintype "passive"))
      (node (ref "JP31") (pin "1") (pinfunction "1_1") (pintype "passive"))
      (node (ref "JP32") (pin "1") (pinfunction "1_1") (pintype "passive"))
      (node (ref "JP4") (pin "15") (pinfunction "15_15") (pintype "passive"))
      (node (ref "JP5") (pin "15") (pinfunction "15_15") (pintype "passive"))
      (node (ref "JP6") (pin "15") (pinfunction "15_15") (pintype "passive"))
      (node (ref "JP7") (pin "15") (pinfunction "15_15") (pintype "passive"))
      (node (ref "JP8") (pin "15") (pinfunction "15_15") (pintype "passive"))
      (node (ref "JP9") (pin "15") (pinfunction "15_15") (pintype "passive"))
      (node (ref "K74") (pin "1") (pinfunction "+_1") (pintype "passive"))
      (node (ref "K74") (pin "4") (pinfunction "S_4") (pintype "passive"))
      (node (ref "LED25") (pin "A") (pinfunction "A_A") (pintype "passive"))
    )
    (net (code "195") (name "Net-(K75A-+)") (class "Default")
      (node (ref "JP1") (pin "13") (pinfunction "13_13") (pintype "passive"))
      (node (ref "JP10") (pin "13") (pinfunction "13_13") (pintype "passive"))
      (node (ref "JP11") (pin "13") (pinfunction "13_13") (pintype "passive"))
      (node (ref "JP12") (pin "13") (pinfunction "13_13") (pintype "passive"))
      (node (ref "JP13") (pin "13") (pinfunction "13_13") (pintype "passive"))
      (node (ref "JP14") (pin "13") (pinfunction "13_13") (pintype "passive"))
      (node (ref "JP15") (pin "13") (pinfunction "13_13") (pintype "passive"))
      (node (ref "JP16") (pin "13") (pinfunction "13_13") (pintype "passive"))
      (node (ref "JP17") (pin "3") (pinfunction "3_3") (pintype "passive"))
      (node (ref "JP18") (pin "3") (pinfunction "3_3") (pintype "passive"))
      (node (ref "JP19") (pin "3") (pinfunction "3_3") (pintype "passive"))
      (node (ref "JP2") (pin "13") (pinfunction "13_13") (pintype "passive"))
      (node (ref "JP20") (pin "3") (pinfunction "3_3") (pintype "passive"))
      (node (ref "JP21") (pin "3") (pinfunction "3_3") (pintype "passive"))
      (node (ref "JP22") (pin "3") (pinfunction "3_3") (pintype "passive"))
      (node (ref "JP23") (pin "3") (pinfunction "3_3") (pintype "passive"))
      (node (ref "JP24") (pin "3") (pinfunction "3_3") (pintype "passive"))
      (node (ref "JP25") (pin "3") (pinfunction "3_3") (pintype "passive"))
      (node (ref "JP26") (pin "3") (pinfunction "3_3") (pintype "passive"))
      (node (ref "JP27") (pin "3") (pinfunction "3_3") (pintype "passive"))
      (node (ref "JP28") (pin "3") (pinfunction "3_3") (pintype "passive"))
      (node (ref "JP29") (pin "3") (pinfunction "3_3") (pintype "passive"))
      (node (ref "JP3") (pin "13") (pinfunction "13_13") (pintype "passive"))
      (node (ref "JP30") (pin "3") (pinfunction "3_3") (pintype "passive"))
      (node (ref "JP31") (pin "3") (pinfunction "3_3") (pintype "passive"))
      (node (ref "JP32") (pin "3") (pinfunction "3_3") (pintype "passive"))
      (node (ref "JP4") (pin "13") (pinfunction "13_13") (pintype "passive"))
      (node (ref "JP5") (pin "13") (pinfunction "13_13") (pintype "passive"))
      (node (ref "JP6") (pin "13") (pinfunction "13_13") (pintype "passive"))
      (node (ref "JP7") (pin "13") (pinfunction "13_13") (pintype "passive"))
      (node (ref "JP8") (pin "13") (pinfunction "13_13") (pintype "passive"))
      (node (ref "JP9") (pin "13") (pinfunction "13_13") (pintype "passive"))
      (node (ref "K75") (pin "1") (pinfunction "+_1") (pintype "passive"))
      (node (ref "K75") (pin "4") (pinfunction "S_4") (pintype "passive"))
      (node (ref "LED26") (pin "A") (pinfunction "A_A") (pintype "passive"))
    )
    (net (code "196") (name "Net-(K76A-+)") (class "Default")
      (node (ref "JP1") (pin "11") (pinfunction "11_11") (pintype "passive"))
      (node (ref "JP10") (pin "11") (pinfunction "11_11") (pintype "passive"))
      (node (ref "JP11") (pin "11") (pinfunction "11_11") (pintype "passive"))
      (node (ref "JP12") (pin "11") (pinfunction "11_11") (pintype "passive"))
      (node (ref "JP13") (pin "11") (pinfunction "11_11") (pintype "passive"))
      (node (ref "JP14") (pin "11") (pinfunction "11_11") (pintype "passive"))
      (node (ref "JP15") (pin "11") (pinfunction "11_11") (pintype "passive"))
      (node (ref "JP16") (pin "11") (pinfunction "11_11") (pintype "passive"))
      (node (ref "JP17") (pin "5") (pinfunction "5_5") (pintype "passive"))
      (node (ref "JP18") (pin "5") (pinfunction "5_5") (pintype "passive"))
      (node (ref "JP19") (pin "5") (pinfunction "5_5") (pintype "passive"))
      (node (ref "JP2") (pin "11") (pinfunction "11_11") (pintype "passive"))
      (node (ref "JP20") (pin "5") (pinfunction "5_5") (pintype "passive"))
      (node (ref "JP21") (pin "5") (pinfunction "5_5") (pintype "passive"))
      (node (ref "JP22") (pin "5") (pinfunction "5_5") (pintype "passive"))
      (node (ref "JP23") (pin "5") (pinfunction "5_5") (pintype "passive"))
      (node (ref "JP24") (pin "5") (pinfunction "5_5") (pintype "passive"))
      (node (ref "JP25") (pin "5") (pinfunction "5_5") (pintype "passive"))
      (node (ref "JP26") (pin "5") (pinfunction "5_5") (pintype "passive"))
      (node (ref "JP27") (pin "5") (pinfunction "5_5") (pintype "passive"))
      (node (ref "JP28") (pin "5") (pinfunction "5_5") (pintype "passive"))
      (node (ref "JP29") (pin "5") (pinfunction "5_5") (pintype "passive"))
      (node (ref "JP3") (pin "11") (pinfunction "11_11") (pintype "passive"))
      (node (ref "JP30") (pin "5") (pinfunction "5_5") (pintype "passive"))
      (node (ref "JP31") (pin "5") (pinfunction "5_5") (pintype "passive"))
      (node (ref "JP32") (pin "5") (pinfunction "5_5") (pintype "passive"))
      (node (ref "JP4") (pin "11") (pinfunction "11_11") (pintype "passive"))
      (node (ref "JP5") (pin "11") (pinfunction "11_11") (pintype "passive"))
      (node (ref "JP6") (pin "11") (pinfunction "11_11") (pintype "passive"))
      (node (ref "JP7") (pin "11") (pinfunction "11_11") (pintype "passive"))
      (node (ref "JP8") (pin "11") (pinfunction "11_11") (pintype "passive"))
      (node (ref "JP9") (pin "11") (pinfunction "11_11") (pintype "passive"))
      (node (ref "K76") (pin "1") (pinfunction "+_1") (pintype "passive"))
      (node (ref "K76") (pin "4") (pinfunction "S_4") (pintype "passive"))
      (node (ref "LED27") (pin "A") (pinfunction "A_A") (pintype "passive"))
    )
    (net (code "197") (name "Net-(K77A-+)") (class "Default")
      (node (ref "JP1") (pin "9") (pinfunction "9_9") (pintype "passive"))
      (node (ref "JP10") (pin "9") (pinfunction "9_9") (pintype "passive"))
      (node (ref "JP11") (pin "9") (pinfunction "9_9") (pintype "passive"))
      (node (ref "JP12") (pin "9") (pinfunction "9_9") (pintype "passive"))
      (node (ref "JP13") (pin "9") (pinfunction "9_9") (pintype "passive"))
      (node (ref "JP14") (pin "9") (pinfunction "9_9") (pintype "passive"))
      (node (ref "JP15") (pin "9") (pinfunction "9_9") (pintype "passive"))
      (node (ref "JP16") (pin "9") (pinfunction "9_9") (pintype "passive"))
      (node (ref "JP17") (pin "7") (pinfunction "7_7") (pintype "passive"))
      (node (ref "JP18") (pin "7") (pinfunction "7_7") (pintype "passive"))
      (node (ref "JP19") (pin "7") (pinfunction "7_7") (pintype "passive"))
      (node (ref "JP2") (pin "9") (pinfunction "9_9") (pintype "passive"))
      (node (ref "JP20") (pin "7") (pinfunction "7_7") (pintype "passive"))
      (node (ref "JP21") (pin "7") (pinfunction "7_7") (pintype "passive"))
      (node (ref "JP22") (pin "7") (pinfunction "7_7") (pintype "passive"))
      (node (ref "JP23") (pin "7") (pinfunction "7_7") (pintype "passive"))
      (node (ref "JP24") (pin "7") (pinfunction "7_7") (pintype "passive"))
      (node (ref "JP25") (pin "7") (pinfunction "7_7") (pintype "passive"))
      (node (ref "JP26") (pin "7") (pinfunction "7_7") (pintype "passive"))
      (node (ref "JP27") (pin "7") (pinfunction "7_7") (pintype "passive"))
      (node (ref "JP28") (pin "7") (pinfunction "7_7") (pintype "passive"))
      (node (ref "JP29") (pin "7") (pinfunction "7_7") (pintype "passive"))
      (node (ref "JP3") (pin "9") (pinfunction "9_9") (pintype "passive"))
      (node (ref "JP30") (pin "7") (pinfunction "7_7") (pintype "passive"))
      (node (ref "JP31") (pin "7") (pinfunction "7_7") (pintype "passive"))
      (node (ref "JP32") (pin "7") (pinfunction "7_7") (pintype "passive"))
      (node (ref "JP4") (pin "9") (pinfunction "9_9") (pintype "passive"))
      (node (ref "JP5") (pin "9") (pinfunction "9_9") (pintype "passive"))
      (node (ref "JP6") (pin "9") (pinfunction "9_9") (pintype "passive"))
      (node (ref "JP7") (pin "9") (pinfunction "9_9") (pintype "passive"))
      (node (ref "JP8") (pin "9") (pinfunction "9_9") (pintype "passive"))
      (node (ref "JP9") (pin "9") (pinfunction "9_9") (pintype "passive"))
      (node (ref "K77") (pin "1") (pinfunction "+_1") (pintype "passive"))
      (node (ref "K77") (pin "4") (pinfunction "S_4") (pintype "passive"))
      (node (ref "LED28") (pin "A") (pinfunction "A_A") (pintype "passive"))
    )
    (net (code "198") (name "Net-(K78A-+)") (class "Default")
      (node (ref "JP1") (pin "7") (pinfunction "7_7") (pintype "passive"))
      (node (ref "JP10") (pin "7") (pinfunction "7_7") (pintype "passive"))
      (node (ref "JP11") (pin "7") (pinfunction "7_7") (pintype "passive"))
      (node (ref "JP12") (pin "7") (pinfunction "7_7") (pintype "passive"))
      (node (ref "JP13") (pin "7") (pinfunction "7_7") (pintype "passive"))
      (node (ref "JP14") (pin "7") (pinfunction "7_7") (pintype "passive"))
      (node (ref "JP15") (pin "7") (pinfunction "7_7") (pintype "passive"))
      (node (ref "JP16") (pin "7") (pinfunction "7_7") (pintype "passive"))
      (node (ref "JP17") (pin "9") (pinfunction "9_9") (pintype "passive"))
      (node (ref "JP18") (pin "9") (pinfunction "9_9") (pintype "passive"))
      (node (ref "JP19") (pin "9") (pinfunction "9_9") (pintype "passive"))
      (node (ref "JP2") (pin "7") (pinfunction "7_7") (pintype "passive"))
      (node (ref "JP20") (pin "9") (pinfunction "9_9") (pintype "passive"))
      (node (ref "JP21") (pin "9") (pinfunction "9_9") (pintype "passive"))
      (node (ref "JP22") (pin "9") (pinfunction "9_9") (pintype "passive"))
      (node (ref "JP23") (pin "9") (pinfunction "9_9") (pintype "passive"))
      (node (ref "JP24") (pin "9") (pinfunction "9_9") (pintype "passive"))
      (node (ref "JP25") (pin "9") (pinfunction "9_9") (pintype "passive"))
      (node (ref "JP26") (pin "9") (pinfunction "9_9") (pintype "passive"))
      (node (ref "JP27") (pin "9") (pinfunction "9_9") (pintype "passive"))
      (node (ref "JP28") (pin "9") (pinfunction "9_9") (pintype "passive"))
      (node (ref "JP29") (pin "9") (pinfunction "9_9") (pintype "passive"))
      (node (ref "JP3") (pin "7") (pinfunction "7_7") (pintype "passive"))
      (node (ref "JP30") (pin "9") (pinfunction "9_9") (pintype "passive"))
      (node (ref "JP31") (pin "9") (pinfunction "9_9") (pintype "passive"))
      (node (ref "JP32") (pin "9") (pinfunction "9_9") (pintype "passive"))
      (node (ref "JP4") (pin "7") (pinfunction "7_7") (pintype "passive"))
      (node (ref "JP5") (pin "7") (pinfunction "7_7") (pintype "passive"))
      (node (ref "JP6") (pin "7") (pinfunction "7_7") (pintype "passive"))
      (node (ref "JP7") (pin "7") (pinfunction "7_7") (pintype "passive"))
      (node (ref "JP8") (pin "7") (pinfunction "7_7") (pintype "passive"))
      (node (ref "JP9") (pin "7") (pinfunction "7_7") (pintype "passive"))
      (node (ref "K78") (pin "1") (pinfunction "+_1") (pintype "passive"))
      (node (ref "K78") (pin "4") (pinfunction "S_4") (pintype "passive"))
      (node (ref "LED29") (pin "A") (pinfunction "A_A") (pintype "passive"))
    )
    (net (code "199") (name "Net-(K79A-+)") (class "Default")
      (node (ref "JP1") (pin "5") (pinfunction "5_5") (pintype "passive"))
      (node (ref "JP10") (pin "5") (pinfunction "5_5") (pintype "passive"))
      (node (ref "JP11") (pin "5") (pinfunction "5_5") (pintype "passive"))
      (node (ref "JP12") (pin "5") (pinfunction "5_5") (pintype "passive"))
      (node (ref "JP13") (pin "5") (pinfunction "5_5") (pintype "passive"))
      (node (ref "JP14") (pin "5") (pinfunction "5_5") (pintype "passive"))
      (node (ref "JP15") (pin "5") (pinfunction "5_5") (pintype "passive"))
      (node (ref "JP16") (pin "5") (pinfunction "5_5") (pintype "passive"))
      (node (ref "JP17") (pin "11") (pinfunction "11_11") (pintype "passive"))
      (node (ref "JP18") (pin "11") (pinfunction "11_11") (pintype "passive"))
      (node (ref "JP19") (pin "11") (pinfunction "11_11") (pintype "passive"))
      (node (ref "JP2") (pin "5") (pinfunction "5_5") (pintype "passive"))
      (node (ref "JP20") (pin "11") (pinfunction "11_11") (pintype "passive"))
      (node (ref "JP21") (pin "11") (pinfunction "11_11") (pintype "passive"))
      (node (ref "JP22") (pin "11") (pinfunction "11_11") (pintype "passive"))
      (node (ref "JP23") (pin "11") (pinfunction "11_11") (pintype "passive"))
      (node (ref "JP24") (pin "11") (pinfunction "11_11") (pintype "passive"))
      (node (ref "JP25") (pin "11") (pinfunction "11_11") (pintype "passive"))
      (node (ref "JP26") (pin "11") (pinfunction "11_11") (pintype "passive"))
      (node (ref "JP27") (pin "11") (pinfunction "11_11") (pintype "passive"))
      (node (ref "JP28") (pin "11") (pinfunction "11_11") (pintype "passive"))
      (node (ref "JP29") (pin "11") (pinfunction "11_11") (pintype "passive"))
      (node (ref "JP3") (pin "5") (pinfunction "5_5") (pintype "passive"))
      (node (ref "JP30") (pin "11") (pinfunction "11_11") (pintype "passive"))
      (node (ref "JP31") (pin "11") (pinfunction "11_11") (pintype "passive"))
      (node (ref "JP32") (pin "11") (pinfunction "11_11") (pintype "passive"))
      (node (ref "JP4") (pin "5") (pinfunction "5_5") (pintype "passive"))
      (node (ref "JP5") (pin "5") (pinfunction "5_5") (pintype "passive"))
      (node (ref "JP6") (pin "5") (pinfunction "5_5") (pintype "passive"))
      (node (ref "JP7") (pin "5") (pinfunction "5_5") (pintype "passive"))
      (node (ref "JP8") (pin "5") (pinfunction "5_5") (pintype "passive"))
      (node (ref "JP9") (pin "5") (pinfunction "5_5") (pintype "passive"))
      (node (ref "K79") (pin "1") (pinfunction "+_1") (pintype "passive"))
      (node (ref "K79") (pin "4") (pinfunction "S_4") (pintype "passive"))
      (node (ref "LED30") (pin "A") (pinfunction "A_A") (pintype "passive"))
    )
    (net (code "200") (name "Net-(K80A-+)") (class "Default")
      (node (ref "JP1") (pin "3") (pinfunction "3_3") (pintype "passive"))
      (node (ref "JP10") (pin "3") (pinfunction "3_3") (pintype "passive"))
      (node (ref "JP11") (pin "3") (pinfunction "3_3") (pintype "passive"))
      (node (ref "JP12") (pin "3") (pinfunction "3_3") (pintype "passive"))
      (node (ref "JP13") (pin "3") (pinfunction "3_3") (pintype "passive"))
      (node (ref "JP14") (pin "3") (pinfunction "3_3") (pintype "passive"))
      (node (ref "JP15") (pin "3") (pinfunction "3_3") (pintype "passive"))
      (node (ref "JP16") (pin "3") (pinfunction "3_3") (pintype "passive"))
      (node (ref "JP17") (pin "13") (pinfunction "13_13") (pintype "passive"))
      (node (ref "JP18") (pin "13") (pinfunction "13_13") (pintype "passive"))
      (node (ref "JP19") (pin "13") (pinfunction "13_13") (pintype "passive"))
      (node (ref "JP2") (pin "3") (pinfunction "3_3") (pintype "passive"))
      (node (ref "JP20") (pin "13") (pinfunction "13_13") (pintype "passive"))
      (node (ref "JP21") (pin "13") (pinfunction "13_13") (pintype "passive"))
      (node (ref "JP22") (pin "13") (pinfunction "13_13") (pintype "passive"))
      (node (ref "JP23") (pin "13") (pinfunction "13_13") (pintype "passive"))
      (node (ref "JP24") (pin "13") (pinfunction "13_13") (pintype "passive"))
      (node (ref "JP25") (pin "13") (pinfunction "13_13") (pintype "passive"))
      (node (ref "JP26") (pin "13") (pinfunction "13_13") (pintype "passive"))
      (node (ref "JP27") (pin "13") (pinfunction "13_13") (pintype "passive"))
      (node (ref "JP28") (pin "13") (pinfunction "13_13") (pintype "passive"))
      (node (ref "JP29") (pin "13") (pinfunction "13_13") (pintype "passive"))
      (node (ref "JP3") (pin "3") (pinfunction "3_3") (pintype "passive"))
      (node (ref "JP30") (pin "13") (pinfunction "13_13") (pintype "passive"))
      (node (ref "JP31") (pin "13") (pinfunction "13_13") (pintype "passive"))
      (node (ref "JP32") (pin "13") (pinfunction "13_13") (pintype "passive"))
      (node (ref "JP4") (pin "3") (pinfunction "3_3") (pintype "passive"))
      (node (ref "JP5") (pin "3") (pinfunction "3_3") (pintype "passive"))
      (node (ref "JP6") (pin "3") (pinfunction "3_3") (pintype "passive"))
      (node (ref "JP7") (pin "3") (pinfunction "3_3") (pintype "passive"))
      (node (ref "JP8") (pin "3") (pinfunction "3_3") (pintype "passive"))
      (node (ref "JP9") (pin "3") (pinfunction "3_3") (pintype "passive"))
      (node (ref "K80") (pin "1") (pinfunction "+_1") (pintype "passive"))
      (node (ref "K80") (pin "4") (pinfunction "S_4") (pintype "passive"))
      (node (ref "LED31") (pin "A") (pinfunction "A_A") (pintype "passive"))
    )
    (net (code "201") (name "Net-(K81A-+)") (class "Default")
      (node (ref "JP1") (pin "1") (pinfunction "1_1") (pintype "passive"))
      (node (ref "JP10") (pin "1") (pinfunction "1_1") (pintype "passive"))
      (node (ref "JP11") (pin "1") (pinfunction "1_1") (pintype "passive"))
      (node (ref "JP12") (pin "1") (pinfunction "1_1") (pintype "passive"))
      (node (ref "JP13") (pin "1") (pinfunction "1_1") (pintype "passive"))
      (node (ref "JP14") (pin "1") (pinfunction "1_1") (pintype "passive"))
      (node (ref "JP15") (pin "1") (pinfunction "1_1") (pintype "passive"))
      (node (ref "JP16") (pin "1") (pinfunction "1_1") (pintype "passive"))
      (node (ref "JP17") (pin "15") (pinfunction "15_15") (pintype "passive"))
      (node (ref "JP18") (pin "15") (pinfunction "15_15") (pintype "passive"))
      (node (ref "JP19") (pin "15") (pinfunction "15_15") (pintype "passive"))
      (node (ref "JP2") (pin "1") (pinfunction "1_1") (pintype "passive"))
      (node (ref "JP20") (pin "15") (pinfunction "15_15") (pintype "passive"))
      (node (ref "JP21") (pin "15") (pinfunction "15_15") (pintype "passive"))
      (node (ref "JP22") (pin "15") (pinfunction "15_15") (pintype "passive"))
      (node (ref "JP23") (pin "15") (pinfunction "15_15") (pintype "passive"))
      (node (ref "JP24") (pin "15") (pinfunction "15_15") (pintype "passive"))
      (node (ref "JP25") (pin "15") (pinfunction "15_15") (pintype "passive"))
      (node (ref "JP26") (pin "15") (pinfunction "15_15") (pintype "passive"))
      (node (ref "JP27") (pin "15") (pinfunction "15_15") (pintype "passive"))
      (node (ref "JP28") (pin "15") (pinfunction "15_15") (pintype "passive"))
      (node (ref "JP29") (pin "15") (pinfunction "15_15") (pintype "passive"))
      (node (ref "JP3") (pin "1") (pinfunction "1_1") (pintype "passive"))
      (node (ref "JP30") (pin "15") (pinfunction "15_15") (pintype "passive"))
      (node (ref "JP31") (pin "15") (pinfunction "15_15") (pintype "passive"))
      (node (ref "JP32") (pin "15") (pinfunction "15_15") (pintype "passive"))
      (node (ref "JP4") (pin "1") (pinfunction "1_1") (pintype "passive"))
      (node (ref "JP5") (pin "1") (pinfunction "1_1") (pintype "passive"))
      (node (ref "JP6") (pin "1") (pinfunction "1_1") (pintype "passive"))
      (node (ref "JP7") (pin "1") (pinfunction "1_1") (pintype "passive"))
      (node (ref "JP8") (pin "1") (pinfunction "1_1") (pintype "passive"))
      (node (ref "JP9") (pin "1") (pinfunction "1_1") (pintype "passive"))
      (node (ref "K81") (pin "1") (pinfunction "+_1") (pintype "passive"))
      (node (ref "K81") (pin "4") (pinfunction "S_4") (pintype "passive"))
      (node (ref "LED32") (pin "A") (pinfunction "A_A") (pintype "passive"))
    )
    (net (code "202") (name "Net-(K82A-+)") (class "Default")
      (node (ref "D1") (pin "C") (pinfunction "C_C") (pintype "passive"))
      (node (ref "D2") (pin "C") (pinfunction "C_C") (pintype "passive"))
      (node (ref "K82") (pin "1") (pinfunction "+_1") (pintype "passive"))
    )
    (net (code "203") (name "Net-(K83B-P)") (class "Default")
      (node (ref "K66") (pin "1") (pinfunction "1_1") (pintype "passive"))
      (node (ref "K83") (pin "3") (pinfunction "P_3") (pintype "passive"))
      (node (ref "R29") (pin "2") (pinfunction "2_2") (pintype "passive"))
    )
    (net (code "204") (name "Net-(K83C-P)") (class "Default")
      (node (ref "K63") (pin "1") (pinfunction "1_1") (pintype "passive"))
      (node (ref "K83") (pin "6") (pinfunction "P_6") (pintype "passive"))
      (node (ref "R27") (pin "2") (pinfunction "2_2") (pintype "passive"))
    )
    (net (code "205") (name "Net-(K84B-P)") (class "Default")
      (node (ref "K71") (pin "1") (pinfunction "1_1") (pintype "passive"))
      (node (ref "K84") (pin "3") (pinfunction "P_3") (pintype "passive"))
      (node (ref "R33") (pin "2") (pinfunction "2_2") (pintype "passive"))
    )
    (net (code "206") (name "Net-(K84C-P)") (class "Default")
      (node (ref "K68") (pin "1") (pinfunction "1_1") (pintype "passive"))
      (node (ref "K84") (pin "6") (pinfunction "P_6") (pintype "passive"))
      (node (ref "R31") (pin "2") (pinfunction "2_2") (pintype "passive"))
    )
    (net (code "207") (name "Net-(K85A-+)") (class "Default")
      (node (ref "K85") (pin "1") (pinfunction "+_1") (pintype "passive"))
      (node (ref "K85") (pin "4") (pinfunction "S_4") (pintype "passive"))
      (node (ref "K90") (pin "6") (pinfunction "P_6") (pintype "passive"))
      (node (ref "LED33") (pin "A") (pinfunction "A_A") (pintype "passive"))
    )
    (net (code "208") (name "Net-(K86A-+)") (class "Default")
      (node (ref "K86") (pin "1") (pinfunction "+_1") (pintype "passive"))
      (node (ref "K86") (pin "4") (pinfunction "S_4") (pintype "passive"))
      (node (ref "K91") (pin "6") (pinfunction "P_6") (pintype "passive"))
      (node (ref "LED34") (pin "A") (pinfunction "A_A") (pintype "passive"))
    )
    (net (code "209") (name "Net-(K87A-+)") (class "Default")
      (node (ref "K87") (pin "1") (pinfunction "+_1") (pintype "passive"))
      (node (ref "K87") (pin "4") (pinfunction "S_4") (pintype "passive"))
      (node (ref "K92") (pin "6") (pinfunction "P_6") (pintype "passive"))
      (node (ref "LED35") (pin "A") (pinfunction "A_A") (pintype "passive"))
    )
    (net (code "210") (name "Net-(K88A-+)") (class "Default")
      (node (ref "K88") (pin "1") (pinfunction "+_1") (pintype "passive"))
      (node (ref "K88") (pin "4") (pinfunction "S_4") (pintype "passive"))
      (node (ref "K93") (pin "6") (pinfunction "P_6") (pintype "passive"))
      (node (ref "LED36") (pin "A") (pinfunction "A_A") (pintype "passive"))
    )
    (net (code "211") (name "Net-(K89A-+)") (class "Default")
      (node (ref "K89") (pin "1") (pinfunction "+_1") (pintype "passive"))
      (node (ref "K89") (pin "4") (pinfunction "S_4") (pintype "passive"))
      (node (ref "K94") (pin "6") (pinfunction "P_6") (pintype "passive"))
      (node (ref "LED37") (pin "A") (pinfunction "A_A") (pintype "passive"))
    )
    (net (code "212") (name "Net-(K97B-P)") (class "Default")
      (node (ref "D38") (pin "A") (pinfunction "A_A") (pintype "passive"))
      (node (ref "K97") (pin "3") (pinfunction "P_3") (pintype "passive"))
    )
    (net (code "213") (name "Net-(K98B-P)") (class "Default")
      (node (ref "D35") (pin "A") (pinfunction "A_A") (pintype "passive"))
      (node (ref "D37") (pin "A") (pinfunction "A_A") (pintype "passive"))
      (node (ref "D42") (pin "A") (pinfunction "A_A") (pintype "passive"))
      (node (ref "K98") (pin "3") (pinfunction "P_3") (pintype "passive"))
    )
    (net (code "214") (name "Net-(K99B-P)") (class "Default")
      (node (ref "D43") (pin "A") (pinfunction "A_A") (pintype "passive"))
      (node (ref "D47") (pin "A") (pinfunction "A_A") (pintype "passive"))
      (node (ref "K99") (pin "3") (pinfunction "P_3") (pintype "passive"))
    )
    (net (code "215") (name "Net-(K100B-P)") (class "Default")
      (node (ref "D41") (pin "A") (pinfunction "A_A") (pintype "passive"))
      (node (ref "D44") (pin "A") (pinfunction "A_A") (pintype "passive"))
      (node (ref "K100") (pin "3") (pinfunction "P_3") (pintype "passive"))
    )
    (net (code "216") (name "Net-(LED1-PadA)") (class "Default")
      (node (ref "LED1") (pin "A") (pinfunction "A_A") (pintype "passive"))
      (node (ref "R3") (pin "1") (pinfunction "1_1") (pintype "passive"))
    )
    (net (code "217") (name "Net-(LED2-PadA)") (class "Default")
      (node (ref "LED2") (pin "A") (pinfunction "A_A") (pintype "passive"))
      (node (ref "R2") (pin "1") (pinfunction "1_1") (pintype "passive"))
    )
    (net (code "218") (name "Net-(LED3-PadA)") (class "Default")
      (node (ref "LED3") (pin "A") (pinfunction "A_A") (pintype "passive"))
      (node (ref "R4") (pin "1") (pinfunction "1_1") (pintype "passive"))
    )
    (net (code "219") (name "Net-(LED4-PadA)") (class "Default")
      (node (ref "LED4") (pin "A") (pinfunction "A_A") (pintype "passive"))
      (node (ref "R5") (pin "1") (pinfunction "1_1") (pintype "passive"))
    )
    (net (code "220") (name "Net-(LED5-PadA)") (class "Default")
      (node (ref "LED5") (pin "A") (pinfunction "A_A") (pintype "passive"))
      (node (ref "R6") (pin "1") (pinfunction "1_1") (pintype "passive"))
    )
    (net (code "221") (name "Net-(LED6-PadA)") (class "Default")
      (node (ref "LED6") (pin "A") (pinfunction "A_A") (pintype "passive"))
      (node (ref "R7") (pin "1") (pinfunction "1_1") (pintype "passive"))
    )
    (net (code "222") (name "Net-(LED7-PadA)") (class "Default")
      (node (ref "LED7") (pin "A") (pinfunction "A_A") (pintype "passive"))
      (node (ref "R8") (pin "1") (pinfunction "1_1") (pintype "passive"))
    )
    (net (code "223") (name "Net-(LED8-PadA)") (class "Default")
      (node (ref "LED8") (pin "A") (pinfunction "A_A") (pintype "passive"))
      (node (ref "R9") (pin "1") (pinfunction "1_1") (pintype "passive"))
    )
    (net (code "224") (name "Net-(LED9-PadA)") (class "Default")
      (node (ref "LED9") (pin "A") (pinfunction "A_A") (pintype "passive"))
      (node (ref "R10") (pin "1") (pinfunction "1_1") (pintype "passive"))
    )
    (net (code "225") (name "Net-(LED10-PadA)") (class "Default")
      (node (ref "LED10") (pin "A") (pinfunction "A_A") (pintype "passive"))
      (node (ref "R11") (pin "1") (pinfunction "1_1") (pintype "passive"))
    )
    (net (code "226") (name "Net-(LED11-PadA)") (class "Default")
      (node (ref "LED11") (pin "A") (pinfunction "A_A") (pintype "passive"))
      (node (ref "R12") (pin "1") (pinfunction "1_1") (pintype "passive"))
    )
    (net (code "227") (name "Net-(LED12-PadA)") (class "Default")
      (node (ref "LED12") (pin "A") (pinfunction "A_A") (pintype "passive"))
      (node (ref "R13") (pin "1") (pinfunction "1_1") (pintype "passive"))
    )
    (net (code "228") (name "Net-(LED13-PadA)") (class "Default")
      (node (ref "LED13") (pin "A") (pinfunction "A_A") (pintype "passive"))
      (node (ref "R14") (pin "1") (pinfunction "1_1") (pintype "passive"))
    )
    (net (code "229") (name "Net-(LED14-PadA)") (class "Default")
      (node (ref "LED14") (pin "A") (pinfunction "A_A") (pintype "passive"))
      (node (ref "R15") (pin "1") (pinfunction "1_1") (pintype "passive"))
    )
    (net (code "230") (name "Net-(LED15-PadA)") (class "Default")
      (node (ref "LED15") (pin "A") (pinfunction "A_A") (pintype "passive"))
      (node (ref "R16") (pin "1") (pinfunction "1_1") (pintype "passive"))
    )
    (net (code "231") (name "Net-(LED16-PadA)") (class "Default")
      (node (ref "LED16") (pin "A") (pinfunction "A_A") (pintype "passive"))
      (node (ref "R17") (pin "1") (pinfunction "1_1") (pintype "passive"))
    )
    (net (code "232") (name "Net-(LED17-PadA)") (class "Default")
      (node (ref "LED17") (pin "A") (pinfunction "A_A") (pintype "passive"))
      (node (ref "R18") (pin "1") (pinfunction "1_1") (pintype "passive"))
    )
    (net (code "233") (name "Net-(LED18-PadA)") (class "Default")
      (node (ref "LED18") (pin "A") (pinfunction "A_A") (pintype "passive"))
      (node (ref "R19") (pin "1") (pinfunction "1_1") (pintype "passive"))
    )
    (net (code "234") (name "Net-(LED19-PadA)") (class "Default")
      (node (ref "LED19") (pin "A") (pinfunction "A_A") (pintype "passive"))
      (node (ref "R20") (pin "1") (pinfunction "1_1") (pintype "passive"))
    )
    (net (code "235") (name "Net-(LED20-PadA)") (class "Default")
      (node (ref "LED20") (pin "A") (pinfunction "A_A") (pintype "passive"))
      (node (ref "R21") (pin "1") (pinfunction "1_1") (pintype "passive"))
    )
    (net (code "236") (name "Net-(LED21-PadA)") (class "Default")
      (node (ref "LED21") (pin "A") (pinfunction "A_A") (pintype "passive"))
      (node (ref "R22") (pin "1") (pinfunction "1_1") (pintype "passive"))
    )
    (net (code "237") (name "Net-(LED22-PadA)") (class "Default")
      (node (ref "LED22") (pin "A") (pinfunction "A_A") (pintype "passive"))
      (node (ref "R23") (pin "1") (pinfunction "1_1") (pintype "passive"))
    )
    (net (code "238") (name "Net-(LED23-PadA)") (class "Default")
      (node (ref "LED23") (pin "A") (pinfunction "A_A") (pintype "passive"))
      (node (ref "R24") (pin "1") (pinfunction "1_1") (pintype "passive"))
    )
    (net (code "239") (name "Net-(LED24-PadA)") (class "Default")
      (node (ref "LED24") (pin "A") (pinfunction "A_A") (pintype "passive"))
      (node (ref "R25") (pin "1") (pinfunction "1_1") (pintype "passive"))
    )
    (net (code "240") (name "Net-(LED25-C)") (class "Default")
      (node (ref "LED25") (pin "K") (pinfunction "C_K") (pintype "passive"))
      (node (ref "R34") (pin "2") (pinfunction "2_2") (pintype "passive"))
    )
    (net (code "241") (name "Net-(LED26-C)") (class "Default")
      (node (ref "LED26") (pin "K") (pinfunction "C_K") (pintype "passive"))
      (node (ref "R35") (pin "2") (pinfunction "2_2") (pintype "passive"))
    )
    (net (code "242") (name "Net-(LED27-C)") (class "Default")
      (node (ref "LED27") (pin "K") (pinfunction "C_K") (pintype "passive"))
      (node (ref "R36") (pin "2") (pinfunction "2_2") (pintype "passive"))
    )
    (net (code "243") (name "Net-(LED28-C)") (class "Default")
      (node (ref "LED28") (pin "K") (pinfunction "C_K") (pintype "passive"))
      (node (ref "R37") (pin "2") (pinfunction "2_2") (pintype "passive"))
    )
    (net (code "244") (name "Net-(LED29-C)") (class "Default")
      (node (ref "LED29") (pin "K") (pinfunction "C_K") (pintype "passive"))
      (node (ref "R38") (pin "2") (pinfunction "2_2") (pintype "passive"))
    )
    (net (code "245") (name "Net-(LED30-C)") (class "Default")
      (node (ref "LED30") (pin "K") (pinfunction "C_K") (pintype "passive"))
      (node (ref "R39") (pin "2") (pinfunction "2_2") (pintype "passive"))
    )
    (net (code "246") (name "Net-(LED31-C)") (class "Default")
      (node (ref "LED31") (pin "K") (pinfunction "C_K") (pintype "passive"))
      (node (ref "R40") (pin "2") (pinfunction "2_2") (pintype "passive"))
    )
    (net (code "247") (name "Net-(LED32-C)") (class "Default")
      (node (ref "LED32") (pin "K") (pinfunction "C_K") (pintype "passive"))
      (node (ref "R41") (pin "2") (pinfunction "2_2") (pintype "passive"))
    )
    (net (code "248") (name "Net-(LED33-C)") (class "Default")
      (node (ref "LED33") (pin "K") (pinfunction "C_K") (pintype "passive"))
      (node (ref "R42") (pin "2") (pinfunction "2_2") (pintype "passive"))
    )
    (net (code "249") (name "Net-(LED34-C)") (class "Default")
      (node (ref "LED34") (pin "K") (pinfunction "C_K") (pintype "passive"))
      (node (ref "R43") (pin "2") (pinfunction "2_2") (pintype "passive"))
    )
    (net (code "250") (name "Net-(LED35-C)") (class "Default")
      (node (ref "LED35") (pin "K") (pinfunction "C_K") (pintype "passive"))
      (node (ref "R44") (pin "2") (pinfunction "2_2") (pintype "passive"))
    )
    (net (code "251") (name "Net-(LED36-C)") (class "Default")
      (node (ref "LED36") (pin "K") (pinfunction "C_K") (pintype "passive"))
      (node (ref "R45") (pin "2") (pinfunction "2_2") (pintype "passive"))
    )
    (net (code "252") (name "Net-(LED37-C)") (class "Default")
      (node (ref "LED37") (pin "K") (pinfunction "C_K") (pintype "passive"))
      (node (ref "R46") (pin "2") (pinfunction "2_2") (pintype "passive"))
    )
    (net (code "253") (name "unconnected-(K1B-O-Pad2)") (class "Default")
      (node (ref "K1") (pin "2") (pinfunction "O_2") (pintype "passive"))
    )
    (net (code "254") (name "unconnected-(K1C-O-Pad7)") (class "Default")
      (node (ref "K1") (pin "7") (pinfunction "O_7") (pintype "passive"))
    )
    (net (code "255") (name "unconnected-(K3B-O-Pad2)") (class "Default")
      (node (ref "K3") (pin "2") (pinfunction "O_2") (pintype "passive"))
    )
    (net (code "256") (name "unconnected-(K3C-O-Pad7)") (class "Default")
      (node (ref "K3") (pin "7") (pinfunction "O_7") (pintype "passive"))
    )
    (net (code "257") (name "unconnected-(K6B-O-Pad2)") (class "Default")
      (node (ref "K6") (pin "2") (pinfunction "O_2") (pintype "passive"))
    )
    (net (code "258") (name "unconnected-(K6C-O-Pad7)") (class "Default")
      (node (ref "K6") (pin "7") (pinfunction "O_7") (pintype "passive"))
    )
    (net (code "259") (name "unconnected-(K8B-O-Pad2)") (class "Default")
      (node (ref "K8") (pin "2") (pinfunction "O_2") (pintype "passive"))
    )
    (net (code "260") (name "unconnected-(K8C-O-Pad7)") (class "Default")
      (node (ref "K8") (pin "7") (pinfunction "O_7") (pintype "passive"))
    )
    (net (code "261") (name "unconnected-(K10B-O-Pad2)") (class "Default")
      (node (ref "K10") (pin "2") (pinfunction "O_2") (pintype "passive"))
    )
    (net (code "262") (name "unconnected-(K10C-O-Pad7)") (class "Default")
      (node (ref "K10") (pin "7") (pinfunction "O_7") (pintype "passive"))
    )
    (net (code "263") (name "unconnected-(K12B-O-Pad2)") (class "Default")
      (node (ref "K12") (pin "2") (pinfunction "O_2") (pintype "passive"))
    )
    (net (code "264") (name "unconnected-(K12C-O-Pad7)") (class "Default")
      (node (ref "K12") (pin "7") (pinfunction "O_7") (pintype "passive"))
    )
    (net (code "265") (name "unconnected-(K16B-O-Pad2)") (class "Default")
      (node (ref "K16") (pin "2") (pinfunction "O_2") (pintype "passive"))
    )
    (net (code "266") (name "unconnected-(K16C-O-Pad7)") (class "Default")
      (node (ref "K16") (pin "7") (pinfunction "O_7") (pintype "passive"))
    )
    (net (code "267") (name "unconnected-(K18B-O-Pad2)") (class "Default")
      (node (ref "K18") (pin "2") (pinfunction "O_2") (pintype "passive"))
    )
    (net (code "268") (name "unconnected-(K18B-P-Pad3)") (class "Default")
      (node (ref "K18") (pin "3") (pinfunction "P_3") (pintype "passive"))
    )
    (net (code "269") (name "unconnected-(K18B-S-Pad4)") (class "Default")
      (node (ref "K18") (pin "4") (pinfunction "S_4") (pintype "passive"))
    )
    (net (code "270") (name "unconnected-(K18C-O-Pad7)") (class "Default")
      (node (ref "K18") (pin "7") (pinfunction "O_7") (pintype "passive"))
    )
    (net (code "271") (name "unconnected-(K20B-O-Pad2)") (class "Default")
      (node (ref "K20") (pin "2") (pinfunction "O_2") (pintype "passive"))
    )
    (net (code "272") (name "unconnected-(K20C-O-Pad7)") (class "Default")
      (node (ref "K20") (pin "7") (pinfunction "O_7") (pintype "passive"))
    )
    (net (code "273") (name "unconnected-(K25B-O-Pad2)") (class "Default")
      (node (ref "K25") (pin "2") (pinfunction "O_2") (pintype "passive"))
    )
    (net (code "274") (name "unconnected-(K25C-O-Pad7)") (class "Default")
      (node (ref "K25") (pin "7") (pinfunction "O_7") (pintype "passive"))
    )
    (net (code "275") (name "unconnected-(K26B-O-Pad2)") (class "Default")
      (node (ref "K26") (pin "2") (pinfunction "O_2") (pintype "passive"))
    )
    (net (code "276") (name "unconnected-(K26C-O-Pad7)") (class "Default")
      (node (ref "K26") (pin "7") (pinfunction "O_7") (pintype "passive"))
    )
    (net (code "277") (name "unconnected-(K28B-O-Pad2)") (class "Default")
      (node (ref "K28") (pin "2") (pinfunction "O_2") (pintype "passive"))
    )
    (net (code "278") (name "unconnected-(K28C-O-Pad7)") (class "Default")
      (node (ref "K28") (pin "7") (pinfunction "O_7") (pintype "passive"))
    )
    (net (code "279") (name "unconnected-(K29B-O-Pad2)") (class "Default")
      (node (ref "K29") (pin "2") (pinfunction "O_2") (pintype "passive"))
    )
    (net (code "280") (name "unconnected-(K29C-O-Pad7)") (class "Default")
      (node (ref "K29") (pin "7") (pinfunction "O_7") (pintype "passive"))
    )
    (net (code "281") (name "unconnected-(K31B-O-Pad2)") (class "Default")
      (node (ref "K31") (pin "2") (pinfunction "O_2") (pintype "passive"))
    )
    (net (code "282") (name "unconnected-(K31C-O-Pad7)") (class "Default")
      (node (ref "K31") (pin "7") (pinfunction "O_7") (pintype "passive"))
    )
    (net (code "283") (name "unconnected-(K32B-O-Pad2)") (class "Default")
      (node (ref "K32") (pin "2") (pinfunction "O_2") (pintype "passive"))
    )
    (net (code "284") (name "unconnected-(K32C-O-Pad7)") (class "Default")
      (node (ref "K32") (pin "7") (pinfunction "O_7") (pintype "passive"))
    )
    (net (code "285") (name "unconnected-(K34B-O-Pad2)") (class "Default")
      (node (ref "K34") (pin "2") (pinfunction "O_2") (pintype "passive"))
    )
    (net (code "286") (name "unconnected-(K34C-O-Pad7)") (class "Default")
      (node (ref "K34") (pin "7") (pinfunction "O_7") (pintype "passive"))
    )
    (net (code "287") (name "unconnected-(K35B-O-Pad2)") (class "Default")
      (node (ref "K35") (pin "2") (pinfunction "O_2") (pintype "passive"))
    )
    (net (code "288") (name "unconnected-(K35C-O-Pad7)") (class "Default")
      (node (ref "K35") (pin "7") (pinfunction "O_7") (pintype "passive"))
    )
    (net (code "289") (name "unconnected-(K37B-O-Pad2)") (class "Default")
      (node (ref "K37") (pin "2") (pinfunction "O_2") (pintype "passive"))
    )
    (net (code "290") (name "unconnected-(K37C-O-Pad7)") (class "Default")
      (node (ref "K37") (pin "7") (pinfunction "O_7") (pintype "passive"))
    )
    (net (code "291") (name "unconnected-(K38B-O-Pad2)") (class "Default")
      (node (ref "K38") (pin "2") (pinfunction "O_2") (pintype "passive"))
    )
    (net (code "292") (name "unconnected-(K38C-O-Pad7)") (class "Default")
      (node (ref "K38") (pin "7") (pinfunction "O_7") (pintype "passive"))
    )
    (net (code "293") (name "unconnected-(K40B-O-Pad2)") (class "Default")
      (node (ref "K40") (pin "2") (pinfunction "O_2") (pintype "passive"))
    )
    (net (code "294") (name "unconnected-(K40C-O-Pad7)") (class "Default")
      (node (ref "K40") (pin "7") (pinfunction "O_7") (pintype "passive"))
    )
    (net (code "295") (name "unconnected-(K41B-O-Pad2)") (class "Default")
      (node (ref "K41") (pin "2") (pinfunction "O_2") (pintype "passive"))
    )
    (net (code "296") (name "unconnected-(K41C-O-Pad7)") (class "Default")
      (node (ref "K41") (pin "7") (pinfunction "O_7") (pintype "passive"))
    )
    (net (code "297") (name "unconnected-(K43B-O-Pad2)") (class "Default")
      (node (ref "K43") (pin "2") (pinfunction "O_2") (pintype "passive"))
    )
    (net (code "298") (name "unconnected-(K43C-O-Pad7)") (class "Default")
      (node (ref "K43") (pin "7") (pinfunction "O_7") (pintype "passive"))
    )
    (net (code "299") (name "unconnected-(K44B-O-Pad2)") (class "Default")
      (node (ref "K44") (pin "2") (pinfunction "O_2") (pintype "passive"))
    )
    (net (code "300") (name "unconnected-(K44C-O-Pad7)") (class "Default")
      (node (ref "K44") (pin "7") (pinfunction "O_7") (pintype "passive"))
    )
    (net (code "301") (name "unconnected-(K46B-O-Pad2)") (class "Default")
      (node (ref "K46") (pin "2") (pinfunction "O_2") (pintype "passive"))
    )
    (net (code "302") (name "unconnected-(K46C-O-Pad7)") (class "Default")
      (node (ref "K46") (pin "7") (pinfunction "O_7") (pintype "passive"))
    )
    (net (code "303") (name "unconnected-(K55C-O-Pad7)") (class "Default")
      (node (ref "K55") (pin "7") (pinfunction "O_7") (pintype "passive"))
    )
    (net (code "304") (name "unconnected-(K55C-P-Pad6)") (class "Default")
      (node (ref "K55") (pin "6") (pinfunction "P_6") (pintype "passive"))
    )
    (net (code "305") (name "unconnected-(K55C-S-Pad5)") (class "Default")
      (node (ref "K55") (pin "5") (pinfunction "S_5") (pintype "passive"))
    )
    (net (code "306") (name "unconnected-(K73B-S-Pad4)") (class "Default")
      (node (ref "K73") (pin "4") (pinfunction "S_4") (pintype "passive"))
    )
    (net (code "307") (name "unconnected-(K73C-O-Pad7)") (class "Default")
      (node (ref "K73") (pin "7") (pinfunction "O_7") (pintype "passive"))
    )
    (net (code "308") (name "unconnected-(K73C-P-Pad6)") (class "Default")
      (node (ref "K73") (pin "6") (pinfunction "P_6") (pintype "passive"))
    )
    (net (code "309") (name "unconnected-(K73C-S-Pad5)") (class "Default")
      (node (ref "K73") (pin "5") (pinfunction "S_5") (pintype "passive"))
    )
    (net (code "310") (name "unconnected-(K74B-O-Pad2)") (class "Default")
      (node (ref "K74") (pin "2") (pinfunction "O_2") (pintype "passive"))
    )
    (net (code "311") (name "unconnected-(K75B-O-Pad2)") (class "Default")
      (node (ref "K75") (pin "2") (pinfunction "O_2") (pintype "passive"))
    )
    (net (code "312") (name "unconnected-(K76B-O-Pad2)") (class "Default")
      (node (ref "K76") (pin "2") (pinfunction "O_2") (pintype "passive"))
    )
    (net (code "313") (name "unconnected-(K77B-O-Pad2)") (class "Default")
      (node (ref "K77") (pin "2") (pinfunction "O_2") (pintype "passive"))
    )
    (net (code "314") (name "unconnected-(K78B-O-Pad2)") (class "Default")
      (node (ref "K78") (pin "2") (pinfunction "O_2") (pintype "passive"))
    )
    (net (code "315") (name "unconnected-(K79B-O-Pad2)") (class "Default")
      (node (ref "K79") (pin "2") (pinfunction "O_2") (pintype "passive"))
    )
    (net (code "316") (name "unconnected-(K80B-O-Pad2)") (class "Default")
      (node (ref "K80") (pin "2") (pinfunction "O_2") (pintype "passive"))
    )
    (net (code "317") (name "unconnected-(K81B-O-Pad2)") (class "Default")
      (node (ref "K81") (pin "2") (pinfunction "O_2") (pintype "passive"))
    )
    (net (code "318") (name "unconnected-(K85B-O-Pad2)") (class "Default")
      (node (ref "K85") (pin "2") (pinfunction "O_2") (pintype "passive"))
    )
    (net (code "319") (name "unconnected-(K86B-O-Pad2)") (class "Default")
      (node (ref "K86") (pin "2") (pinfunction "O_2") (pintype "passive"))
    )
    (net (code "320") (name "unconnected-(K87B-O-Pad2)") (class "Default")
      (node (ref "K87") (pin "2") (pinfunction "O_2") (pintype "passive"))
    )
    (net (code "321") (name "unconnected-(K88B-O-Pad2)") (class "Default")
      (node (ref "K88") (pin "2") (pinfunction "O_2") (pintype "passive"))
    )
    (net (code "322") (name "unconnected-(K89B-O-Pad2)") (class "Default")
      (node (ref "K89") (pin "2") (pinfunction "O_2") (pintype "passive"))
    )
    (net (code "323") (name "unconnected-(K90B-O-Pad2)") (class "Default")
      (node (ref "K90") (pin "2") (pinfunction "O_2") (pintype "passive"))
    )
    (net (code "324") (name "unconnected-(K91B-O-Pad2)") (class "Default")
      (node (ref "K91") (pin "2") (pinfunction "O_2") (pintype "passive"))
    )
    (net (code "325") (name "unconnected-(K92B-O-Pad2)") (class "Default")
      (node (ref "K92") (pin "2") (pinfunction "O_2") (pintype "passive"))
    )
    (net (code "326") (name "unconnected-(K93B-O-Pad2)") (class "Default")
      (node (ref "K93") (pin "2") (pinfunction "O_2") (pintype "passive"))
    )
    (net (code "327") (name "unconnected-(K94B-O-Pad2)") (class "Default")
      (node (ref "K94") (pin "2") (pinfunction "O_2") (pintype "passive"))
    )
    (net (code "328") (name "unconnected-(K95B-S-Pad4)") (class "Default")
      (node (ref "K95") (pin "4") (pinfunction "S_4") (pintype "passive"))
    )
    (net (code "329") (name "unconnected-(K95C-S-Pad5)") (class "Default")
      (node (ref "K95") (pin "5") (pinfunction "S_5") (pintype "passive"))
    )
    (net (code "330") (name "unconnected-(K96B-S-Pad4)") (class "Default")
      (node (ref "K96") (pin "4") (pinfunction "S_4") (pintype "passive"))
    )
    (net (code "331") (name "unconnected-(K96C-S-Pad5)") (class "Default")
      (node (ref "K96") (pin "5") (pinfunction "S_5") (pintype "passive"))
    )
  )
)
